# mainboard-01-8x2_1c.net
KiCad netlist of a schematic drawn in EAGLE
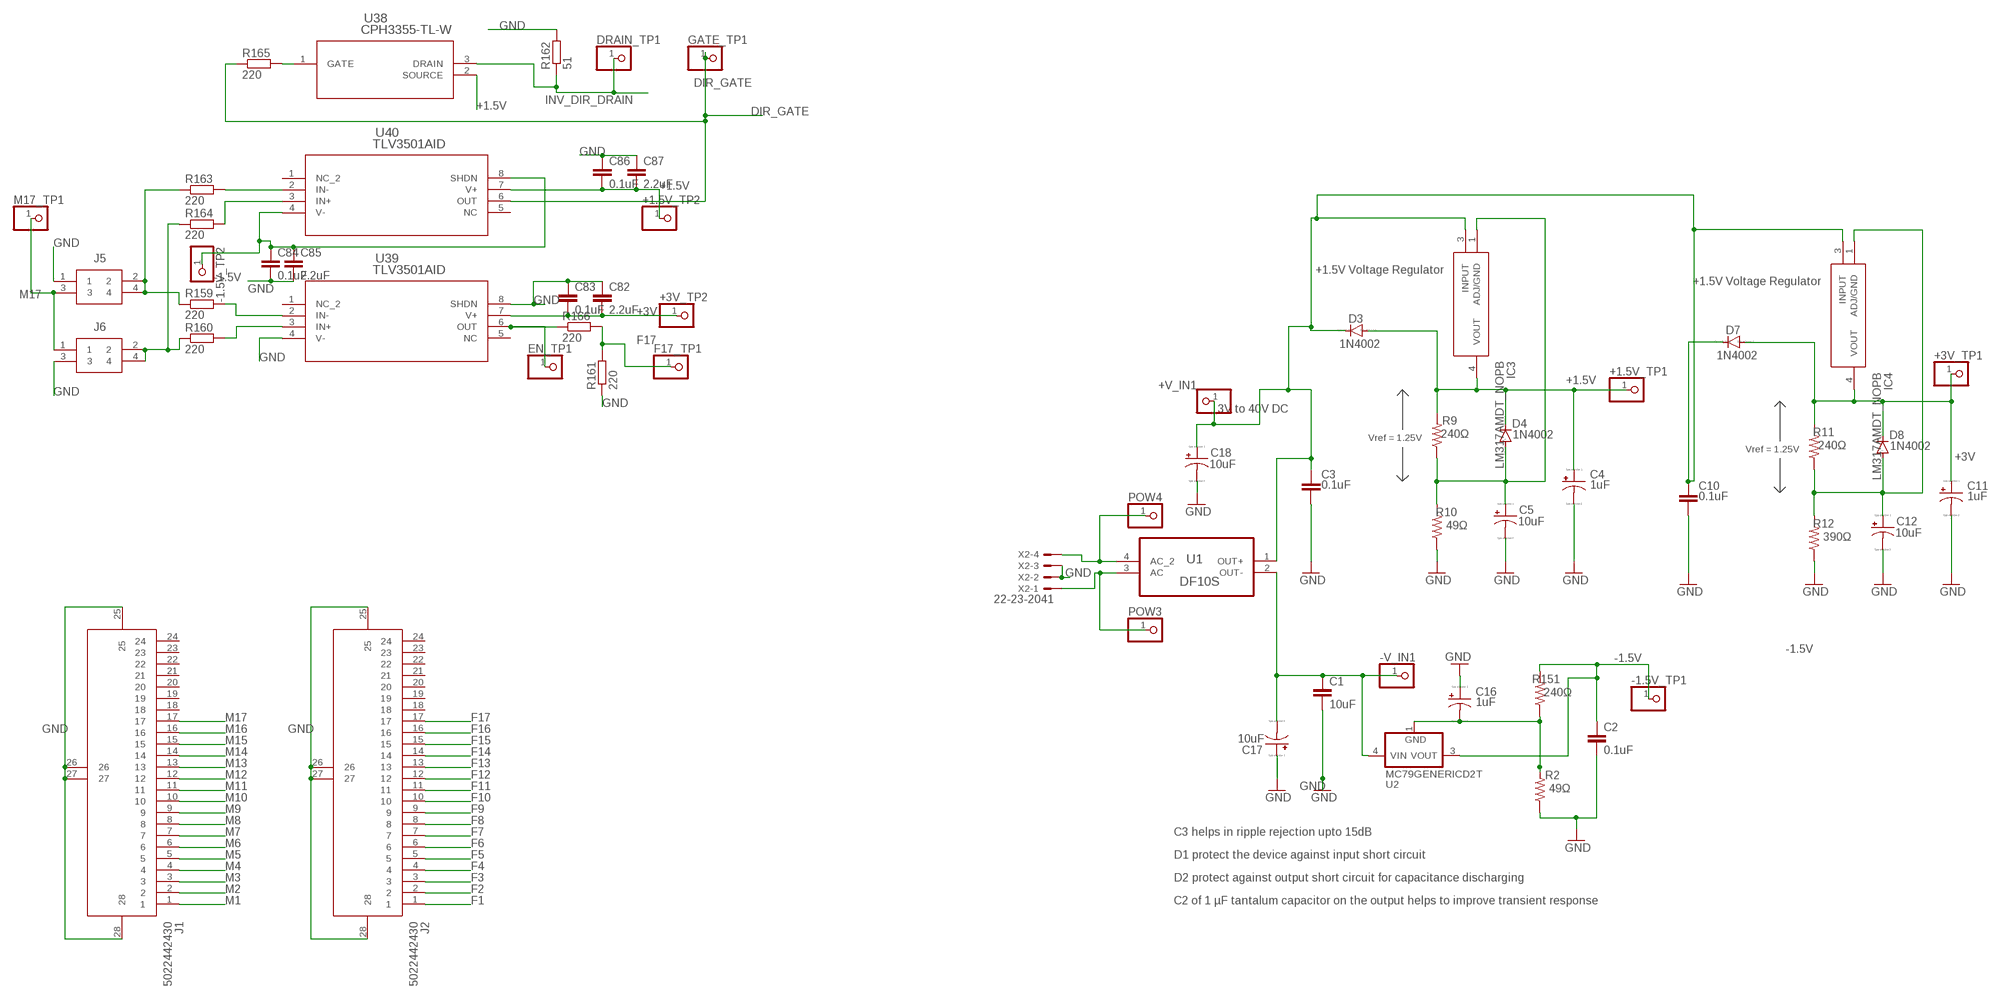
[diagram p0: schematic, sheet 1]
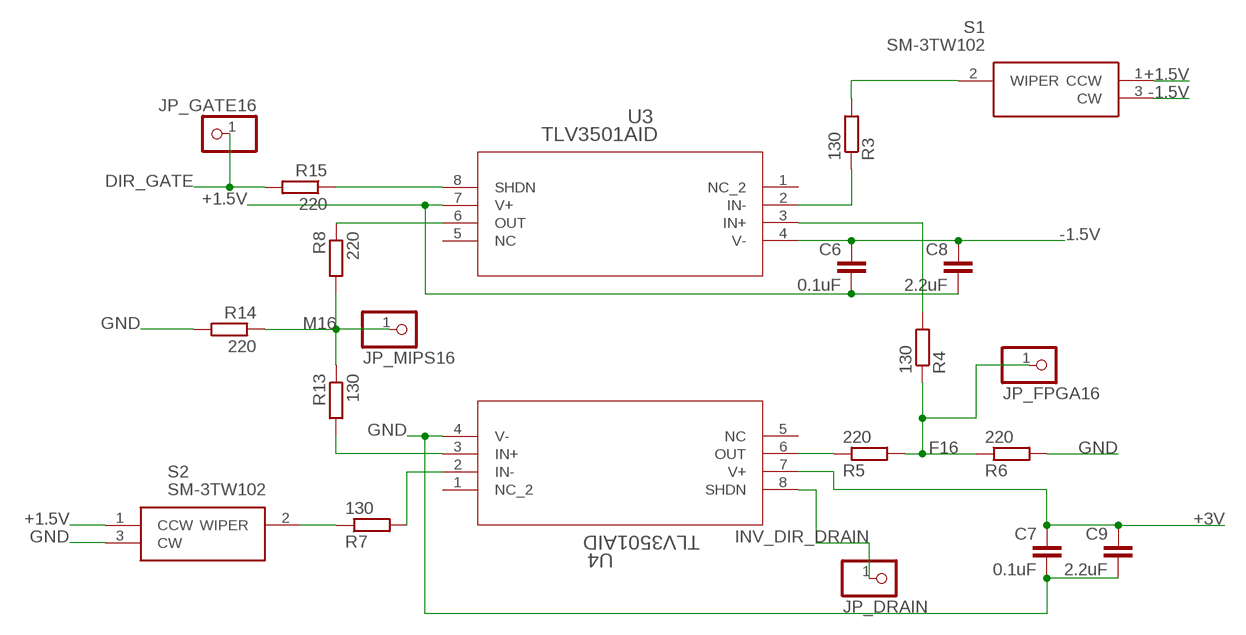
[diagram p1: schematic, sheet 2]
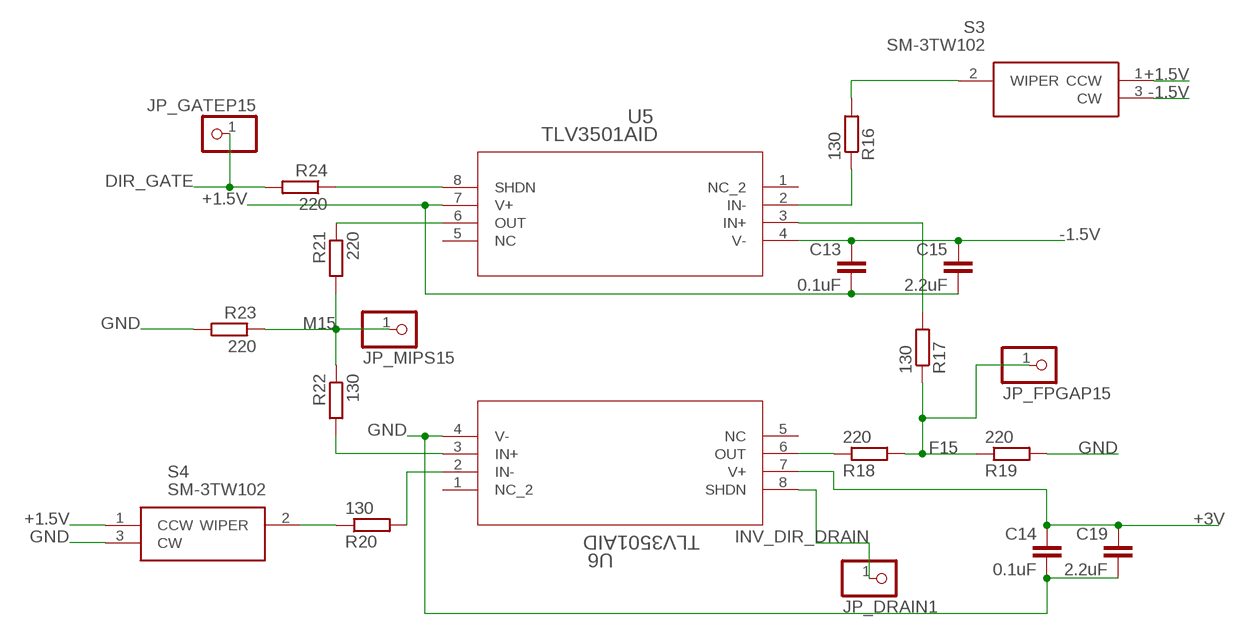
[diagram p2: schematic, sheet 3]
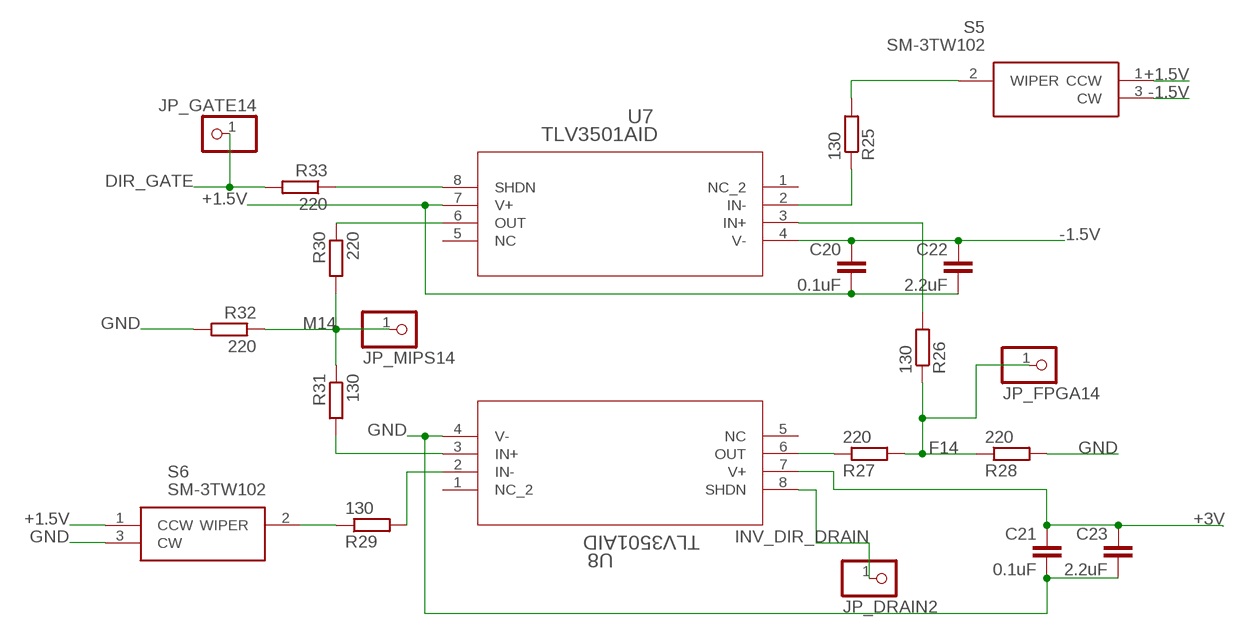
[diagram p3: schematic, sheet 4]
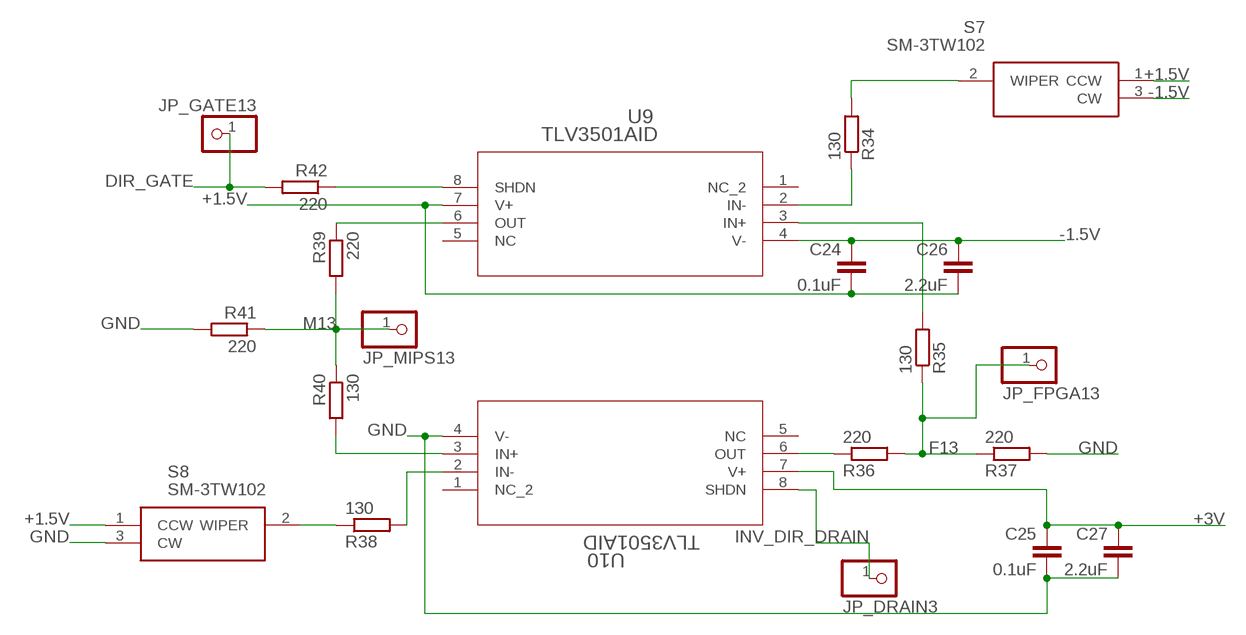
[diagram p4: schematic, sheet 5]
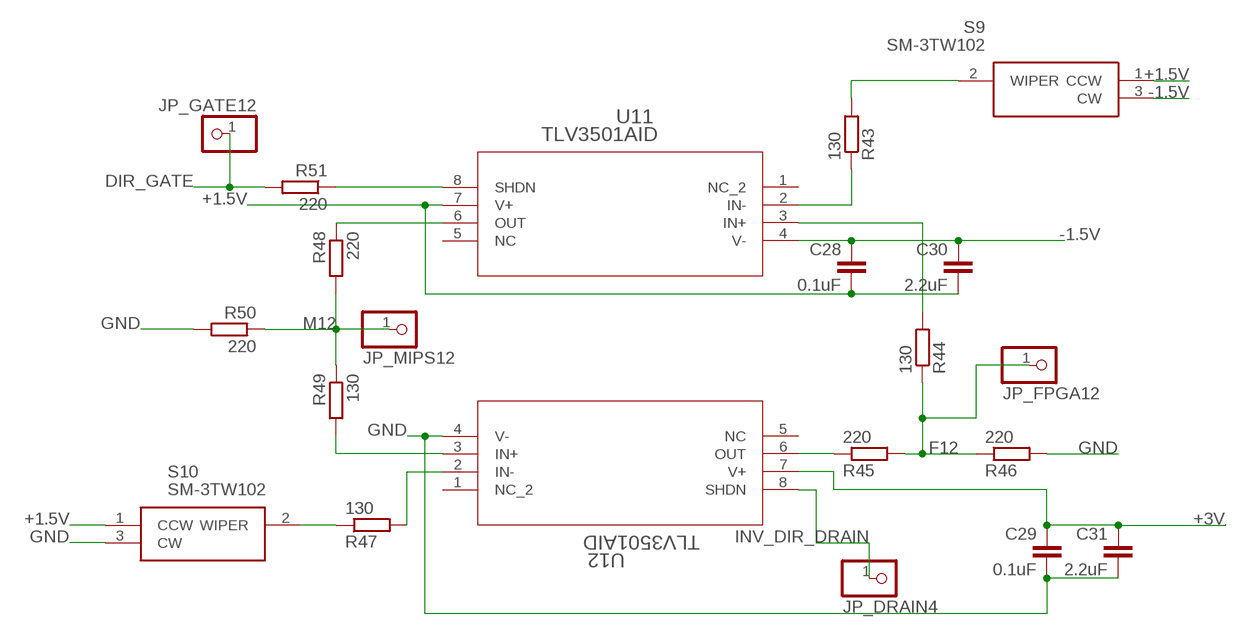
[diagram p5: schematic, sheet 6]
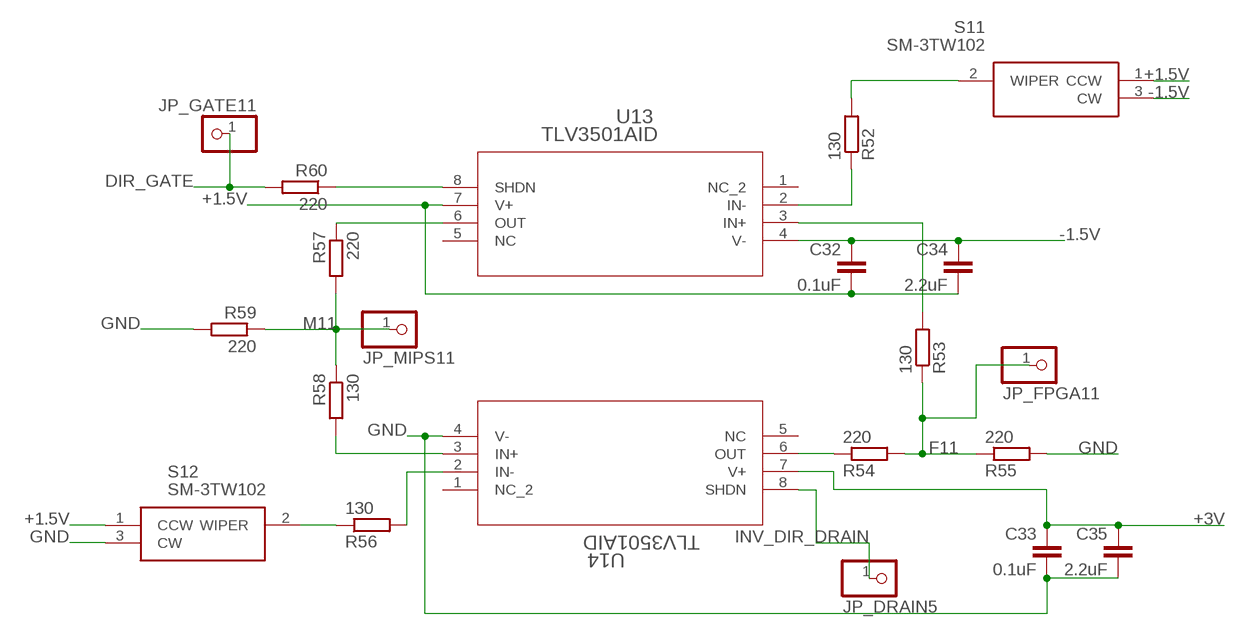
[diagram p6: schematic, sheet 7]
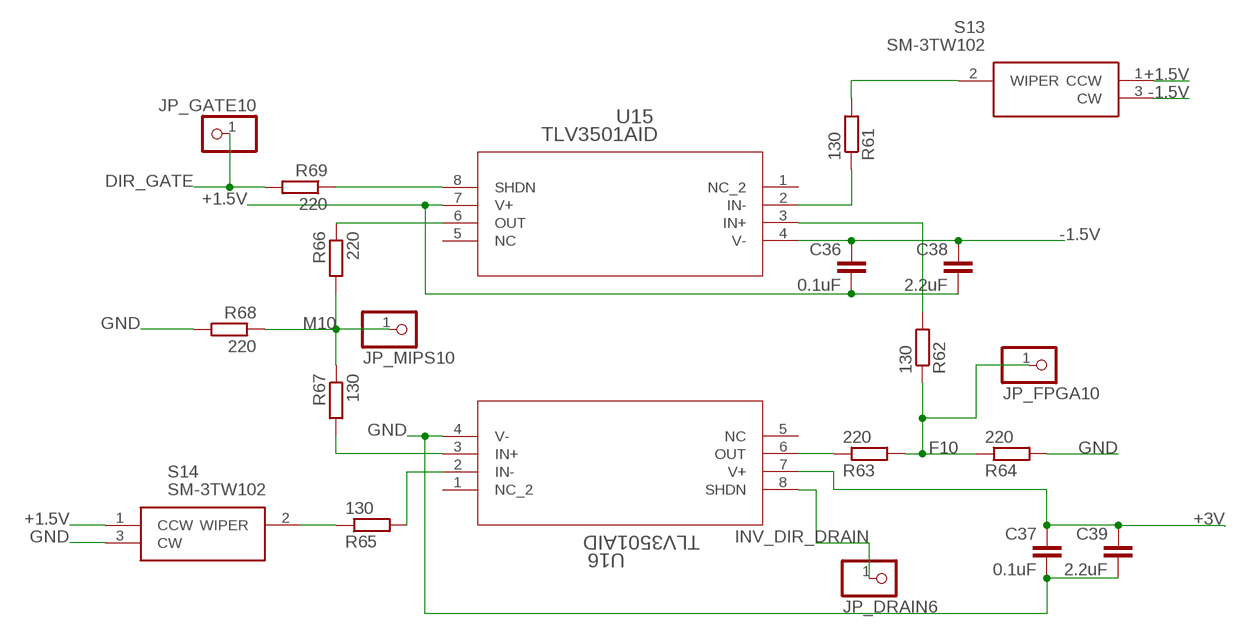
[diagram p7: schematic, sheet 8]
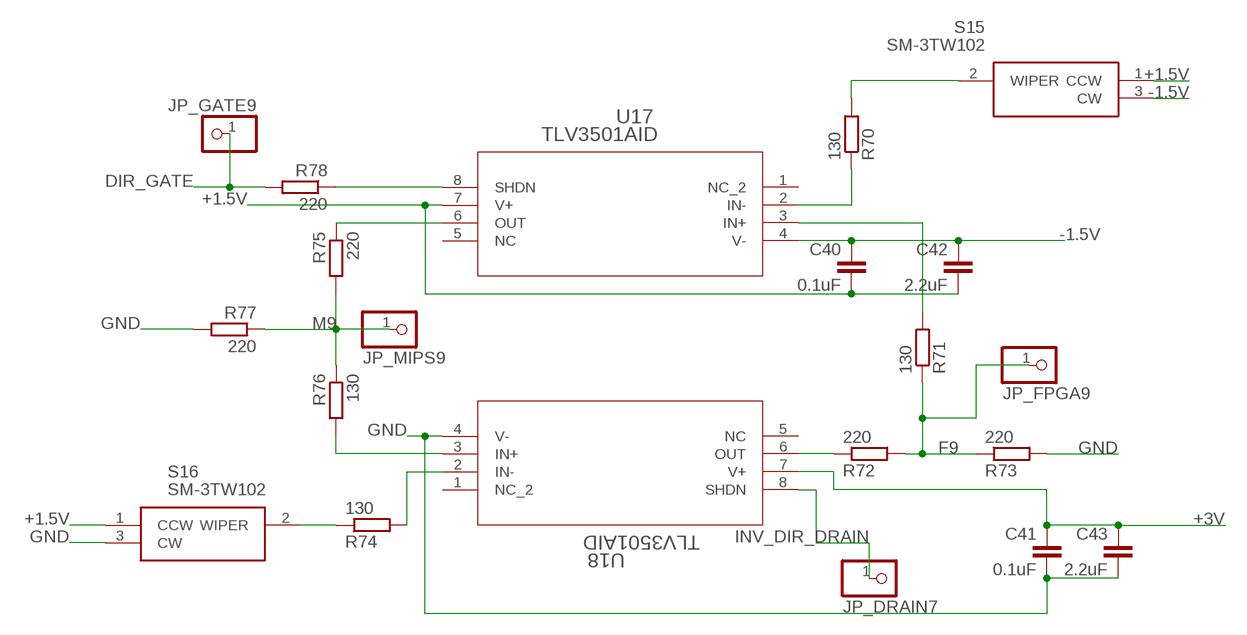
[diagram p8: schematic, sheet 9]
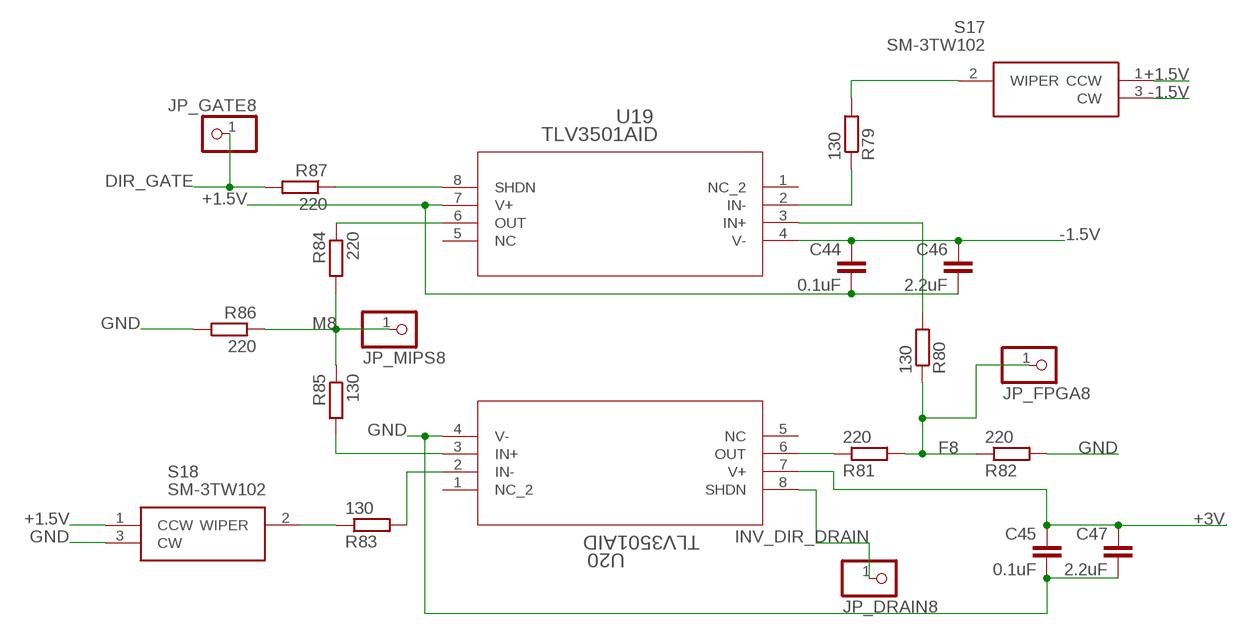
[diagram p9: schematic, sheet 10]
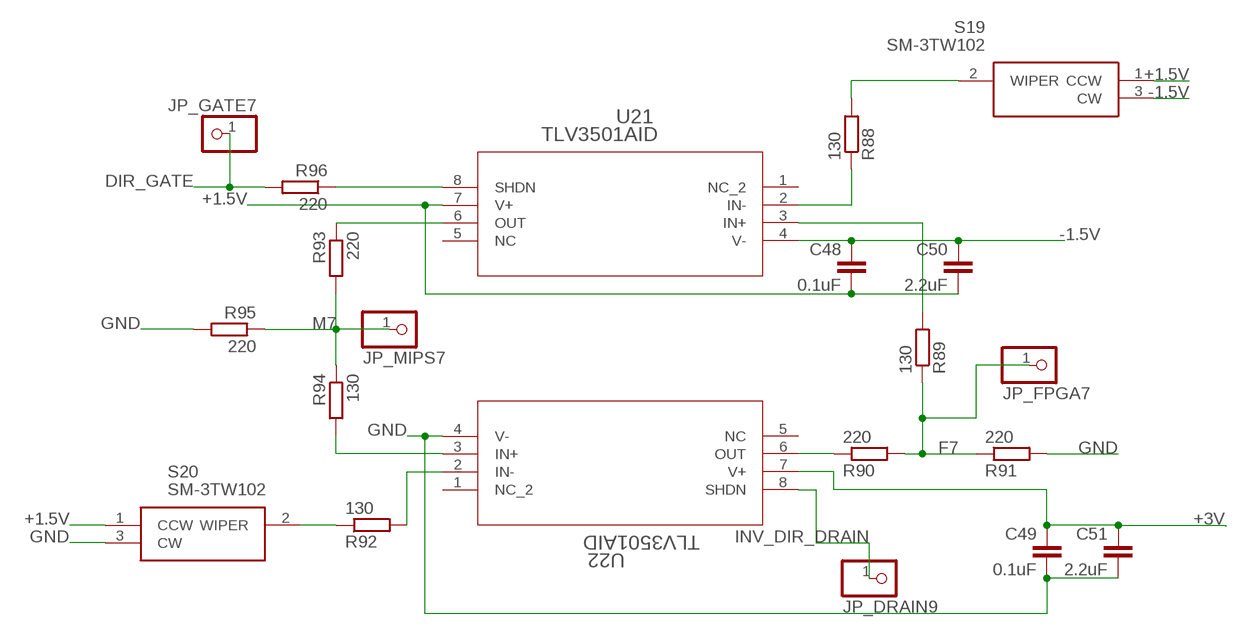
[diagram p10: schematic, sheet 11]
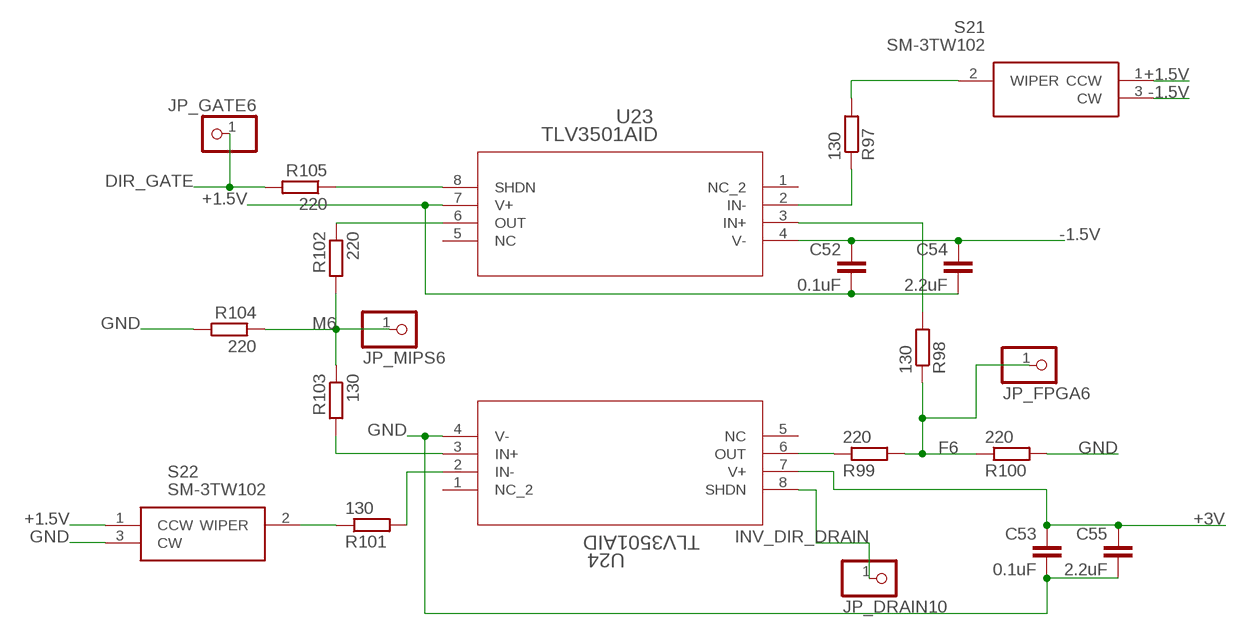
[diagram p11: schematic, sheet 12]
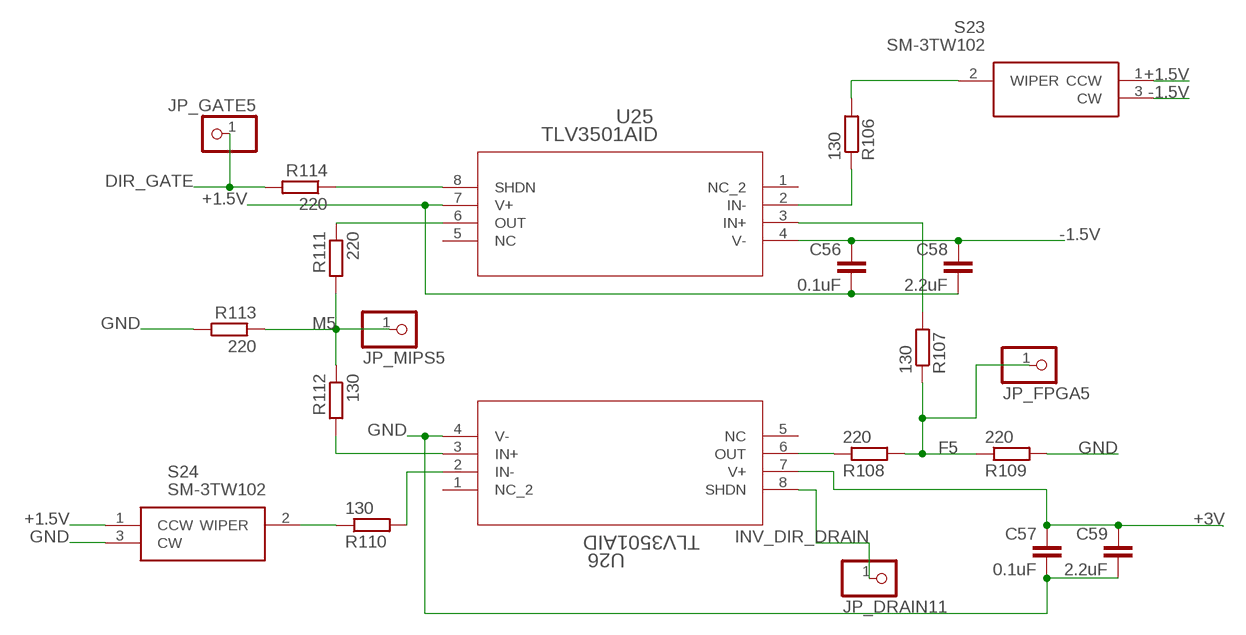
[diagram p12: schematic, sheet 13]
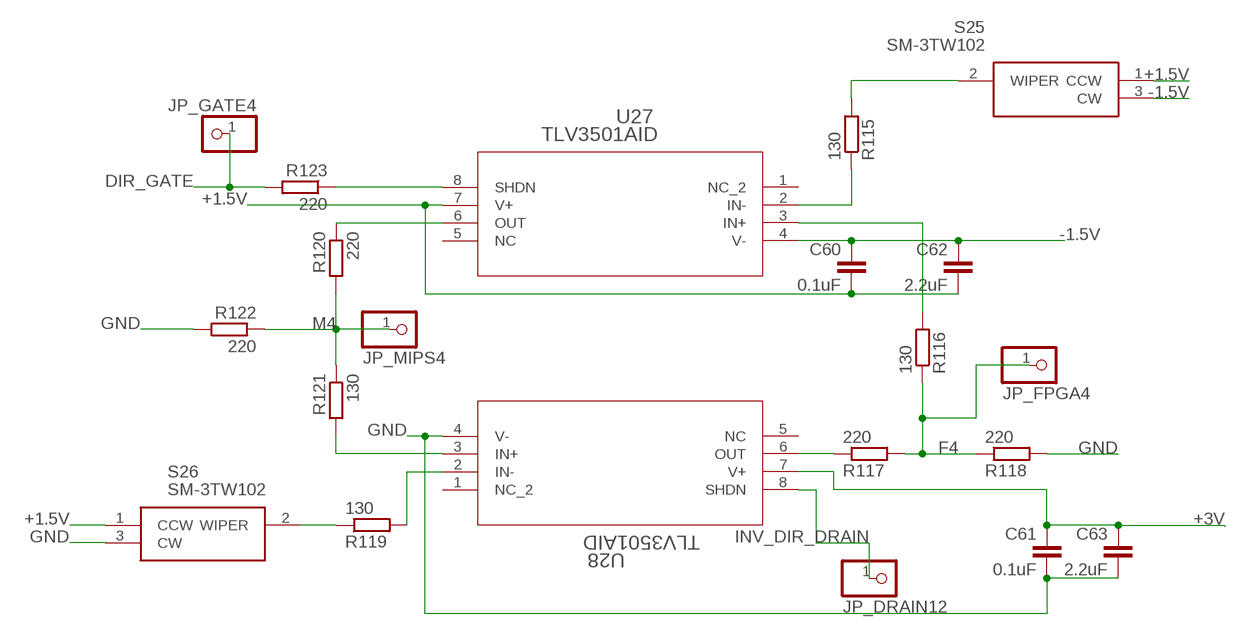
[diagram p13: schematic, sheet 14]
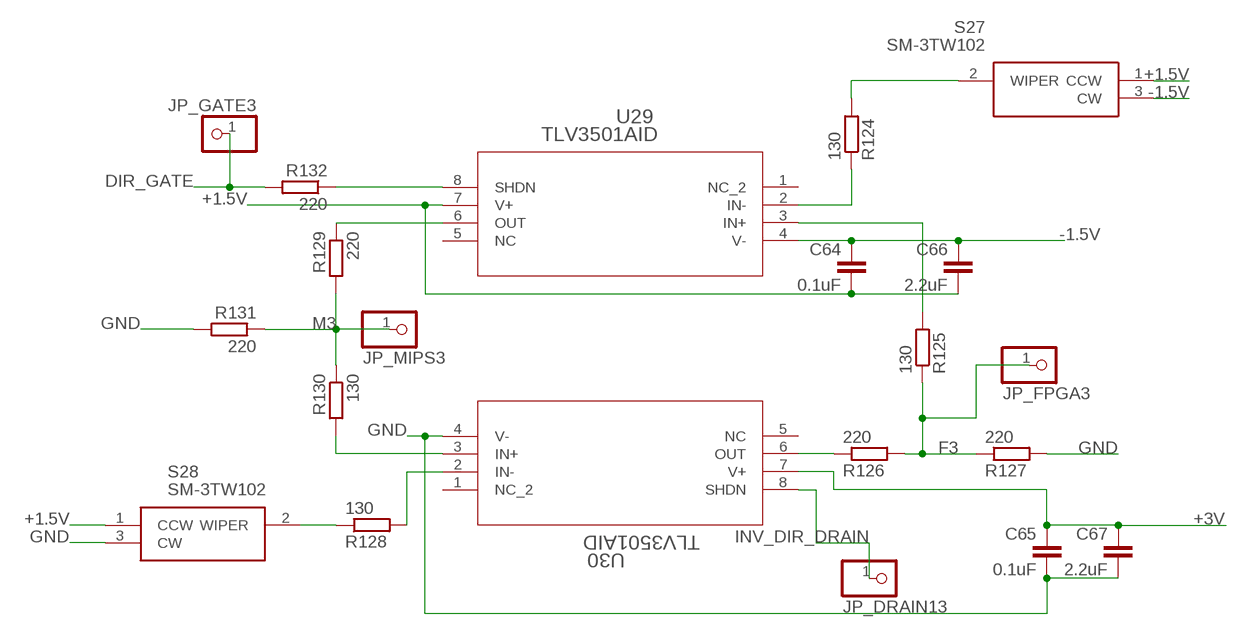
[diagram p14: schematic, sheet 15]
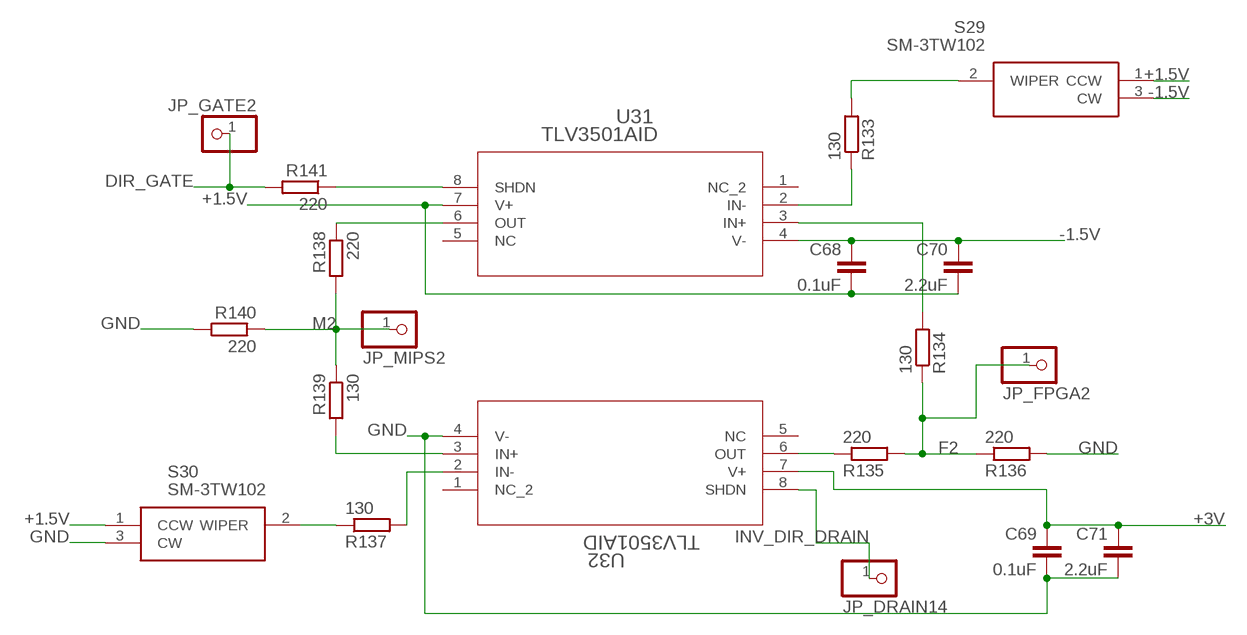
[diagram p15: schematic, sheet 16]
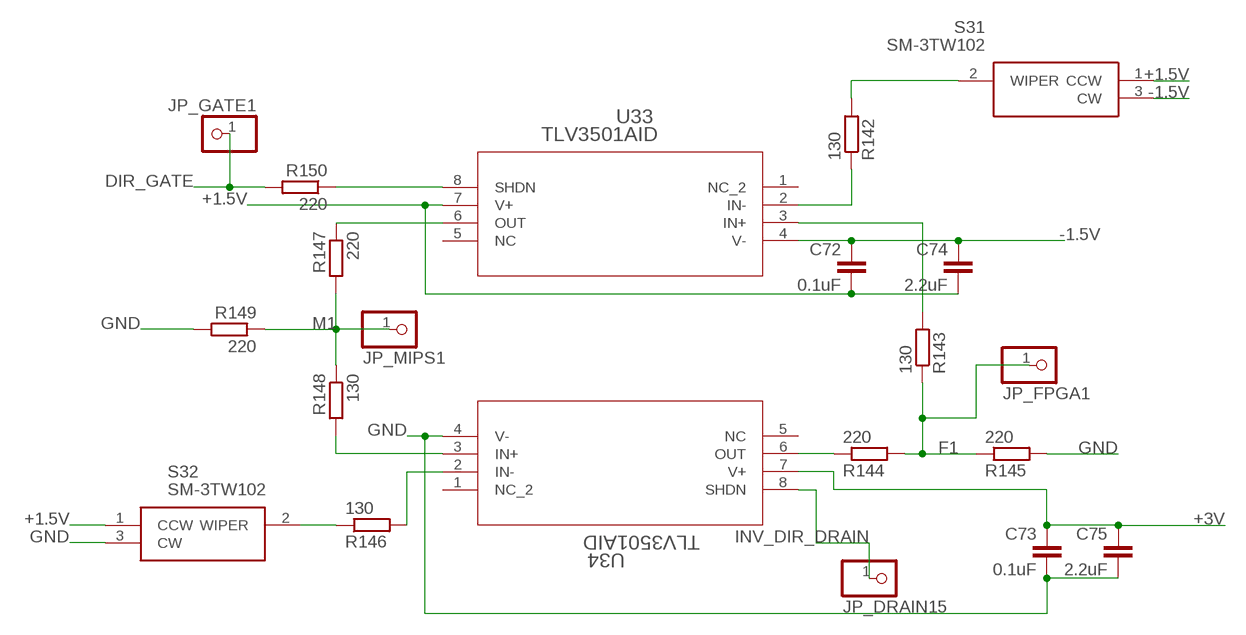
[diagram p16: schematic, sheet 17]

(export (version "E")
  (design (tool "Eeschema 10.0.6"))
  (components
    (comp (ref "C48")
      (value "0.1uF")
      (footprint "eagle-import:C0805")
      (libsource (lib "eagle-import") (part "C-EUC0805"))
    )
    (comp (ref "C49")
      (value "0.1uF")
      (footprint "eagle-import:C0805")
      (libsource (lib "eagle-import") (part "C-EUC0805"))
    )
    (comp (ref "C50")
      (value "2.2uF")
      (footprint "eagle-import:C0805")
      (libsource (lib "eagle-import") (part "C-EUC0805"))
    )
    (comp (ref "C51")
      (value "2.2uF")
      (footprint "eagle-import:C0805")
      (libsource (lib "eagle-import") (part "C-EUC0805"))
    )
    (comp (ref "JP_DRAIN9")
      (value "PINHD-1X1")
      (footprint "eagle-import:1X01")
      (libsource (lib "eagle-import") (part "PINHD-1X1"))
    )
    (comp (ref "JP_FPGA7")
      (value "PINHD-1X1")
      (footprint "eagle-import:1X01")
      (libsource (lib "eagle-import") (part "PINHD-1X1"))
    )
    (comp (ref "JP_GATE7")
      (value "PINHD-1X1")
      (footprint "eagle-import:1X01")
      (libsource (lib "eagle-import") (part "PINHD-1X1"))
    )
    (comp (ref "JP_MIPS7")
      (value "PINHD-1X1")
      (footprint "eagle-import:1X01")
      (libsource (lib "eagle-import") (part "PINHD-1X1"))
    )
    (comp (ref "R88")
      (value "130")
      (footprint "eagle-import:R0805")
      (libsource (lib "eagle-import") (part "R-EU_R0805"))
    )
    (comp (ref "R89")
      (value "130")
      (footprint "eagle-import:R0603")
      (libsource (lib "eagle-import") (part "R-EU_R0603"))
    )
    (comp (ref "R90")
      (value "220")
      (footprint "eagle-import:R0805")
      (libsource (lib "eagle-import") (part "R-EU_R0805"))
    )
    (comp (ref "R91")
      (value "220")
      (footprint "eagle-import:R0805")
      (libsource (lib "eagle-import") (part "R-EU_R0805"))
    )
    (comp (ref "R92")
      (value "130")
      (footprint "eagle-import:R0805")
      (libsource (lib "eagle-import") (part "R-EU_R0805"))
    )
    (comp (ref "R93")
      (value "220")
      (footprint "eagle-import:R0805")
      (libsource (lib "eagle-import") (part "R-EU_R0805"))
    )
    (comp (ref "R94")
      (value "130")
      (footprint "eagle-import:R0805")
      (libsource (lib "eagle-import") (part "R-EU_R0805"))
    )
    (comp (ref "R95")
      (value "220")
      (footprint "eagle-import:R0805")
      (libsource (lib "eagle-import") (part "R-EU_R0805"))
    )
    (comp (ref "R96")
      (value "220")
      (footprint "eagle-import:R0805")
      (libsource (lib "eagle-import") (part "R-EU_R0805"))
    )
    (comp (ref "S19")
      (value "SM-3TW102")
      (footprint "eagle-import:SM3TW102")
      (fields (field (name "MOUSER_PART_NUMBER") "229-SM-3TW102"))
      (libsource (lib "eagle-import") (part "SM-3TW102"))
    )
    (comp (ref "S20")
      (value "SM-3TW102")
      (footprint "eagle-import:SM3TW102")
      (fields (field (name "MOUSER_PART_NUMBER") "229-SM-3TW102"))
      (libsource (lib "eagle-import") (part "SM-3TW102"))
    )
    (comp (ref "U21")
      (value "TLV3501AID")
      (footprint "eagle-import:D8")
      (fields (field (name "COPYRIGHT") "Copyright (C) 2022 Ultra Librarian. All rights reserved."))
      (libsource (lib "eagle-import") (part "TLV3501AID"))
    )
    (comp (ref "U22")
      (value "TLV3501AID")
      (footprint "eagle-import:D8")
      (fields (field (name "COPYRIGHT") "Copyright (C) 2022 Ultra Librarian. All rights reserved."))
      (libsource (lib "eagle-import") (part "TLV3501AID"))
    )
    (comp (ref "C44")
      (value "0.1uF")
      (footprint "eagle-import:C0805")
      (libsource (lib "eagle-import") (part "C-EUC0805"))
    )
    (comp (ref "C45")
      (value "0.1uF")
      (footprint "eagle-import:C0805")
      (libsource (lib "eagle-import") (part "C-EUC0805"))
    )
    (comp (ref "C46")
      (value "2.2uF")
      (footprint "eagle-import:C0805")
      (libsource (lib "eagle-import") (part "C-EUC0805"))
    )
    (comp (ref "C47")
      (value "2.2uF")
      (footprint "eagle-import:C0805")
      (libsource (lib "eagle-import") (part "C-EUC0805"))
    )
    (comp (ref "JP_DRAIN8")
      (value "PINHD-1X1")
      (footprint "eagle-import:1X01")
      (libsource (lib "eagle-import") (part "PINHD-1X1"))
    )
    (comp (ref "JP_FPGA8")
      (value "PINHD-1X1")
      (footprint "eagle-import:1X01")
      (libsource (lib "eagle-import") (part "PINHD-1X1"))
    )
    (comp (ref "JP_GATE8")
      (value "PINHD-1X1")
      (footprint "eagle-import:1X01")
      (libsource (lib "eagle-import") (part "PINHD-1X1"))
    )
    (comp (ref "JP_MIPS8")
      (value "PINHD-1X1")
      (footprint "eagle-import:1X01")
      (libsource (lib "eagle-import") (part "PINHD-1X1"))
    )
    (comp (ref "R79")
      (value "130")
      (footprint "eagle-import:R0805")
      (libsource (lib "eagle-import") (part "R-EU_R0805"))
    )
    (comp (ref "R80")
      (value "130")
      (footprint "eagle-import:R0603")
      (libsource (lib "eagle-import") (part "R-EU_R0603"))
    )
    (comp (ref "R81")
      (value "220")
      (footprint "eagle-import:R0805")
      (libsource (lib "eagle-import") (part "R-EU_R0805"))
    )
    (comp (ref "R82")
      (value "220")
      (footprint "eagle-import:R0805")
      (libsource (lib "eagle-import") (part "R-EU_R0805"))
    )
    (comp (ref "R83")
      (value "130")
      (footprint "eagle-import:R0805")
      (libsource (lib "eagle-import") (part "R-EU_R0805"))
    )
    (comp (ref "R84")
      (value "220")
      (footprint "eagle-import:R0805")
      (libsource (lib "eagle-import") (part "R-EU_R0805"))
    )
    (comp (ref "R85")
      (value "130")
      (footprint "eagle-import:R0805")
      (libsource (lib "eagle-import") (part "R-EU_R0805"))
    )
    (comp (ref "R86")
      (value "220")
      (footprint "eagle-import:R0805")
      (libsource (lib "eagle-import") (part "R-EU_R0805"))
    )
    (comp (ref "R87")
      (value "220")
      (footprint "eagle-import:R0805")
      (libsource (lib "eagle-import") (part "R-EU_R0805"))
    )
    (comp (ref "S17")
      (value "SM-3TW102")
      (footprint "eagle-import:SM3TW102")
      (fields (field (name "MOUSER_PART_NUMBER") "229-SM-3TW102"))
      (libsource (lib "eagle-import") (part "SM-3TW102"))
    )
    (comp (ref "S18")
      (value "SM-3TW102")
      (footprint "eagle-import:SM3TW102")
      (fields (field (name "MOUSER_PART_NUMBER") "229-SM-3TW102"))
      (libsource (lib "eagle-import") (part "SM-3TW102"))
    )
    (comp (ref "U19")
      (value "TLV3501AID")
      (footprint "eagle-import:D8")
      (fields (field (name "COPYRIGHT") "Copyright (C) 2022 Ultra Librarian. All rights reserved."))
      (libsource (lib "eagle-import") (part "TLV3501AID"))
    )
    (comp (ref "U20")
      (value "TLV3501AID")
      (footprint "eagle-import:D8")
      (fields (field (name "COPYRIGHT") "Copyright (C) 2022 Ultra Librarian. All rights reserved."))
      (libsource (lib "eagle-import") (part "TLV3501AID"))
    )
    (comp (ref "C13")
      (value "0.1uF")
      (footprint "eagle-import:C0805")
      (libsource (lib "eagle-import") (part "C-EUC0805"))
    )
    (comp (ref "C14")
      (value "0.1uF")
      (footprint "eagle-import:C0805")
      (libsource (lib "eagle-import") (part "C-EUC0805"))
    )
    (comp (ref "C15")
      (value "2.2uF")
      (footprint "eagle-import:C0805")
      (libsource (lib "eagle-import") (part "C-EUC0805"))
    )
    (comp (ref "C19")
      (value "2.2uF")
      (footprint "eagle-import:C0805")
      (libsource (lib "eagle-import") (part "C-EUC0805"))
    )
    (comp (ref "JP_DRAIN1")
      (value "PINHD-1X1")
      (footprint "eagle-import:1X01")
      (libsource (lib "eagle-import") (part "PINHD-1X1"))
    )
    (comp (ref "JP_FPGAP15")
      (value "PINHD-1X1")
      (footprint "eagle-import:1X01")
      (libsource (lib "eagle-import") (part "PINHD-1X1"))
    )
    (comp (ref "JP_GATEP15")
      (value "PINHD-1X1")
      (footprint "eagle-import:1X01")
      (libsource (lib "eagle-import") (part "PINHD-1X1"))
    )
    (comp (ref "JP_MIPS15")
      (value "PINHD-1X1")
      (footprint "eagle-import:1X01")
      (libsource (lib "eagle-import") (part "PINHD-1X1"))
    )
    (comp (ref "R16")
      (value "130")
      (footprint "eagle-import:R0805")
      (libsource (lib "eagle-import") (part "R-EU_R0805"))
    )
    (comp (ref "R17")
      (value "130")
      (footprint "eagle-import:R0603")
      (libsource (lib "eagle-import") (part "R-EU_R0603"))
    )
    (comp (ref "R18")
      (value "220")
      (footprint "eagle-import:R0805")
      (libsource (lib "eagle-import") (part "R-EU_R0805"))
    )
    (comp (ref "R19")
      (value "220")
      (footprint "eagle-import:R0805")
      (libsource (lib "eagle-import") (part "R-EU_R0805"))
    )
    (comp (ref "R20")
      (value "130")
      (footprint "eagle-import:R0805")
      (libsource (lib "eagle-import") (part "R-EU_R0805"))
    )
    (comp (ref "R21")
      (value "220")
      (footprint "eagle-import:R0805")
      (libsource (lib "eagle-import") (part "R-EU_R0805"))
    )
    (comp (ref "R22")
      (value "130")
      (footprint "eagle-import:R0805")
      (libsource (lib "eagle-import") (part "R-EU_R0805"))
    )
    (comp (ref "R23")
      (value "220")
      (footprint "eagle-import:R0805")
      (libsource (lib "eagle-import") (part "R-EU_R0805"))
    )
    (comp (ref "R24")
      (value "220")
      (footprint "eagle-import:R0805")
      (libsource (lib "eagle-import") (part "R-EU_R0805"))
    )
    (comp (ref "S3")
      (value "SM-3TW102")
      (footprint "eagle-import:SM3TW102")
      (fields (field (name "MOUSER_PART_NUMBER") "229-SM-3TW102"))
      (libsource (lib "eagle-import") (part "SM-3TW102"))
    )
    (comp (ref "S4")
      (value "SM-3TW102")
      (footprint "eagle-import:SM3TW102")
      (fields (field (name "MOUSER_PART_NUMBER") "229-SM-3TW102"))
      (libsource (lib "eagle-import") (part "SM-3TW102"))
    )
    (comp (ref "U5")
      (value "TLV3501AID")
      (footprint "eagle-import:D8")
      (fields (field (name "COPYRIGHT") "Copyright (C) 2022 Ultra Librarian. All rights reserved."))
      (libsource (lib "eagle-import") (part "TLV3501AID"))
    )
    (comp (ref "U6")
      (value "TLV3501AID")
      (footprint "eagle-import:D8")
      (fields (field (name "COPYRIGHT") "Copyright (C) 2022 Ultra Librarian. All rights reserved."))
      (libsource (lib "eagle-import") (part "TLV3501AID"))
    )
    (comp (ref "C64")
      (value "0.1uF")
      (footprint "eagle-import:C0805")
      (libsource (lib "eagle-import") (part "C-EUC0805"))
    )
    (comp (ref "C65")
      (value "0.1uF")
      (footprint "eagle-import:C0805")
      (libsource (lib "eagle-import") (part "C-EUC0805"))
    )
    (comp (ref "C66")
      (value "2.2uF")
      (footprint "eagle-import:C0805")
      (libsource (lib "eagle-import") (part "C-EUC0805"))
    )
    (comp (ref "C67")
      (value "2.2uF")
      (footprint "eagle-import:C0805")
      (libsource (lib "eagle-import") (part "C-EUC0805"))
    )
    (comp (ref "JP_DRAIN13")
      (value "PINHD-1X1")
      (footprint "eagle-import:1X01")
      (libsource (lib "eagle-import") (part "PINHD-1X1"))
    )
    (comp (ref "JP_FPGA3")
      (value "PINHD-1X1")
      (footprint "eagle-import:1X01")
      (libsource (lib "eagle-import") (part "PINHD-1X1"))
    )
    (comp (ref "JP_GATE3")
      (value "PINHD-1X1")
      (footprint "eagle-import:1X01")
      (libsource (lib "eagle-import") (part "PINHD-1X1"))
    )
    (comp (ref "JP_MIPS3")
      (value "PINHD-1X1")
      (footprint "eagle-import:1X01")
      (libsource (lib "eagle-import") (part "PINHD-1X1"))
    )
    (comp (ref "R124")
      (value "130")
      (footprint "eagle-import:R0805")
      (libsource (lib "eagle-import") (part "R-EU_R0805"))
    )
    (comp (ref "R125")
      (value "130")
      (footprint "eagle-import:R0603")
      (libsource (lib "eagle-import") (part "R-EU_R0603"))
    )
    (comp (ref "R126")
      (value "220")
      (footprint "eagle-import:R0805")
      (libsource (lib "eagle-import") (part "R-EU_R0805"))
    )
    (comp (ref "R127")
      (value "220")
      (footprint "eagle-import:R0805")
      (libsource (lib "eagle-import") (part "R-EU_R0805"))
    )
    (comp (ref "R128")
      (value "130")
      (footprint "eagle-import:R0805")
      (libsource (lib "eagle-import") (part "R-EU_R0805"))
    )
    (comp (ref "R129")
      (value "220")
      (footprint "eagle-import:R0805")
      (libsource (lib "eagle-import") (part "R-EU_R0805"))
    )
    (comp (ref "R130")
      (value "130")
      (footprint "eagle-import:R0805")
      (libsource (lib "eagle-import") (part "R-EU_R0805"))
    )
    (comp (ref "R131")
      (value "220")
      (footprint "eagle-import:R0805")
      (libsource (lib "eagle-import") (part "R-EU_R0805"))
    )
    (comp (ref "R132")
      (value "220")
      (footprint "eagle-import:R0805")
      (libsource (lib "eagle-import") (part "R-EU_R0805"))
    )
    (comp (ref "S27")
      (value "SM-3TW102")
      (footprint "eagle-import:SM3TW102")
      (fields (field (name "MOUSER_PART_NUMBER") "229-SM-3TW102"))
      (libsource (lib "eagle-import") (part "SM-3TW102"))
    )
    (comp (ref "S28")
      (value "SM-3TW102")
      (footprint "eagle-import:SM3TW102")
      (fields (field (name "MOUSER_PART_NUMBER") "229-SM-3TW102"))
      (libsource (lib "eagle-import") (part "SM-3TW102"))
    )
    (comp (ref "U29")
      (value "TLV3501AID")
      (footprint "eagle-import:D8")
      (fields (field (name "COPYRIGHT") "Copyright (C) 2022 Ultra Librarian. All rights reserved."))
      (libsource (lib "eagle-import") (part "TLV3501AID"))
    )
    (comp (ref "U30")
      (value "TLV3501AID")
      (footprint "eagle-import:D8")
      (fields (field (name "COPYRIGHT") "Copyright (C) 2022 Ultra Librarian. All rights reserved."))
      (libsource (lib "eagle-import") (part "TLV3501AID"))
    )
    (comp (ref "C56")
      (value "0.1uF")
      (footprint "eagle-import:C0805")
      (libsource (lib "eagle-import") (part "C-EUC0805"))
    )
    (comp (ref "C57")
      (value "0.1uF")
      (footprint "eagle-import:C0805")
      (libsource (lib "eagle-import") (part "C-EUC0805"))
    )
    (comp (ref "C58")
      (value "2.2uF")
      (footprint "eagle-import:C0805")
      (libsource (lib "eagle-import") (part "C-EUC0805"))
    )
    (comp (ref "C59")
      (value "2.2uF")
      (footprint "eagle-import:C0805")
      (libsource (lib "eagle-import") (part "C-EUC0805"))
    )
    (comp (ref "JP_DRAIN11")
      (value "PINHD-1X1")
      (footprint "eagle-import:1X01")
      (libsource (lib "eagle-import") (part "PINHD-1X1"))
    )
    (comp (ref "JP_FPGA5")
      (value "PINHD-1X1")
      (footprint "eagle-import:1X01")
      (libsource (lib "eagle-import") (part "PINHD-1X1"))
    )
    (comp (ref "JP_GATE5")
      (value "PINHD-1X1")
      (footprint "eagle-import:1X01")
      (libsource (lib "eagle-import") (part "PINHD-1X1"))
    )
    (comp (ref "JP_MIPS5")
      (value "PINHD-1X1")
      (footprint "eagle-import:1X01")
      (libsource (lib "eagle-import") (part "PINHD-1X1"))
    )
    (comp (ref "R106")
      (value "130")
      (footprint "eagle-import:R0805")
      (libsource (lib "eagle-import") (part "R-EU_R0805"))
    )
    (comp (ref "R107")
      (value "130")
      (footprint "eagle-import:R0603")
      (libsource (lib "eagle-import") (part "R-EU_R0603"))
    )
    (comp (ref "R108")
      (value "220")
      (footprint "eagle-import:R0805")
      (libsource (lib "eagle-import") (part "R-EU_R0805"))
    )
    (comp (ref "R109")
      (value "220")
      (footprint "eagle-import:R0805")
      (libsource (lib "eagle-import") (part "R-EU_R0805"))
    )
    (comp (ref "R110")
      (value "130")
      (footprint "eagle-import:R0805")
      (libsource (lib "eagle-import") (part "R-EU_R0805"))
    )
    (comp (ref "R111")
      (value "220")
      (footprint "eagle-import:R0805")
      (libsource (lib "eagle-import") (part "R-EU_R0805"))
    )
    (comp (ref "R112")
      (value "130")
      (footprint "eagle-import:R0805")
      (libsource (lib "eagle-import") (part "R-EU_R0805"))
    )
    (comp (ref "R113")
      (value "220")
      (footprint "eagle-import:R0805")
      (libsource (lib "eagle-import") (part "R-EU_R0805"))
    )
    (comp (ref "R114")
      (value "220")
      (footprint "eagle-import:R0805")
      (libsource (lib "eagle-import") (part "R-EU_R0805"))
    )
    (comp (ref "S23")
      (value "SM-3TW102")
      (footprint "eagle-import:SM3TW102")
      (fields (field (name "MOUSER_PART_NUMBER") "229-SM-3TW102"))
      (libsource (lib "eagle-import") (part "SM-3TW102"))
    )
    (comp (ref "S24")
      (value "SM-3TW102")
      (footprint "eagle-import:SM3TW102")
      (fields (field (name "MOUSER_PART_NUMBER") "229-SM-3TW102"))
      (libsource (lib "eagle-import") (part "SM-3TW102"))
    )
    (comp (ref "U25")
      (value "TLV3501AID")
      (footprint "eagle-import:D8")
      (fields (field (name "COPYRIGHT") "Copyright (C) 2022 Ultra Librarian. All rights reserved."))
      (libsource (lib "eagle-import") (part "TLV3501AID"))
    )
    (comp (ref "U26")
      (value "TLV3501AID")
      (footprint "eagle-import:D8")
      (fields (field (name "COPYRIGHT") "Copyright (C) 2022 Ultra Librarian. All rights reserved."))
      (libsource (lib "eagle-import") (part "TLV3501AID"))
    )
    (comp (ref "C28")
      (value "0.1uF")
      (footprint "eagle-import:C0805")
      (libsource (lib "eagle-import") (part "C-EUC0805"))
    )
    (comp (ref "C29")
      (value "0.1uF")
      (footprint "eagle-import:C0805")
      (libsource (lib "eagle-import") (part "C-EUC0805"))
    )
    (comp (ref "C30")
      (value "2.2uF")
      (footprint "eagle-import:C0805")
      (libsource (lib "eagle-import") (part "C-EUC0805"))
    )
    (comp (ref "C31")
      (value "2.2uF")
      (footprint "eagle-import:C0805")
      (libsource (lib "eagle-import") (part "C-EUC0805"))
    )
    (comp (ref "JP_DRAIN4")
      (value "PINHD-1X1")
      (footprint "eagle-import:1X01")
      (libsource (lib "eagle-import") (part "PINHD-1X1"))
    )
    (comp (ref "JP_FPGA12")
      (value "PINHD-1X1")
      (footprint "eagle-import:1X01")
      (libsource (lib "eagle-import") (part "PINHD-1X1"))
    )
    (comp (ref "JP_GATE12")
      (value "PINHD-1X1")
      (footprint "eagle-import:1X01")
      (libsource (lib "eagle-import") (part "PINHD-1X1"))
    )
    (comp (ref "JP_MIPS12")
      (value "PINHD-1X1")
      (footprint "eagle-import:1X01")
      (libsource (lib "eagle-import") (part "PINHD-1X1"))
    )
    (comp (ref "R43")
      (value "130")
      (footprint "eagle-import:R0805")
      (libsource (lib "eagle-import") (part "R-EU_R0805"))
    )
    (comp (ref "R44")
      (value "130")
      (footprint "eagle-import:R0603")
      (libsource (lib "eagle-import") (part "R-EU_R0603"))
    )
    (comp (ref "R45")
      (value "220")
      (footprint "eagle-import:R0805")
      (libsource (lib "eagle-import") (part "R-EU_R0805"))
    )
    (comp (ref "R46")
      (value "220")
      (footprint "eagle-import:R0805")
      (libsource (lib "eagle-import") (part "R-EU_R0805"))
    )
    (comp (ref "R47")
      (value "130")
      (footprint "eagle-import:R0805")
      (libsource (lib "eagle-import") (part "R-EU_R0805"))
    )
    (comp (ref "R48")
      (value "220")
      (footprint "eagle-import:R0805")
      (libsource (lib "eagle-import") (part "R-EU_R0805"))
    )
    (comp (ref "R49")
      (value "130")
      (footprint "eagle-import:R0805")
      (libsource (lib "eagle-import") (part "R-EU_R0805"))
    )
    (comp (ref "R50")
      (value "220")
      (footprint "eagle-import:R0805")
      (libsource (lib "eagle-import") (part "R-EU_R0805"))
    )
    (comp (ref "R51")
      (value "220")
      (footprint "eagle-import:R0805")
      (libsource (lib "eagle-import") (part "R-EU_R0805"))
    )
    (comp (ref "S9")
      (value "SM-3TW102")
      (footprint "eagle-import:SM3TW102")
      (fields (field (name "MOUSER_PART_NUMBER") "229-SM-3TW102"))
      (libsource (lib "eagle-import") (part "SM-3TW102"))
    )
    (comp (ref "S10")
      (value "SM-3TW102")
      (footprint "eagle-import:SM3TW102")
      (fields (field (name "MOUSER_PART_NUMBER") "229-SM-3TW102"))
      (libsource (lib "eagle-import") (part "SM-3TW102"))
    )
    (comp (ref "U11")
      (value "TLV3501AID")
      (footprint "eagle-import:D8")
      (fields (field (name "COPYRIGHT") "Copyright (C) 2022 Ultra Librarian. All rights reserved."))
      (libsource (lib "eagle-import") (part "TLV3501AID"))
    )
    (comp (ref "U12")
      (value "TLV3501AID")
      (footprint "eagle-import:D8")
      (fields (field (name "COPYRIGHT") "Copyright (C) 2022 Ultra Librarian. All rights reserved."))
      (libsource (lib "eagle-import") (part "TLV3501AID"))
    )
    (comp (ref "C40")
      (value "0.1uF")
      (footprint "eagle-import:C0805")
      (libsource (lib "eagle-import") (part "C-EUC0805"))
    )
    (comp (ref "C41")
      (value "0.1uF")
      (footprint "eagle-import:C0805")
      (libsource (lib "eagle-import") (part "C-EUC0805"))
    )
    (comp (ref "C42")
      (value "2.2uF")
      (footprint "eagle-import:C0805")
      (libsource (lib "eagle-import") (part "C-EUC0805"))
    )
    (comp (ref "C43")
      (value "2.2uF")
      (footprint "eagle-import:C0805")
      (libsource (lib "eagle-import") (part "C-EUC0805"))
    )
    (comp (ref "JP_DRAIN7")
      (value "PINHD-1X1")
      (footprint "eagle-import:1X01")
      (libsource (lib "eagle-import") (part "PINHD-1X1"))
    )
    (comp (ref "JP_FPGA9")
      (value "PINHD-1X1")
      (footprint "eagle-import:1X01")
      (libsource (lib "eagle-import") (part "PINHD-1X1"))
    )
    (comp (ref "JP_GATE9")
      (value "PINHD-1X1")
      (footprint "eagle-import:1X01")
      (libsource (lib "eagle-import") (part "PINHD-1X1"))
    )
    (comp (ref "JP_MIPS9")
      (value "PINHD-1X1")
      (footprint "eagle-import:1X01")
      (libsource (lib "eagle-import") (part "PINHD-1X1"))
    )
    (comp (ref "R70")
      (value "130")
      (footprint "eagle-import:R0805")
      (libsource (lib "eagle-import") (part "R-EU_R0805"))
    )
    (comp (ref "R71")
      (value "130")
      (footprint "eagle-import:R0603")
      (libsource (lib "eagle-import") (part "R-EU_R0603"))
    )
    (comp (ref "R72")
      (value "220")
      (footprint "eagle-import:R0805")
      (libsource (lib "eagle-import") (part "R-EU_R0805"))
    )
    (comp (ref "R73")
      (value "220")
      (footprint "eagle-import:R0805")
      (libsource (lib "eagle-import") (part "R-EU_R0805"))
    )
    (comp (ref "R74")
      (value "130")
      (footprint "eagle-import:R0805")
      (libsource (lib "eagle-import") (part "R-EU_R0805"))
    )
    (comp (ref "R75")
      (value "220")
      (footprint "eagle-import:R0805")
      (libsource (lib "eagle-import") (part "R-EU_R0805"))
    )
    (comp (ref "R76")
      (value "130")
      (footprint "eagle-import:R0805")
      (libsource (lib "eagle-import") (part "R-EU_R0805"))
    )
    (comp (ref "R77")
      (value "220")
      (footprint "eagle-import:R0805")
      (libsource (lib "eagle-import") (part "R-EU_R0805"))
    )
    (comp (ref "R78")
      (value "220")
      (footprint "eagle-import:R0805")
      (libsource (lib "eagle-import") (part "R-EU_R0805"))
    )
    (comp (ref "S15")
      (value "SM-3TW102")
      (footprint "eagle-import:SM3TW102")
      (fields (field (name "MOUSER_PART_NUMBER") "229-SM-3TW102"))
      (libsource (lib "eagle-import") (part "SM-3TW102"))
    )
    (comp (ref "S16")
      (value "SM-3TW102")
      (footprint "eagle-import:SM3TW102")
      (fields (field (name "MOUSER_PART_NUMBER") "229-SM-3TW102"))
      (libsource (lib "eagle-import") (part "SM-3TW102"))
    )
    (comp (ref "U17")
      (value "TLV3501AID")
      (footprint "eagle-import:D8")
      (fields (field (name "COPYRIGHT") "Copyright (C) 2022 Ultra Librarian. All rights reserved."))
      (libsource (lib "eagle-import") (part "TLV3501AID"))
    )
    (comp (ref "U18")
      (value "TLV3501AID")
      (footprint "eagle-import:D8")
      (fields (field (name "COPYRIGHT") "Copyright (C) 2022 Ultra Librarian. All rights reserved."))
      (libsource (lib "eagle-import") (part "TLV3501AID"))
    )
    (comp (ref "+1.5V_TP1")
      (value "PINHD-1X1")
      (footprint "eagle-import:1X01")
      (libsource (lib "eagle-import") (part "PINHD-1X1"))
    )
    (comp (ref "+1.5V_TP2")
      (value "PINHD-1X1")
      (footprint "eagle-import:1X01")
      (libsource (lib "eagle-import") (part "PINHD-1X1"))
    )
    (comp (ref "+3V_TP1")
      (value "PINHD-1X1")
      (footprint "eagle-import:1X01")
      (libsource (lib "eagle-import") (part "PINHD-1X1"))
    )
    (comp (ref "+3V_TP2")
      (value "PINHD-1X1")
      (footprint "eagle-import:1X01")
      (libsource (lib "eagle-import") (part "PINHD-1X1"))
    )
    (comp (ref "+V_IN1")
      (value "PINHD-1X1")
      (footprint "eagle-import:1X01")
      (libsource (lib "eagle-import") (part "PINHD-1X1"))
    )
    (comp (ref "-1.5V_TP1")
      (value "PINHD-1X1")
      (footprint "eagle-import:1X01")
      (libsource (lib "eagle-import") (part "PINHD-1X1"))
    )
    (comp (ref "-1.5V_TP2")
      (value "PINHD-1X1")
      (footprint "eagle-import:1X01")
      (libsource (lib "eagle-import") (part "PINHD-1X1"))
    )
    (comp (ref "-V_IN1")
      (value "PINHD-1X1")
      (footprint "eagle-import:1X01")
      (libsource (lib "eagle-import") (part "PINHD-1X1"))
    )
    (comp (ref "C1")
      (value "10uF")
      (footprint "eagle-import:C0805")
      (libsource (lib "eagle-import") (part "C-EUC0805"))
    )
    (comp (ref "C2")
      (value "0.1uF")
      (footprint "eagle-import:C0805")
      (libsource (lib "eagle-import") (part "C-EUC0805"))
    )
    (comp (ref "C3")
      (value "0.1uF")
      (footprint "eagle-import:C075-052X106")
      (libsource (lib "eagle-import") (part "C-EU075-052X106"))
    )
    (comp (ref "C4")
      (value "1uF")
      (footprint "eagle-import:085CS_1AR")
      (libsource (lib "eagle-import") (part "CPOL-US085CS-1AR"))
    )
    (comp (ref "C5")
      (value "10uF")
      (footprint "eagle-import:085CS_1AR")
      (libsource (lib "eagle-import") (part "CPOL-US085CS-1AR"))
    )
    (comp (ref "C10")
      (value "0.1uF")
      (footprint "eagle-import:C075-052X106")
      (libsource (lib "eagle-import") (part "C-EU075-052X106"))
    )
    (comp (ref "C11")
      (value "1uF")
      (footprint "eagle-import:085CS_1AR")
      (libsource (lib "eagle-import") (part "CPOL-US085CS-1AR"))
    )
    (comp (ref "C12")
      (value "10uF")
      (footprint "eagle-import:085CS_1AR")
      (libsource (lib "eagle-import") (part "CPOL-US085CS-1AR"))
    )
    (comp (ref "C16")
      (value "1uF")
      (footprint "eagle-import:085CS_1AR")
      (libsource (lib "eagle-import") (part "CPOL-US085CS-1AR"))
    )
    (comp (ref "C17")
      (value "10uF")
      (footprint "eagle-import:085CS_1AR")
      (libsource (lib "eagle-import") (part "CPOL-US085CS-1AR"))
    )
    (comp (ref "C18")
      (value "10uF")
      (footprint "eagle-import:085CS_1AR")
      (libsource (lib "eagle-import") (part "CPOL-US085CS-1AR"))
    )
    (comp (ref "C82")
      (value "2.2uF")
      (footprint "eagle-import:C0805")
      (libsource (lib "eagle-import") (part "C-EUC0805"))
    )
    (comp (ref "C83")
      (value "0.1uF")
      (footprint "eagle-import:C0805")
      (libsource (lib "eagle-import") (part "C-EUC0805"))
    )
    (comp (ref "C84")
      (value "0.1uF")
      (footprint "eagle-import:C0805")
      (libsource (lib "eagle-import") (part "C-EUC0805"))
    )
    (comp (ref "C85")
      (value "2.2uF")
      (footprint "eagle-import:C0805")
      (libsource (lib "eagle-import") (part "C-EUC0805"))
    )
    (comp (ref "C86")
      (value "0.1uF")
      (footprint "eagle-import:C0805")
      (libsource (lib "eagle-import") (part "C-EUC0805"))
    )
    (comp (ref "C87")
      (value "2.2uF")
      (footprint "eagle-import:C0805")
      (libsource (lib "eagle-import") (part "C-EUC0805"))
    )
    (comp (ref "D3")
      (value "1N4002")
      (footprint "eagle-import:DO41-10")
      (libsource (lib "eagle-import") (part "1N4004"))
    )
    (comp (ref "D4")
      (value "1N4002")
      (footprint "eagle-import:DO41-10")
      (libsource (lib "eagle-import") (part "1N4004"))
    )
    (comp (ref "D7")
      (value "1N4002")
      (footprint "eagle-import:DO41-10")
      (libsource (lib "eagle-import") (part "1N4004"))
    )
    (comp (ref "D8")
      (value "1N4002")
      (footprint "eagle-import:DO41-10")
      (libsource (lib "eagle-import") (part "1N4004"))
    )
    (comp (ref "DRAIN_TP1")
      (value "PINHD-1X1")
      (footprint "eagle-import:1X01")
      (libsource (lib "eagle-import") (part "PINHD-1X1"))
    )
    (comp (ref "EN_TP1")
      (value "PINHD-1X1")
      (footprint "eagle-import:1X01")
      (libsource (lib "eagle-import") (part "PINHD-1X1"))
    )
    (comp (ref "F17_TP1")
      (value "PINHD-1X1")
      (footprint "eagle-import:1X01")
      (libsource (lib "eagle-import") (part "PINHD-1X1"))
    )
    (comp (ref "GATE_TP1")
      (value "PINHD-1X1")
      (footprint "eagle-import:1X01")
      (libsource (lib "eagle-import") (part "PINHD-1X1"))
    )
    (comp (ref "IC3")
      (value "LM317AMDT_NOPB")
      (footprint "eagle-import:TO228P991X238-3N")
      (fields
        (field (name "MANUFACTURER_PART_NUMBER") "LM317AMDT/NOPB")
        (field (name "MOUSER_PART_NUMBER") "926-LM317AMDT/NOPB")
      )
      (libsource (lib "eagle-import") (part "LM317AMDT_NOPB"))
    )
    (comp (ref "IC4")
      (value "LM317AMDT_NOPB")
      (footprint "eagle-import:TO228P991X238-3N")
      (fields
        (field (name "MANUFACTURER_PART_NUMBER") "LM317AMDT/NOPB")
        (field (name "MOUSER_PART_NUMBER") "926-LM317AMDT/NOPB")
      )
      (libsource (lib "eagle-import") (part "LM317AMDT_NOPB"))
    )
    (comp (ref "J1")
      (value "5022442430")
      (footprint "eagle-import:5022442430")
      (libsource (lib "eagle-import") (part "5022442430"))
    )
    (comp (ref "J2")
      (value "5022442430")
      (footprint "eagle-import:5022442430")
      (libsource (lib "eagle-import") (part "5022442430"))
    )
    (comp (ref "J5")
      (value "70287-1098")
      (footprint "eagle-import:HDRV4W64P254_2X2_521X508X851P")
      (fields (field (name "MOUSER_PART_NUMBER") "538-70287-1098"))
      (libsource (lib "eagle-import") (part "70287-1098"))
    )
    (comp (ref "J6")
      (value "70287-1098")
      (footprint "eagle-import:HDRV4W64P254_2X2_521X508X851P")
      (fields (field (name "MOUSER_PART_NUMBER") "538-70287-1098"))
      (libsource (lib "eagle-import") (part "70287-1098"))
    )
    (comp (ref "M17_TP1")
      (value "PINHD-1X1")
      (footprint "eagle-import:1X01")
      (libsource (lib "eagle-import") (part "PINHD-1X1"))
    )
    (comp (ref "POW3")
      (value "PINHD-1X1")
      (footprint "eagle-import:1X01")
      (libsource (lib "eagle-import") (part "PINHD-1X1"))
    )
    (comp (ref "POW4")
      (value "PINHD-1X1")
      (footprint "eagle-import:1X01")
      (libsource (lib "eagle-import") (part "PINHD-1X1"))
    )
    (comp (ref "R2")
      (value "49Ω")
      (footprint "eagle-import:M0805")
      (libsource (lib "eagle-import") (part "R-US_M0805"))
    )
    (comp (ref "R9")
      (value "240Ω")
      (footprint "eagle-import:M0805")
      (libsource (lib "eagle-import") (part "R-US_M0805"))
    )
    (comp (ref "R10")
      (value "49Ω")
      (footprint "eagle-import:M0805")
      (libsource (lib "eagle-import") (part "R-US_M0805"))
    )
    (comp (ref "R11")
      (value "240Ω")
      (footprint "eagle-import:M0805")
      (libsource (lib "eagle-import") (part "R-US_M0805"))
    )
    (comp (ref "R12")
      (value "390Ω")
      (footprint "eagle-import:M0805")
      (libsource (lib "eagle-import") (part "R-US_M0805"))
    )
    (comp (ref "R151")
      (value "240Ω")
      (footprint "eagle-import:M0805")
      (libsource (lib "eagle-import") (part "R-US_M0805"))
    )
    (comp (ref "R159")
      (value "220")
      (footprint "eagle-import:R0603")
      (libsource (lib "eagle-import") (part "R-EU_R0603"))
    )
    (comp (ref "R160")
      (value "220")
      (footprint "eagle-import:R0603")
      (libsource (lib "eagle-import") (part "R-EU_R0603"))
    )
    (comp (ref "R161")
      (value "220")
      (footprint "eagle-import:R0603")
      (libsource (lib "eagle-import") (part "R-EU_R0603"))
    )
    (comp (ref "R162")
      (value "51")
      (footprint "eagle-import:R0805")
      (libsource (lib "eagle-import") (part "R-EU_R0805"))
    )
    (comp (ref "R163")
      (value "220")
      (footprint "eagle-import:R0603")
      (libsource (lib "eagle-import") (part "R-EU_R0603"))
    )
    (comp (ref "R164")
      (value "220")
      (footprint "eagle-import:R0603")
      (libsource (lib "eagle-import") (part "R-EU_R0603"))
    )
    (comp (ref "R165")
      (value "220")
      (footprint "eagle-import:R0603")
      (libsource (lib "eagle-import") (part "R-EU_R0603"))
    )
    (comp (ref "R166")
      (value "220")
      (footprint "eagle-import:R0603")
      (libsource (lib "eagle-import") (part "R-EU_R0603"))
    )
    (comp (ref "U1")
      (value "DF10S")
      (footprint "eagle-import:SOT508P985X260-4N")
      (fields (field (name "DIGI-KEY_PART_NUMBER") "DF10STR-ND") (field (name "MF") "ON"))
      (libsource (lib "eagle-import") (part "DF10S"))
    )
    (comp (ref "U2")
      (value "MC79GENERICD2T")
      (footprint "eagle-import:D2PAK-3")
      (libsource (lib "eagle-import") (part "MC79D2TGENERIC"))
    )
    (comp (ref "U38")
      (value "CPH3355-TL-W")
      (footprint "eagle-import:CPH3_2P9X1P6_ONS")
      (fields (field (name "COPYRIGHT") "Copyright (C) 2022 Ultra Librarian. All rights reserved."))
      (libsource (lib "eagle-import") (part "CPH3355-TL-W"))
    )
    (comp (ref "U39")
      (value "TLV3501AID")
      (footprint "eagle-import:D8")
      (fields (field (name "COPYRIGHT") "Copyright (C) 2022 Ultra Librarian. All rights reserved."))
      (libsource (lib "eagle-import") (part "TLV3501AID"))
    )
    (comp (ref "U40")
      (value "TLV3501AID")
      (footprint "eagle-import:D8")
      (fields (field (name "COPYRIGHT") "Copyright (C) 2022 Ultra Librarian. All rights reserved."))
      (libsource (lib "eagle-import") (part "TLV3501AID"))
    )
    (comp (ref "X2")
      (value "22-23-2041")
      (footprint "eagle-import:22-23-2041")
      (fields (field (name "MF") "MOLEX"))
      (libsource (lib "eagle-import") (part "22-23-2041"))
    )
    (comp (ref "C24")
      (value "0.1uF")
      (footprint "eagle-import:C0805")
      (libsource (lib "eagle-import") (part "C-EUC0805"))
    )
    (comp (ref "C25")
      (value "0.1uF")
      (footprint "eagle-import:C0805")
      (libsource (lib "eagle-import") (part "C-EUC0805"))
    )
    (comp (ref "C26")
      (value "2.2uF")
      (footprint "eagle-import:C0805")
      (libsource (lib "eagle-import") (part "C-EUC0805"))
    )
    (comp (ref "C27")
      (value "2.2uF")
      (footprint "eagle-import:C0805")
      (libsource (lib "eagle-import") (part "C-EUC0805"))
    )
    (comp (ref "JP_DRAIN3")
      (value "PINHD-1X1")
      (footprint "eagle-import:1X01")
      (libsource (lib "eagle-import") (part "PINHD-1X1"))
    )
    (comp (ref "JP_FPGA13")
      (value "PINHD-1X1")
      (footprint "eagle-import:1X01")
      (libsource (lib "eagle-import") (part "PINHD-1X1"))
    )
    (comp (ref "JP_GATE13")
      (value "PINHD-1X1")
      (footprint "eagle-import:1X01")
      (libsource (lib "eagle-import") (part "PINHD-1X1"))
    )
    (comp (ref "JP_MIPS13")
      (value "PINHD-1X1")
      (footprint "eagle-import:1X01")
      (libsource (lib "eagle-import") (part "PINHD-1X1"))
    )
    (comp (ref "R34")
      (value "130")
      (footprint "eagle-import:R0805")
      (libsource (lib "eagle-import") (part "R-EU_R0805"))
    )
    (comp (ref "R35")
      (value "130")
      (footprint "eagle-import:R0603")
      (libsource (lib "eagle-import") (part "R-EU_R0603"))
    )
    (comp (ref "R36")
      (value "220")
      (footprint "eagle-import:R0805")
      (libsource (lib "eagle-import") (part "R-EU_R0805"))
    )
    (comp (ref "R37")
      (value "220")
      (footprint "eagle-import:R0805")
      (libsource (lib "eagle-import") (part "R-EU_R0805"))
    )
    (comp (ref "R38")
      (value "130")
      (footprint "eagle-import:R0805")
      (libsource (lib "eagle-import") (part "R-EU_R0805"))
    )
    (comp (ref "R39")
      (value "220")
      (footprint "eagle-import:R0805")
      (libsource (lib "eagle-import") (part "R-EU_R0805"))
    )
    (comp (ref "R40")
      (value "130")
      (footprint "eagle-import:R0805")
      (libsource (lib "eagle-import") (part "R-EU_R0805"))
    )
    (comp (ref "R41")
      (value "220")
      (footprint "eagle-import:R0805")
      (libsource (lib "eagle-import") (part "R-EU_R0805"))
    )
    (comp (ref "R42")
      (value "220")
      (footprint "eagle-import:R0805")
      (libsource (lib "eagle-import") (part "R-EU_R0805"))
    )
    (comp (ref "S7")
      (value "SM-3TW102")
      (footprint "eagle-import:SM3TW102")
      (fields (field (name "MOUSER_PART_NUMBER") "229-SM-3TW102"))
      (libsource (lib "eagle-import") (part "SM-3TW102"))
    )
    (comp (ref "S8")
      (value "SM-3TW102")
      (footprint "eagle-import:SM3TW102")
      (fields (field (name "MOUSER_PART_NUMBER") "229-SM-3TW102"))
      (libsource (lib "eagle-import") (part "SM-3TW102"))
    )
    (comp (ref "U9")
      (value "TLV3501AID")
      (footprint "eagle-import:D8")
      (fields (field (name "COPYRIGHT") "Copyright (C) 2022 Ultra Librarian. All rights reserved."))
      (libsource (lib "eagle-import") (part "TLV3501AID"))
    )
    (comp (ref "U10")
      (value "TLV3501AID")
      (footprint "eagle-import:D8")
      (fields (field (name "COPYRIGHT") "Copyright (C) 2022 Ultra Librarian. All rights reserved."))
      (libsource (lib "eagle-import") (part "TLV3501AID"))
    )
    (comp (ref "C6")
      (value "0.1uF")
      (footprint "eagle-import:C0805")
      (libsource (lib "eagle-import") (part "C-EUC0805"))
    )
    (comp (ref "C7")
      (value "0.1uF")
      (footprint "eagle-import:C0805")
      (libsource (lib "eagle-import") (part "C-EUC0805"))
    )
    (comp (ref "C8")
      (value "2.2uF")
      (footprint "eagle-import:C0805")
      (libsource (lib "eagle-import") (part "C-EUC0805"))
    )
    (comp (ref "C9")
      (value "2.2uF")
      (footprint "eagle-import:C0805")
      (libsource (lib "eagle-import") (part "C-EUC0805"))
    )
    (comp (ref "JP_DRAIN")
      (value "PINHD-1X1")
      (footprint "eagle-import:1X01")
      (libsource (lib "eagle-import") (part "PINHD-1X1"))
    )
    (comp (ref "JP_FPGA16")
      (value "PINHD-1X1")
      (footprint "eagle-import:1X01")
      (libsource (lib "eagle-import") (part "PINHD-1X1"))
    )
    (comp (ref "JP_GATE16")
      (value "PINHD-1X1")
      (footprint "eagle-import:1X01")
      (libsource (lib "eagle-import") (part "PINHD-1X1"))
    )
    (comp (ref "JP_MIPS16")
      (value "PINHD-1X1")
      (footprint "eagle-import:1X01")
      (libsource (lib "eagle-import") (part "PINHD-1X1"))
    )
    (comp (ref "R3")
      (value "130")
      (footprint "eagle-import:R0805")
      (libsource (lib "eagle-import") (part "R-EU_R0805"))
    )
    (comp (ref "R4")
      (value "130")
      (footprint "eagle-import:R0603")
      (libsource (lib "eagle-import") (part "R-EU_R0603"))
    )
    (comp (ref "R5")
      (value "220")
      (footprint "eagle-import:R0805")
      (libsource (lib "eagle-import") (part "R-EU_R0805"))
    )
    (comp (ref "R6")
      (value "220")
      (footprint "eagle-import:R0805")
      (libsource (lib "eagle-import") (part "R-EU_R0805"))
    )
    (comp (ref "R7")
      (value "130")
      (footprint "eagle-import:R0805")
      (libsource (lib "eagle-import") (part "R-EU_R0805"))
    )
    (comp (ref "R8")
      (value "220")
      (footprint "eagle-import:R0805")
      (libsource (lib "eagle-import") (part "R-EU_R0805"))
    )
    (comp (ref "R13")
      (value "130")
      (footprint "eagle-import:R0805")
      (libsource (lib "eagle-import") (part "R-EU_R0805"))
    )
    (comp (ref "R14")
      (value "220")
      (footprint "eagle-import:R0805")
      (libsource (lib "eagle-import") (part "R-EU_R0805"))
    )
    (comp (ref "R15")
      (value "220")
      (footprint "eagle-import:R0805")
      (libsource (lib "eagle-import") (part "R-EU_R0805"))
    )
    (comp (ref "S1")
      (value "SM-3TW102")
      (footprint "eagle-import:SM3TW102")
      (fields (field (name "MOUSER_PART_NUMBER") "229-SM-3TW102"))
      (libsource (lib "eagle-import") (part "SM-3TW102"))
    )
    (comp (ref "S2")
      (value "SM-3TW102")
      (footprint "eagle-import:SM3TW102")
      (fields (field (name "MOUSER_PART_NUMBER") "229-SM-3TW102"))
      (libsource (lib "eagle-import") (part "SM-3TW102"))
    )
    (comp (ref "U3")
      (value "TLV3501AID")
      (footprint "eagle-import:D8")
      (fields (field (name "COPYRIGHT") "Copyright (C) 2022 Ultra Librarian. All rights reserved."))
      (libsource (lib "eagle-import") (part "TLV3501AID"))
    )
    (comp (ref "U4")
      (value "TLV3501AID")
      (footprint "eagle-import:D8")
      (fields (field (name "COPYRIGHT") "Copyright (C) 2022 Ultra Librarian. All rights reserved."))
      (libsource (lib "eagle-import") (part "TLV3501AID"))
    )
    (comp (ref "C20")
      (value "0.1uF")
      (footprint "eagle-import:C0805")
      (libsource (lib "eagle-import") (part "C-EUC0805"))
    )
    (comp (ref "C21")
      (value "0.1uF")
      (footprint "eagle-import:C0805")
      (libsource (lib "eagle-import") (part "C-EUC0805"))
    )
    (comp (ref "C22")
      (value "2.2uF")
      (footprint "eagle-import:C0805")
      (libsource (lib "eagle-import") (part "C-EUC0805"))
    )
    (comp (ref "C23")
      (value "2.2uF")
      (footprint "eagle-import:C0805")
      (libsource (lib "eagle-import") (part "C-EUC0805"))
    )
    (comp (ref "JP_DRAIN2")
      (value "PINHD-1X1")
      (footprint "eagle-import:1X01")
      (libsource (lib "eagle-import") (part "PINHD-1X1"))
    )
    (comp (ref "JP_FPGA14")
      (value "PINHD-1X1")
      (footprint "eagle-import:1X01")
      (libsource (lib "eagle-import") (part "PINHD-1X1"))
    )
    (comp (ref "JP_GATE14")
      (value "PINHD-1X1")
      (footprint "eagle-import:1X01")
      (libsource (lib "eagle-import") (part "PINHD-1X1"))
    )
    (comp (ref "JP_MIPS14")
      (value "PINHD-1X1")
      (footprint "eagle-import:1X01")
      (libsource (lib "eagle-import") (part "PINHD-1X1"))
    )
    (comp (ref "R25")
      (value "130")
      (footprint "eagle-import:R0805")
      (libsource (lib "eagle-import") (part "R-EU_R0805"))
    )
    (comp (ref "R26")
      (value "130")
      (footprint "eagle-import:R0603")
      (libsource (lib "eagle-import") (part "R-EU_R0603"))
    )
    (comp (ref "R27")
      (value "220")
      (footprint "eagle-import:R0805")
      (libsource (lib "eagle-import") (part "R-EU_R0805"))
    )
    (comp (ref "R28")
      (value "220")
      (footprint "eagle-import:R0805")
      (libsource (lib "eagle-import") (part "R-EU_R0805"))
    )
    (comp (ref "R29")
      (value "130")
      (footprint "eagle-import:R0805")
      (libsource (lib "eagle-import") (part "R-EU_R0805"))
    )
    (comp (ref "R30")
      (value "220")
      (footprint "eagle-import:R0805")
      (libsource (lib "eagle-import") (part "R-EU_R0805"))
    )
    (comp (ref "R31")
      (value "130")
      (footprint "eagle-import:R0805")
      (libsource (lib "eagle-import") (part "R-EU_R0805"))
    )
    (comp (ref "R32")
      (value "220")
      (footprint "eagle-import:R0805")
      (libsource (lib "eagle-import") (part "R-EU_R0805"))
    )
    (comp (ref "R33")
      (value "220")
      (footprint "eagle-import:R0805")
      (libsource (lib "eagle-import") (part "R-EU_R0805"))
    )
    (comp (ref "S5")
      (value "SM-3TW102")
      (footprint "eagle-import:SM3TW102")
      (fields (field (name "MOUSER_PART_NUMBER") "229-SM-3TW102"))
      (libsource (lib "eagle-import") (part "SM-3TW102"))
    )
    (comp (ref "S6")
      (value "SM-3TW102")
      (footprint "eagle-import:SM3TW102")
      (fields (field (name "MOUSER_PART_NUMBER") "229-SM-3TW102"))
      (libsource (lib "eagle-import") (part "SM-3TW102"))
    )
    (comp (ref "U7")
      (value "TLV3501AID")
      (footprint "eagle-import:D8")
      (fields (field (name "COPYRIGHT") "Copyright (C) 2022 Ultra Librarian. All rights reserved."))
      (libsource (lib "eagle-import") (part "TLV3501AID"))
    )
    (comp (ref "U8")
      (value "TLV3501AID")
      (footprint "eagle-import:D8")
      (fields (field (name "COPYRIGHT") "Copyright (C) 2022 Ultra Librarian. All rights reserved."))
      (libsource (lib "eagle-import") (part "TLV3501AID"))
    )
    (comp (ref "C72")
      (value "0.1uF")
      (footprint "eagle-import:C0805")
      (libsource (lib "eagle-import") (part "C-EUC0805"))
    )
    (comp (ref "C73")
      (value "0.1uF")
      (footprint "eagle-import:C0805")
      (libsource (lib "eagle-import") (part "C-EUC0805"))
    )
    (comp (ref "C74")
      (value "2.2uF")
      (footprint "eagle-import:C0805")
      (libsource (lib "eagle-import") (part "C-EUC0805"))
    )
    (comp (ref "C75")
      (value "2.2uF")
      (footprint "eagle-import:C0805")
      (libsource (lib "eagle-import") (part "C-EUC0805"))
    )
    (comp (ref "JP_DRAIN15")
      (value "PINHD-1X1")
      (footprint "eagle-import:1X01")
      (libsource (lib "eagle-import") (part "PINHD-1X1"))
    )
    (comp (ref "JP_FPGA1")
      (value "PINHD-1X1")
      (footprint "eagle-import:1X01")
      (libsource (lib "eagle-import") (part "PINHD-1X1"))
    )
    (comp (ref "JP_GATE1")
      (value "PINHD-1X1")
      (footprint "eagle-import:1X01")
      (libsource (lib "eagle-import") (part "PINHD-1X1"))
    )
    (comp (ref "JP_MIPS1")
      (value "PINHD-1X1")
      (footprint "eagle-import:1X01")
      (libsource (lib "eagle-import") (part "PINHD-1X1"))
    )
    (comp (ref "R142")
      (value "130")
      (footprint "eagle-import:R0805")
      (libsource (lib "eagle-import") (part "R-EU_R0805"))
    )
    (comp (ref "R143")
      (value "130")
      (footprint "eagle-import:R0603")
      (libsource (lib "eagle-import") (part "R-EU_R0603"))
    )
    (comp (ref "R144")
      (value "220")
      (footprint "eagle-import:R0805")
      (libsource (lib "eagle-import") (part "R-EU_R0805"))
    )
    (comp (ref "R145")
      (value "220")
      (footprint "eagle-import:R0805")
      (libsource (lib "eagle-import") (part "R-EU_R0805"))
    )
    (comp (ref "R146")
      (value "130")
      (footprint "eagle-import:R0805")
      (libsource (lib "eagle-import") (part "R-EU_R0805"))
    )
    (comp (ref "R147")
      (value "220")
      (footprint "eagle-import:R0805")
      (libsource (lib "eagle-import") (part "R-EU_R0805"))
    )
    (comp (ref "R148")
      (value "130")
      (footprint "eagle-import:R0805")
      (libsource (lib "eagle-import") (part "R-EU_R0805"))
    )
    (comp (ref "R149")
      (value "220")
      (footprint "eagle-import:R0805")
      (libsource (lib "eagle-import") (part "R-EU_R0805"))
    )
    (comp (ref "R150")
      (value "220")
      (footprint "eagle-import:R0805")
      (libsource (lib "eagle-import") (part "R-EU_R0805"))
    )
    (comp (ref "S31")
      (value "SM-3TW102")
      (footprint "eagle-import:SM3TW102")
      (fields (field (name "MOUSER_PART_NUMBER") "229-SM-3TW102"))
      (libsource (lib "eagle-import") (part "SM-3TW102"))
    )
    (comp (ref "S32")
      (value "SM-3TW102")
      (footprint "eagle-import:SM3TW102")
      (fields (field (name "MOUSER_PART_NUMBER") "229-SM-3TW102"))
      (libsource (lib "eagle-import") (part "SM-3TW102"))
    )
    (comp (ref "U33")
      (value "TLV3501AID")
      (footprint "eagle-import:D8")
      (fields (field (name "COPYRIGHT") "Copyright (C) 2022 Ultra Librarian. All rights reserved."))
      (libsource (lib "eagle-import") (part "TLV3501AID"))
    )
    (comp (ref "U34")
      (value "TLV3501AID")
      (footprint "eagle-import:D8")
      (fields (field (name "COPYRIGHT") "Copyright (C) 2022 Ultra Librarian. All rights reserved."))
      (libsource (lib "eagle-import") (part "TLV3501AID"))
    )
    (comp (ref "C60")
      (value "0.1uF")
      (footprint "eagle-import:C0805")
      (libsource (lib "eagle-import") (part "C-EUC0805"))
    )
    (comp (ref "C61")
      (value "0.1uF")
      (footprint "eagle-import:C0805")
      (libsource (lib "eagle-import") (part "C-EUC0805"))
    )
    (comp (ref "C62")
      (value "2.2uF")
      (footprint "eagle-import:C0805")
      (libsource (lib "eagle-import") (part "C-EUC0805"))
    )
    (comp (ref "C63")
      (value "2.2uF")
      (footprint "eagle-import:C0805")
      (libsource (lib "eagle-import") (part "C-EUC0805"))
    )
    (comp (ref "JP_DRAIN12")
      (value "PINHD-1X1")
      (footprint "eagle-import:1X01")
      (libsource (lib "eagle-import") (part "PINHD-1X1"))
    )
    (comp (ref "JP_FPGA4")
      (value "PINHD-1X1")
      (footprint "eagle-import:1X01")
      (libsource (lib "eagle-import") (part "PINHD-1X1"))
    )
    (comp (ref "JP_GATE4")
      (value "PINHD-1X1")
      (footprint "eagle-import:1X01")
      (libsource (lib "eagle-import") (part "PINHD-1X1"))
    )
    (comp (ref "JP_MIPS4")
      (value "PINHD-1X1")
      (footprint "eagle-import:1X01")
      (libsource (lib "eagle-import") (part "PINHD-1X1"))
    )
    (comp (ref "R115")
      (value "130")
      (footprint "eagle-import:R0805")
      (libsource (lib "eagle-import") (part "R-EU_R0805"))
    )
    (comp (ref "R116")
      (value "130")
      (footprint "eagle-import:R0603")
      (libsource (lib "eagle-import") (part "R-EU_R0603"))
    )
    (comp (ref "R117")
      (value "220")
      (footprint "eagle-import:R0805")
      (libsource (lib "eagle-import") (part "R-EU_R0805"))
    )
    (comp (ref "R118")
      (value "220")
      (footprint "eagle-import:R0805")
      (libsource (lib "eagle-import") (part "R-EU_R0805"))
    )
    (comp (ref "R119")
      (value "130")
      (footprint "eagle-import:R0805")
      (libsource (lib "eagle-import") (part "R-EU_R0805"))
    )
    (comp (ref "R120")
      (value "220")
      (footprint "eagle-import:R0805")
      (libsource (lib "eagle-import") (part "R-EU_R0805"))
    )
    (comp (ref "R121")
      (value "130")
      (footprint "eagle-import:R0805")
      (libsource (lib "eagle-import") (part "R-EU_R0805"))
    )
    (comp (ref "R122")
      (value "220")
      (footprint "eagle-import:R0805")
      (libsource (lib "eagle-import") (part "R-EU_R0805"))
    )
    (comp (ref "R123")
      (value "220")
      (footprint "eagle-import:R0805")
      (libsource (lib "eagle-import") (part "R-EU_R0805"))
    )
    (comp (ref "S25")
      (value "SM-3TW102")
      (footprint "eagle-import:SM3TW102")
      (fields (field (name "MOUSER_PART_NUMBER") "229-SM-3TW102"))
      (libsource (lib "eagle-import") (part "SM-3TW102"))
    )
    (comp (ref "S26")
      (value "SM-3TW102")
      (footprint "eagle-import:SM3TW102")
      (fields (field (name "MOUSER_PART_NUMBER") "229-SM-3TW102"))
      (libsource (lib "eagle-import") (part "SM-3TW102"))
    )
    (comp (ref "U27")
      (value "TLV3501AID")
      (footprint "eagle-import:D8")
      (fields (field (name "COPYRIGHT") "Copyright (C) 2022 Ultra Librarian. All rights reserved."))
      (libsource (lib "eagle-import") (part "TLV3501AID"))
    )
    (comp (ref "U28")
      (value "TLV3501AID")
      (footprint "eagle-import:D8")
      (fields (field (name "COPYRIGHT") "Copyright (C) 2022 Ultra Librarian. All rights reserved."))
      (libsource (lib "eagle-import") (part "TLV3501AID"))
    )
    (comp (ref "C32")
      (value "0.1uF")
      (footprint "eagle-import:C0805")
      (libsource (lib "eagle-import") (part "C-EUC0805"))
    )
    (comp (ref "C33")
      (value "0.1uF")
      (footprint "eagle-import:C0805")
      (libsource (lib "eagle-import") (part "C-EUC0805"))
    )
    (comp (ref "C34")
      (value "2.2uF")
      (footprint "eagle-import:C0805")
      (libsource (lib "eagle-import") (part "C-EUC0805"))
    )
    (comp (ref "C35")
      (value "2.2uF")
      (footprint "eagle-import:C0805")
      (libsource (lib "eagle-import") (part "C-EUC0805"))
    )
    (comp (ref "JP_DRAIN5")
      (value "PINHD-1X1")
      (footprint "eagle-import:1X01")
      (libsource (lib "eagle-import") (part "PINHD-1X1"))
    )
    (comp (ref "JP_FPGA11")
      (value "PINHD-1X1")
      (footprint "eagle-import:1X01")
      (libsource (lib "eagle-import") (part "PINHD-1X1"))
    )
    (comp (ref "JP_GATE11")
      (value "PINHD-1X1")
      (footprint "eagle-import:1X01")
      (libsource (lib "eagle-import") (part "PINHD-1X1"))
    )
    (comp (ref "JP_MIPS11")
      (value "PINHD-1X1")
      (footprint "eagle-import:1X01")
      (libsource (lib "eagle-import") (part "PINHD-1X1"))
    )
    (comp (ref "R52")
      (value "130")
      (footprint "eagle-import:R0805")
      (libsource (lib "eagle-import") (part "R-EU_R0805"))
    )
    (comp (ref "R53")
      (value "130")
      (footprint "eagle-import:R0603")
      (libsource (lib "eagle-import") (part "R-EU_R0603"))
    )
    (comp (ref "R54")
      (value "220")
      (footprint "eagle-import:R0805")
      (libsource (lib "eagle-import") (part "R-EU_R0805"))
    )
    (comp (ref "R55")
      (value "220")
      (footprint "eagle-import:R0805")
      (libsource (lib "eagle-import") (part "R-EU_R0805"))
    )
    (comp (ref "R56")
      (value "130")
      (footprint "eagle-import:R0805")
      (libsource (lib "eagle-import") (part "R-EU_R0805"))
    )
    (comp (ref "R57")
      (value "220")
      (footprint "eagle-import:R0805")
      (libsource (lib "eagle-import") (part "R-EU_R0805"))
    )
    (comp (ref "R58")
      (value "130")
      (footprint "eagle-import:R0805")
      (libsource (lib "eagle-import") (part "R-EU_R0805"))
    )
    (comp (ref "R59")
      (value "220")
      (footprint "eagle-import:R0805")
      (libsource (lib "eagle-import") (part "R-EU_R0805"))
    )
    (comp (ref "R60")
      (value "220")
      (footprint "eagle-import:R0805")
      (libsource (lib "eagle-import") (part "R-EU_R0805"))
    )
    (comp (ref "S11")
      (value "SM-3TW102")
      (footprint "eagle-import:SM3TW102")
      (fields (field (name "MOUSER_PART_NUMBER") "229-SM-3TW102"))
      (libsource (lib "eagle-import") (part "SM-3TW102"))
    )
    (comp (ref "S12")
      (value "SM-3TW102")
      (footprint "eagle-import:SM3TW102")
      (fields (field (name "MOUSER_PART_NUMBER") "229-SM-3TW102"))
      (libsource (lib "eagle-import") (part "SM-3TW102"))
    )
    (comp (ref "U13")
      (value "TLV3501AID")
      (footprint "eagle-import:D8")
      (fields (field (name "COPYRIGHT") "Copyright (C) 2022 Ultra Librarian. All rights reserved."))
      (libsource (lib "eagle-import") (part "TLV3501AID"))
    )
    (comp (ref "U14")
      (value "TLV3501AID")
      (footprint "eagle-import:D8")
      (fields (field (name "COPYRIGHT") "Copyright (C) 2022 Ultra Librarian. All rights reserved."))
      (libsource (lib "eagle-import") (part "TLV3501AID"))
    )
    (comp (ref "C52")
      (value "0.1uF")
      (footprint "eagle-import:C0805")
      (libsource (lib "eagle-import") (part "C-EUC0805"))
    )
    (comp (ref "C53")
      (value "0.1uF")
      (footprint "eagle-import:C0805")
      (libsource (lib "eagle-import") (part "C-EUC0805"))
    )
    (comp (ref "C54")
      (value "2.2uF")
      (footprint "eagle-import:C0805")
      (libsource (lib "eagle-import") (part "C-EUC0805"))
    )
    (comp (ref "C55")
      (value "2.2uF")
      (footprint "eagle-import:C0805")
      (libsource (lib "eagle-import") (part "C-EUC0805"))
    )
    (comp (ref "JP_DRAIN10")
      (value "PINHD-1X1")
      (footprint "eagle-import:1X01")
      (libsource (lib "eagle-import") (part "PINHD-1X1"))
    )
    (comp (ref "JP_FPGA6")
      (value "PINHD-1X1")
      (footprint "eagle-import:1X01")
      (libsource (lib "eagle-import") (part "PINHD-1X1"))
    )
    (comp (ref "JP_GATE6")
      (value "PINHD-1X1")
      (footprint "eagle-import:1X01")
      (libsource (lib "eagle-import") (part "PINHD-1X1"))
    )
    (comp (ref "JP_MIPS6")
      (value "PINHD-1X1")
      (footprint "eagle-import:1X01")
      (libsource (lib "eagle-import") (part "PINHD-1X1"))
    )
    (comp (ref "R97")
      (value "130")
      (footprint "eagle-import:R0805")
      (libsource (lib "eagle-import") (part "R-EU_R0805"))
    )
    (comp (ref "R98")
      (value "130")
      (footprint "eagle-import:R0603")
      (libsource (lib "eagle-import") (part "R-EU_R0603"))
    )
    (comp (ref "R99")
      (value "220")
      (footprint "eagle-import:R0805")
      (libsource (lib "eagle-import") (part "R-EU_R0805"))
    )
    (comp (ref "R100")
      (value "220")
      (footprint "eagle-import:R0805")
      (libsource (lib "eagle-import") (part "R-EU_R0805"))
    )
    (comp (ref "R101")
      (value "130")
      (footprint "eagle-import:R0805")
      (libsource (lib "eagle-import") (part "R-EU_R0805"))
    )
    (comp (ref "R102")
      (value "220")
      (footprint "eagle-import:R0805")
      (libsource (lib "eagle-import") (part "R-EU_R0805"))
    )
    (comp (ref "R103")
      (value "130")
      (footprint "eagle-import:R0805")
      (libsource (lib "eagle-import") (part "R-EU_R0805"))
    )
    (comp (ref "R104")
      (value "220")
      (footprint "eagle-import:R0805")
      (libsource (lib "eagle-import") (part "R-EU_R0805"))
    )
    (comp (ref "R105")
      (value "220")
      (footprint "eagle-import:R0805")
      (libsource (lib "eagle-import") (part "R-EU_R0805"))
    )
    (comp (ref "S21")
      (value "SM-3TW102")
      (footprint "eagle-import:SM3TW102")
      (fields (field (name "MOUSER_PART_NUMBER") "229-SM-3TW102"))
      (libsource (lib "eagle-import") (part "SM-3TW102"))
    )
    (comp (ref "S22")
      (value "SM-3TW102")
      (footprint "eagle-import:SM3TW102")
      (fields (field (name "MOUSER_PART_NUMBER") "229-SM-3TW102"))
      (libsource (lib "eagle-import") (part "SM-3TW102"))
    )
    (comp (ref "U23")
      (value "TLV3501AID")
      (footprint "eagle-import:D8")
      (fields (field (name "COPYRIGHT") "Copyright (C) 2022 Ultra Librarian. All rights reserved."))
      (libsource (lib "eagle-import") (part "TLV3501AID"))
    )
    (comp (ref "U24")
      (value "TLV3501AID")
      (footprint "eagle-import:D8")
      (fields (field (name "COPYRIGHT") "Copyright (C) 2022 Ultra Librarian. All rights reserved."))
      (libsource (lib "eagle-import") (part "TLV3501AID"))
    )
    (comp (ref "C68")
      (value "0.1uF")
      (footprint "eagle-import:C0805")
      (libsource (lib "eagle-import") (part "C-EUC0805"))
    )
    (comp (ref "C69")
      (value "0.1uF")
      (footprint "eagle-import:C0805")
      (libsource (lib "eagle-import") (part "C-EUC0805"))
    )
    (comp (ref "C70")
      (value "2.2uF")
      (footprint "eagle-import:C0805")
      (libsource (lib "eagle-import") (part "C-EUC0805"))
    )
    (comp (ref "C71")
      (value "2.2uF")
      (footprint "eagle-import:C0805")
      (libsource (lib "eagle-import") (part "C-EUC0805"))
    )
    (comp (ref "JP_DRAIN14")
      (value "PINHD-1X1")
      (footprint "eagle-import:1X01")
      (libsource (lib "eagle-import") (part "PINHD-1X1"))
    )
    (comp (ref "JP_FPGA2")
      (value "PINHD-1X1")
      (footprint "eagle-import:1X01")
      (libsource (lib "eagle-import") (part "PINHD-1X1"))
    )
    (comp (ref "JP_GATE2")
      (value "PINHD-1X1")
      (footprint "eagle-import:1X01")
      (libsource (lib "eagle-import") (part "PINHD-1X1"))
    )
    (comp (ref "JP_MIPS2")
      (value "PINHD-1X1")
      (footprint "eagle-import:1X01")
      (libsource (lib "eagle-import") (part "PINHD-1X1"))
    )
    (comp (ref "R133")
      (value "130")
      (footprint "eagle-import:R0805")
      (libsource (lib "eagle-import") (part "R-EU_R0805"))
    )
    (comp (ref "R134")
      (value "130")
      (footprint "eagle-import:R0603")
      (libsource (lib "eagle-import") (part "R-EU_R0603"))
    )
    (comp (ref "R135")
      (value "220")
      (footprint "eagle-import:R0805")
      (libsource (lib "eagle-import") (part "R-EU_R0805"))
    )
    (comp (ref "R136")
      (value "220")
      (footprint "eagle-import:R0805")
      (libsource (lib "eagle-import") (part "R-EU_R0805"))
    )
    (comp (ref "R137")
      (value "130")
      (footprint "eagle-import:R0805")
      (libsource (lib "eagle-import") (part "R-EU_R0805"))
    )
    (comp (ref "R138")
      (value "220")
      (footprint "eagle-import:R0805")
      (libsource (lib "eagle-import") (part "R-EU_R0805"))
    )
    (comp (ref "R139")
      (value "130")
      (footprint "eagle-import:R0805")
      (libsource (lib "eagle-import") (part "R-EU_R0805"))
    )
    (comp (ref "R140")
      (value "220")
      (footprint "eagle-import:R0805")
      (libsource (lib "eagle-import") (part "R-EU_R0805"))
    )
    (comp (ref "R141")
      (value "220")
      (footprint "eagle-import:R0805")
      (libsource (lib "eagle-import") (part "R-EU_R0805"))
    )
    (comp (ref "S29")
      (value "SM-3TW102")
      (footprint "eagle-import:SM3TW102")
      (fields (field (name "MOUSER_PART_NUMBER") "229-SM-3TW102"))
      (libsource (lib "eagle-import") (part "SM-3TW102"))
    )
    (comp (ref "S30")
      (value "SM-3TW102")
      (footprint "eagle-import:SM3TW102")
      (fields (field (name "MOUSER_PART_NUMBER") "229-SM-3TW102"))
      (libsource (lib "eagle-import") (part "SM-3TW102"))
    )
    (comp (ref "U31")
      (value "TLV3501AID")
      (footprint "eagle-import:D8")
      (fields (field (name "COPYRIGHT") "Copyright (C) 2022 Ultra Librarian. All rights reserved."))
      (libsource (lib "eagle-import") (part "TLV3501AID"))
    )
    (comp (ref "U32")
      (value "TLV3501AID")
      (footprint "eagle-import:D8")
      (fields (field (name "COPYRIGHT") "Copyright (C) 2022 Ultra Librarian. All rights reserved."))
      (libsource (lib "eagle-import") (part "TLV3501AID"))
    )
    (comp (ref "C36")
      (value "0.1uF")
      (footprint "eagle-import:C0805")
      (libsource (lib "eagle-import") (part "C-EUC0805"))
    )
    (comp (ref "C37")
      (value "0.1uF")
      (footprint "eagle-import:C0805")
      (libsource (lib "eagle-import") (part "C-EUC0805"))
    )
    (comp (ref "C38")
      (value "2.2uF")
      (footprint "eagle-import:C0805")
      (libsource (lib "eagle-import") (part "C-EUC0805"))
    )
    (comp (ref "C39")
      (value "2.2uF")
      (footprint "eagle-import:C0805")
      (libsource (lib "eagle-import") (part "C-EUC0805"))
    )
    (comp (ref "JP_DRAIN6")
      (value "PINHD-1X1")
      (footprint "eagle-import:1X01")
      (libsource (lib "eagle-import") (part "PINHD-1X1"))
    )
    (comp (ref "JP_FPGA10")
      (value "PINHD-1X1")
      (footprint "eagle-import:1X01")
      (libsource (lib "eagle-import") (part "PINHD-1X1"))
    )
    (comp (ref "JP_GATE10")
      (value "PINHD-1X1")
      (footprint "eagle-import:1X01")
      (libsource (lib "eagle-import") (part "PINHD-1X1"))
    )
    (comp (ref "JP_MIPS10")
      (value "PINHD-1X1")
      (footprint "eagle-import:1X01")
      (libsource (lib "eagle-import") (part "PINHD-1X1"))
    )
    (comp (ref "R61")
      (value "130")
      (footprint "eagle-import:R0805")
      (libsource (lib "eagle-import") (part "R-EU_R0805"))
    )
    (comp (ref "R62")
      (value "130")
      (footprint "eagle-import:R0603")
      (libsource (lib "eagle-import") (part "R-EU_R0603"))
    )
    (comp (ref "R63")
      (value "220")
      (footprint "eagle-import:R0805")
      (libsource (lib "eagle-import") (part "R-EU_R0805"))
    )
    (comp (ref "R64")
      (value "220")
      (footprint "eagle-import:R0805")
      (libsource (lib "eagle-import") (part "R-EU_R0805"))
    )
    (comp (ref "R65")
      (value "130")
      (footprint "eagle-import:R0805")
      (libsource (lib "eagle-import") (part "R-EU_R0805"))
    )
    (comp (ref "R66")
      (value "220")
      (footprint "eagle-import:R0805")
      (libsource (lib "eagle-import") (part "R-EU_R0805"))
    )
    (comp (ref "R67")
      (value "130")
      (footprint "eagle-import:R0805")
      (libsource (lib "eagle-import") (part "R-EU_R0805"))
    )
    (comp (ref "R68")
      (value "220")
      (footprint "eagle-import:R0805")
      (libsource (lib "eagle-import") (part "R-EU_R0805"))
    )
    (comp (ref "R69")
      (value "220")
      (footprint "eagle-import:R0805")
      (libsource (lib "eagle-import") (part "R-EU_R0805"))
    )
    (comp (ref "S13")
      (value "SM-3TW102")
      (footprint "eagle-import:SM3TW102")
      (fields (field (name "MOUSER_PART_NUMBER") "229-SM-3TW102"))
      (libsource (lib "eagle-import") (part "SM-3TW102"))
    )
    (comp (ref "S14")
      (value "SM-3TW102")
      (footprint "eagle-import:SM3TW102")
      (fields (field (name "MOUSER_PART_NUMBER") "229-SM-3TW102"))
      (libsource (lib "eagle-import") (part "SM-3TW102"))
    )
    (comp (ref "U15")
      (value "TLV3501AID")
      (footprint "eagle-import:D8")
      (fields (field (name "COPYRIGHT") "Copyright (C) 2022 Ultra Librarian. All rights reserved."))
      (libsource (lib "eagle-import") (part "TLV3501AID"))
    )
    (comp (ref "U16")
      (value "TLV3501AID")
      (footprint "eagle-import:D8")
      (fields (field (name "COPYRIGHT") "Copyright (C) 2022 Ultra Librarian. All rights reserved."))
      (libsource (lib "eagle-import") (part "TLV3501AID"))
    )
  )
  (nets
    (net (code "1") (name "+1.5V") (class "Default")
      (node (ref "+1.5V_TP1") (pin "1") (pinfunction "1_1") (pintype "passive"))
      (node (ref "+1.5V_TP2") (pin "1") (pinfunction "1_1") (pintype "passive"))
      (node (ref "C13") (pin "2") (pinfunction "2_2") (pintype "passive"))
      (node (ref "C15") (pin "2") (pinfunction "2_2") (pintype "passive"))
      (node (ref "C20") (pin "2") (pinfunction "2_2") (pintype "passive"))
      (node (ref "C22") (pin "2") (pinfunction "2_2") (pintype "passive"))
      (node (ref "C24") (pin "2") (pinfunction "2_2") (pintype "passive"))
      (node (ref "C26") (pin "2") (pinfunction "2_2") (pintype "passive"))
      (node (ref "C28") (pin "2") (pinfunction "2_2") (pintype "passive"))
      (node (ref "C30") (pin "2") (pinfunction "2_2") (pintype "passive"))
      (node (ref "C32") (pin "2") (pinfunction "2_2") (pintype "passive"))
      (node (ref "C34") (pin "2") (pinfunction "2_2") (pintype "passive"))
      (node (ref "C36") (pin "2") (pinfunction "2_2") (pintype "passive"))
      (node (ref "C38") (pin "2") (pinfunction "2_2") (pintype "passive"))
      (node (ref "C4") (pin "+") (pinfunction "+_+") (pintype "passive"))
      (node (ref "C40") (pin "2") (pinfunction "2_2") (pintype "passive"))
      (node (ref "C42") (pin "2") (pinfunction "2_2") (pintype "passive"))
      (node (ref "C44") (pin "2") (pinfunction "2_2") (pintype "passive"))
      (node (ref "C46") (pin "2") (pinfunction "2_2") (pintype "passive"))
      (node (ref "C48") (pin "2") (pinfunction "2_2") (pintype "passive"))
      (node (ref "C50") (pin "2") (pinfunction "2_2") (pintype "passive"))
      (node (ref "C52") (pin "2") (pinfunction "2_2") (pintype "passive"))
      (node (ref "C54") (pin "2") (pinfunction "2_2") (pintype "passive"))
      (node (ref "C56") (pin "2") (pinfunction "2_2") (pintype "passive"))
      (node (ref "C58") (pin "2") (pinfunction "2_2") (pintype "passive"))
      (node (ref "C6") (pin "2") (pinfunction "2_2") (pintype "passive"))
      (node (ref "C60") (pin "2") (pinfunction "2_2") (pintype "passive"))
      (node (ref "C62") (pin "2") (pinfunction "2_2") (pintype "passive"))
      (node (ref "C64") (pin "2") (pinfunction "2_2") (pintype "passive"))
      (node (ref "C66") (pin "2") (pinfunction "2_2") (pintype "passive"))
      (node (ref "C68") (pin "2") (pinfunction "2_2") (pintype "passive"))
      (node (ref "C70") (pin "2") (pinfunction "2_2") (pintype "passive"))
      (node (ref "C72") (pin "2") (pinfunction "2_2") (pintype "passive"))
      (node (ref "C74") (pin "2") (pinfunction "2_2") (pintype "passive"))
      (node (ref "C8") (pin "2") (pinfunction "2_2") (pintype "passive"))
      (node (ref "C86") (pin "2") (pinfunction "2_2") (pintype "passive"))
      (node (ref "C87") (pin "2") (pinfunction "2_2") (pintype "passive"))
      (node (ref "D3") (pin "A") (pinfunction "A_A") (pintype "passive"))
      (node (ref "D4") (pin "C") (pinfunction "C_C") (pintype "passive"))
      (node (ref "IC3") (pin "4") (pinfunction "VOUT_4") (pintype "output"))
      (node (ref "R9") (pin "2") (pinfunction "2_2") (pintype "passive"))
      (node (ref "S1") (pin "1") (pinfunction "CCW_1") (pintype "bidirectional"))
      (node (ref "S10") (pin "1") (pinfunction "CCW_1") (pintype "bidirectional"))
      (node (ref "S11") (pin "1") (pinfunction "CCW_1") (pintype "bidirectional"))
      (node (ref "S12") (pin "1") (pinfunction "CCW_1") (pintype "bidirectional"))
      (node (ref "S13") (pin "1") (pinfunction "CCW_1") (pintype "bidirectional"))
      (node (ref "S14") (pin "1") (pinfunction "CCW_1") (pintype "bidirectional"))
      (node (ref "S15") (pin "1") (pinfunction "CCW_1") (pintype "bidirectional"))
      (node (ref "S16") (pin "1") (pinfunction "CCW_1") (pintype "bidirectional"))
      (node (ref "S17") (pin "1") (pinfunction "CCW_1") (pintype "bidirectional"))
      (node (ref "S18") (pin "1") (pinfunction "CCW_1") (pintype "bidirectional"))
      (node (ref "S19") (pin "1") (pinfunction "CCW_1") (pintype "bidirectional"))
      (node (ref "S2") (pin "1") (pinfunction "CCW_1") (pintype "bidirectional"))
      (node (ref "S20") (pin "1") (pinfunction "CCW_1") (pintype "bidirectional"))
      (node (ref "S21") (pin "1") (pinfunction "CCW_1") (pintype "bidirectional"))
      (node (ref "S22") (pin "1") (pinfunction "CCW_1") (pintype "bidirectional"))
      (node (ref "S23") (pin "1") (pinfunction "CCW_1") (pintype "bidirectional"))
      (node (ref "S24") (pin "1") (pinfunction "CCW_1") (pintype "bidirectional"))
      (node (ref "S25") (pin "1") (pinfunction "CCW_1") (pintype "bidirectional"))
      (node (ref "S26") (pin "1") (pinfunction "CCW_1") (pintype "bidirectional"))
      (node (ref "S27") (pin "1") (pinfunction "CCW_1") (pintype "bidirectional"))
      (node (ref "S28") (pin "1") (pinfunction "CCW_1") (pintype "bidirectional"))
      (node (ref "S29") (pin "1") (pinfunction "CCW_1") (pintype "bidirectional"))
      (node (ref "S3") (pin "1") (pinfunction "CCW_1") (pintype "bidirectional"))
      (node (ref "S30") (pin "1") (pinfunction "CCW_1") (pintype "bidirectional"))
      (node (ref "S31") (pin "1") (pinfunction "CCW_1") (pintype "bidirectional"))
      (node (ref "S32") (pin "1") (pinfunction "CCW_1") (pintype "bidirectional"))
      (node (ref "S4") (pin "1") (pinfunction "CCW_1") (pintype "bidirectional"))
      (node (ref "S5") (pin "1") (pinfunction "CCW_1") (pintype "bidirectional"))
      (node (ref "S6") (pin "1") (pinfunction "CCW_1") (pintype "bidirectional"))
      (node (ref "S7") (pin "1") (pinfunction "CCW_1") (pintype "bidirectional"))
      (node (ref "S8") (pin "1") (pinfunction "CCW_1") (pintype "bidirectional"))
      (node (ref "S9") (pin "1") (pinfunction "CCW_1") (pintype "bidirectional"))
      (node (ref "U11") (pin "7") (pinfunction "V+_7") (pintype "power_in"))
      (node (ref "U13") (pin "7") (pinfunction "V+_7") (pintype "power_in"))
      (node (ref "U15") (pin "7") (pinfunction "V+_7") (pintype "power_in"))
      (node (ref "U17") (pin "7") (pinfunction "V+_7") (pintype "power_in"))
      (node (ref "U19") (pin "7") (pinfunction "V+_7") (pintype "power_in"))
      (node (ref "U21") (pin "7") (pinfunction "V+_7") (pintype "power_in"))
      (node (ref "U23") (pin "7") (pinfunction "V+_7") (pintype "power_in"))
      (node (ref "U25") (pin "7") (pinfunction "V+_7") (pintype "power_in"))
      (node (ref "U27") (pin "7") (pinfunction "V+_7") (pintype "power_in"))
      (node (ref "U29") (pin "7") (pinfunction "V+_7") (pintype "power_in"))
      (node (ref "U3") (pin "7") (pinfunction "V+_7") (pintype "power_in"))
      (node (ref "U31") (pin "7") (pinfunction "V+_7") (pintype "power_in"))
      (node (ref "U33") (pin "7") (pinfunction "V+_7") (pintype "power_in"))
      (node (ref "U38") (pin "2") (pinfunction "SOURCE_2") (pintype "passive"))
      (node (ref "U40") (pin "7") (pinfunction "V+_7") (pintype "power_in"))
      (node (ref "U5") (pin "7") (pinfunction "V+_7") (pintype "power_in"))
      (node (ref "U7") (pin "7") (pinfunction "V+_7") (pintype "power_in"))
      (node (ref "U9") (pin "7") (pinfunction "V+_7") (pintype "power_in"))
    )
    (net (code "2") (name "+3V") (class "Default")
      (node (ref "+3V_TP1") (pin "1") (pinfunction "1_1") (pintype "passive"))
      (node (ref "+3V_TP2") (pin "1") (pinfunction "1_1") (pintype "passive"))
      (node (ref "C11") (pin "+") (pinfunction "+_+") (pintype "passive"))
      (node (ref "C14") (pin "1") (pinfunction "1_1") (pintype "passive"))
      (node (ref "C19") (pin "1") (pinfunction "1_1") (pintype "passive"))
      (node (ref "C21") (pin "1") (pinfunction "1_1") (pintype "passive"))
      (node (ref "C23") (pin "1") (pinfunction "1_1") (pintype "passive"))
      (node (ref "C25") (pin "1") (pinfunction "1_1") (pintype "passive"))
      (node (ref "C27") (pin "1") (pinfunction "1_1") (pintype "passive"))
      (node (ref "C29") (pin "1") (pinfunction "1_1") (pintype "passive"))
      (node (ref "C31") (pin "1") (pinfunction "1_1") (pintype "passive"))
      (node (ref "C33") (pin "1") (pinfunction "1_1") (pintype "passive"))
      (node (ref "C35") (pin "1") (pinfunction "1_1") (pintype "passive"))
      (node (ref "C37") (pin "1") (pinfunction "1_1") (pintype "passive"))
      (node (ref "C39") (pin "1") (pinfunction "1_1") (pintype "passive"))
      (node (ref "C41") (pin "1") (pinfunction "1_1") (pintype "passive"))
      (node (ref "C43") (pin "1") (pinfunction "1_1") (pintype "passive"))
      (node (ref "C45") (pin "1") (pinfunction "1_1") (pintype "passive"))
      (node (ref "C47") (pin "1") (pinfunction "1_1") (pintype "passive"))
      (node (ref "C49") (pin "1") (pinfunction "1_1") (pintype "passive"))
      (node (ref "C51") (pin "1") (pinfunction "1_1") (pintype "passive"))
      (node (ref "C53") (pin "1") (pinfunction "1_1") (pintype "passive"))
      (node (ref "C55") (pin "1") (pinfunction "1_1") (pintype "passive"))
      (node (ref "C57") (pin "1") (pinfunction "1_1") (pintype "passive"))
      (node (ref "C59") (pin "1") (pinfunction "1_1") (pintype "passive"))
      (node (ref "C61") (pin "1") (pinfunction "1_1") (pintype "passive"))
      (node (ref "C63") (pin "1") (pinfunction "1_1") (pintype "passive"))
      (node (ref "C65") (pin "1") (pinfunction "1_1") (pintype "passive"))
      (node (ref "C67") (pin "1") (pinfunction "1_1") (pintype "passive"))
      (node (ref "C69") (pin "1") (pinfunction "1_1") (pintype "passive"))
      (node (ref "C7") (pin "1") (pinfunction "1_1") (pintype "passive"))
      (node (ref "C71") (pin "1") (pinfunction "1_1") (pintype "passive"))
      (node (ref "C73") (pin "1") (pinfunction "1_1") (pintype "passive"))
      (node (ref "C75") (pin "1") (pinfunction "1_1") (pintype "passive"))
      (node (ref "C82") (pin "2") (pinfunction "2_2") (pintype "passive"))
      (node (ref "C83") (pin "2") (pinfunction "2_2") (pintype "passive"))
      (node (ref "C9") (pin "1") (pinfunction "1_1") (pintype "passive"))
      (node (ref "D7") (pin "A") (pinfunction "A_A") (pintype "passive"))
      (node (ref "D8") (pin "C") (pinfunction "C_C") (pintype "passive"))
      (node (ref "IC4") (pin "4") (pinfunction "VOUT_4") (pintype "output"))
      (node (ref "R11") (pin "2") (pinfunction "2_2") (pintype "passive"))
      (node (ref "U10") (pin "7") (pinfunction "V+_7") (pintype "power_in"))
      (node (ref "U12") (pin "7") (pinfunction "V+_7") (pintype "power_in"))
      (node (ref "U14") (pin "7") (pinfunction "V+_7") (pintype "power_in"))
      (node (ref "U16") (pin "7") (pinfunction "V+_7") (pintype "power_in"))
      (node (ref "U18") (pin "7") (pinfunction "V+_7") (pintype "power_in"))
      (node (ref "U20") (pin "7") (pinfunction "V+_7") (pintype "power_in"))
      (node (ref "U22") (pin "7") (pinfunction "V+_7") (pintype "power_in"))
      (node (ref "U24") (pin "7") (pinfunction "V+_7") (pintype "power_in"))
      (node (ref "U26") (pin "7") (pinfunction "V+_7") (pintype "power_in"))
      (node (ref "U28") (pin "7") (pinfunction "V+_7") (pintype "power_in"))
      (node (ref "U30") (pin "7") (pinfunction "V+_7") (pintype "power_in"))
      (node (ref "U32") (pin "7") (pinfunction "V+_7") (pintype "power_in"))
      (node (ref "U34") (pin "7") (pinfunction "V+_7") (pintype "power_in"))
      (node (ref "U39") (pin "7") (pinfunction "V+_7") (pintype "power_in"))
      (node (ref "U4") (pin "7") (pinfunction "V+_7") (pintype "power_in"))
      (node (ref "U6") (pin "7") (pinfunction "V+_7") (pintype "power_in"))
      (node (ref "U8") (pin "7") (pinfunction "V+_7") (pintype "power_in"))
    )
    (net (code "3") (name "-1.5V") (class "Default")
      (node (ref "-1.5V_TP1") (pin "1") (pinfunction "1_1") (pintype "passive"))
      (node (ref "-1.5V_TP2") (pin "1") (pinfunction "1_1") (pintype "passive"))
      (node (ref "C13") (pin "1") (pinfunction "1_1") (pintype "passive"))
      (node (ref "C15") (pin "1") (pinfunction "1_1") (pintype "passive"))
      (node (ref "C2") (pin "1") (pinfunction "1_1") (pintype "passive"))
      (node (ref "C20") (pin "1") (pinfunction "1_1") (pintype "passive"))
      (node (ref "C22") (pin "1") (pinfunction "1_1") (pintype "passive"))
      (node (ref "C24") (pin "1") (pinfunction "1_1") (pintype "passive"))
      (node (ref "C26") (pin "1") (pinfunction "1_1") (pintype "passive"))
      (node (ref "C28") (pin "1") (pinfunction "1_1") (pintype "passive"))
      (node (ref "C30") (pin "1") (pinfunction "1_1") (pintype "passive"))
      (node (ref "C32") (pin "1") (pinfunction "1_1") (pintype "passive"))
      (node (ref "C34") (pin "1") (pinfunction "1_1") (pintype "passive"))
      (node (ref "C36") (pin "1") (pinfunction "1_1") (pintype "passive"))
      (node (ref "C38") (pin "1") (pinfunction "1_1") (pintype "passive"))
      (node (ref "C40") (pin "1") (pinfunction "1_1") (pintype "passive"))
      (node (ref "C42") (pin "1") (pinfunction "1_1") (pintype "passive"))
      (node (ref "C44") (pin "1") (pinfunction "1_1") (pintype "passive"))
      (node (ref "C46") (pin "1") (pinfunction "1_1") (pintype "passive"))
      (node (ref "C48") (pin "1") (pinfunction "1_1") (pintype "passive"))
      (node (ref "C50") (pin "1") (pinfunction "1_1") (pintype "passive"))
      (node (ref "C52") (pin "1") (pinfunction "1_1") (pintype "passive"))
      (node (ref "C54") (pin "1") (pinfunction "1_1") (pintype "passive"))
      (node (ref "C56") (pin "1") (pinfunction "1_1") (pintype "passive"))
      (node (ref "C58") (pin "1") (pinfunction "1_1") (pintype "passive"))
      (node (ref "C6") (pin "1") (pinfunction "1_1") (pintype "passive"))
      (node (ref "C60") (pin "1") (pinfunction "1_1") (pintype "passive"))
      (node (ref "C62") (pin "1") (pinfunction "1_1") (pintype "passive"))
      (node (ref "C64") (pin "1") (pinfunction "1_1") (pintype "passive"))
      (node (ref "C66") (pin "1") (pinfunction "1_1") (pintype "passive"))
      (node (ref "C68") (pin "1") (pinfunction "1_1") (pintype "passive"))
      (node (ref "C70") (pin "1") (pinfunction "1_1") (pintype "passive"))
      (node (ref "C72") (pin "1") (pinfunction "1_1") (pintype "passive"))
      (node (ref "C74") (pin "1") (pinfunction "1_1") (pintype "passive"))
      (node (ref "C8") (pin "1") (pinfunction "1_1") (pintype "passive"))
      (node (ref "C84") (pin "1") (pinfunction "1_1") (pintype "passive"))
      (node (ref "C85") (pin "1") (pinfunction "1_1") (pintype "passive"))
      (node (ref "R151") (pin "2") (pinfunction "2_2") (pintype "passive"))
      (node (ref "S1") (pin "3") (pinfunction "CW_3") (pintype "bidirectional"))
      (node (ref "S11") (pin "3") (pinfunction "CW_3") (pintype "bidirectional"))
      (node (ref "S13") (pin "3") (pinfunction "CW_3") (pintype "bidirectional"))
      (node (ref "S15") (pin "3") (pinfunction "CW_3") (pintype "bidirectional"))
      (node (ref "S17") (pin "3") (pinfunction "CW_3") (pintype "bidirectional"))
      (node (ref "S19") (pin "3") (pinfunction "CW_3") (pintype "bidirectional"))
      (node (ref "S21") (pin "3") (pinfunction "CW_3") (pintype "bidirectional"))
      (node (ref "S23") (pin "3") (pinfunction "CW_3") (pintype "bidirectional"))
      (node (ref "S25") (pin "3") (pinfunction "CW_3") (pintype "bidirectional"))
      (node (ref "S27") (pin "3") (pinfunction "CW_3") (pintype "bidirectional"))
      (node (ref "S29") (pin "3") (pinfunction "CW_3") (pintype "bidirectional"))
      (node (ref "S3") (pin "3") (pinfunction "CW_3") (pintype "bidirectional"))
      (node (ref "S31") (pin "3") (pinfunction "CW_3") (pintype "bidirectional"))
      (node (ref "S5") (pin "3") (pinfunction "CW_3") (pintype "bidirectional"))
      (node (ref "S7") (pin "3") (pinfunction "CW_3") (pintype "bidirectional"))
      (node (ref "S9") (pin "3") (pinfunction "CW_3") (pintype "bidirectional"))
      (node (ref "U11") (pin "4") (pinfunction "V-_4") (pintype "power_in"))
      (node (ref "U13") (pin "4") (pinfunction "V-_4") (pintype "power_in"))
      (node (ref "U15") (pin "4") (pinfunction "V-_4") (pintype "power_in"))
      (node (ref "U17") (pin "4") (pinfunction "V-_4") (pintype "power_in"))
      (node (ref "U19") (pin "4") (pinfunction "V-_4") (pintype "power_in"))
      (node (ref "U2") (pin "3") (pinfunction "VOUT_3") (pintype "power_in"))
      (node (ref "U21") (pin "4") (pinfunction "V-_4") (pintype "power_in"))
      (node (ref "U23") (pin "4") (pinfunction "V-_4") (pintype "power_in"))
      (node (ref "U25") (pin "4") (pinfunction "V-_4") (pintype "power_in"))
      (node (ref "U27") (pin "4") (pinfunction "V-_4") (pintype "power_in"))
      (node (ref "U29") (pin "4") (pinfunction "V-_4") (pintype "power_in"))
      (node (ref "U3") (pin "4") (pinfunction "V-_4") (pintype "power_in"))
      (node (ref "U31") (pin "4") (pinfunction "V-_4") (pintype "power_in"))
      (node (ref "U33") (pin "4") (pinfunction "V-_4") (pintype "power_in"))
      (node (ref "U40") (pin "4") (pinfunction "V-_4") (pintype "power_in"))
      (node (ref "U40") (pin "8") (pinfunction "SHDN_8") (pintype "passive"))
      (node (ref "U5") (pin "4") (pinfunction "V-_4") (pintype "power_in"))
      (node (ref "U7") (pin "4") (pinfunction "V-_4") (pintype "power_in"))
      (node (ref "U9") (pin "4") (pinfunction "V-_4") (pintype "power_in"))
    )
    (net (code "4") (name "DIR_GATE") (class "Default")
      (node (ref "GATE_TP1") (pin "1") (pinfunction "1_1") (pintype "passive"))
      (node (ref "JP_GATE1") (pin "1") (pinfunction "1_1") (pintype "passive"))
      (node (ref "JP_GATE10") (pin "1") (pinfunction "1_1") (pintype "passive"))
      (node (ref "JP_GATE11") (pin "1") (pinfunction "1_1") (pintype "passive"))
      (node (ref "JP_GATE12") (pin "1") (pinfunction "1_1") (pintype "passive"))
      (node (ref "JP_GATE13") (pin "1") (pinfunction "1_1") (pintype "passive"))
      (node (ref "JP_GATE14") (pin "1") (pinfunction "1_1") (pintype "passive"))
      (node (ref "JP_GATE16") (pin "1") (pinfunction "1_1") (pintype "passive"))
      (node (ref "JP_GATE2") (pin "1") (pinfunction "1_1") (pintype "passive"))
      (node (ref "JP_GATE3") (pin "1") (pinfunction "1_1") (pintype "passive"))
      (node (ref "JP_GATE4") (pin "1") (pinfunction "1_1") (pintype "passive"))
      (node (ref "JP_GATE5") (pin "1") (pinfunction "1_1") (pintype "passive"))
      (node (ref "JP_GATE6") (pin "1") (pinfunction "1_1") (pintype "passive"))
      (node (ref "JP_GATE7") (pin "1") (pinfunction "1_1") (pintype "passive"))
      (node (ref "JP_GATE8") (pin "1") (pinfunction "1_1") (pintype "passive"))
      (node (ref "JP_GATE9") (pin "1") (pinfunction "1_1") (pintype "passive"))
      (node (ref "JP_GATEP15") (pin "1") (pinfunction "1_1") (pintype "passive"))
      (node (ref "R105") (pin "2") (pinfunction "2_2") (pintype "passive"))
      (node (ref "R114") (pin "2") (pinfunction "2_2") (pintype "passive"))
      (node (ref "R123") (pin "2") (pinfunction "2_2") (pintype "passive"))
      (node (ref "R132") (pin "2") (pinfunction "2_2") (pintype "passive"))
      (node (ref "R141") (pin "2") (pinfunction "2_2") (pintype "passive"))
      (node (ref "R15") (pin "2") (pinfunction "2_2") (pintype "passive"))
      (node (ref "R150") (pin "2") (pinfunction "2_2") (pintype "passive"))
      (node (ref "R165") (pin "1") (pinfunction "1_1") (pintype "passive"))
      (node (ref "R24") (pin "2") (pinfunction "2_2") (pintype "passive"))
      (node (ref "R33") (pin "2") (pinfunction "2_2") (pintype "passive"))
      (node (ref "R42") (pin "2") (pinfunction "2_2") (pintype "passive"))
      (node (ref "R51") (pin "2") (pinfunction "2_2") (pintype "passive"))
      (node (ref "R60") (pin "2") (pinfunction "2_2") (pintype "passive"))
      (node (ref "R69") (pin "2") (pinfunction "2_2") (pintype "passive"))
      (node (ref "R78") (pin "2") (pinfunction "2_2") (pintype "passive"))
      (node (ref "R87") (pin "2") (pinfunction "2_2") (pintype "passive"))
      (node (ref "R96") (pin "2") (pinfunction "2_2") (pintype "passive"))
      (node (ref "U40") (pin "6") (pinfunction "OUT_6") (pintype "output"))
    )
    (net (code "5") (name "F1") (class "Default")
      (node (ref "J2") (pin "1") (pinfunction "1_1") (pintype "bidirectional"))
      (node (ref "JP_FPGA1") (pin "1") (pinfunction "1_1") (pintype "passive"))
      (node (ref "R143") (pin "1") (pinfunction "1_1") (pintype "passive"))
      (node (ref "R144") (pin "2") (pinfunction "2_2") (pintype "passive"))
      (node (ref "R145") (pin "1") (pinfunction "1_1") (pintype "passive"))
    )
    (net (code "6") (name "F2") (class "Default")
      (node (ref "J2") (pin "2") (pinfunction "2_2") (pintype "bidirectional"))
      (node (ref "JP_FPGA2") (pin "1") (pinfunction "1_1") (pintype "passive"))
      (node (ref "R134") (pin "1") (pinfunction "1_1") (pintype "passive"))
      (node (ref "R135") (pin "2") (pinfunction "2_2") (pintype "passive"))
      (node (ref "R136") (pin "1") (pinfunction "1_1") (pintype "passive"))
    )
    (net (code "7") (name "F3") (class "Default")
      (node (ref "J2") (pin "3") (pinfunction "3_3") (pintype "bidirectional"))
      (node (ref "JP_FPGA3") (pin "1") (pinfunction "1_1") (pintype "passive"))
      (node (ref "R125") (pin "1") (pinfunction "1_1") (pintype "passive"))
      (node (ref "R126") (pin "2") (pinfunction "2_2") (pintype "passive"))
      (node (ref "R127") (pin "1") (pinfunction "1_1") (pintype "passive"))
    )
    (net (code "8") (name "F4") (class "Default")
      (node (ref "J2") (pin "4") (pinfunction "4_4") (pintype "bidirectional"))
      (node (ref "JP_FPGA4") (pin "1") (pinfunction "1_1") (pintype "passive"))
      (node (ref "R116") (pin "1") (pinfunction "1_1") (pintype "passive"))
      (node (ref "R117") (pin "2") (pinfunction "2_2") (pintype "passive"))
      (node (ref "R118") (pin "1") (pinfunction "1_1") (pintype "passive"))
    )
    (net (code "9") (name "F5") (class "Default")
      (node (ref "J2") (pin "5") (pinfunction "5_5") (pintype "bidirectional"))
      (node (ref "JP_FPGA5") (pin "1") (pinfunction "1_1") (pintype "passive"))
      (node (ref "R107") (pin "1") (pinfunction "1_1") (pintype "passive"))
      (node (ref "R108") (pin "2") (pinfunction "2_2") (pintype "passive"))
      (node (ref "R109") (pin "1") (pinfunction "1_1") (pintype "passive"))
    )
    (net (code "10") (name "F6") (class "Default")
      (node (ref "J2") (pin "6") (pinfunction "6_6") (pintype "bidirectional"))
      (node (ref "JP_FPGA6") (pin "1") (pinfunction "1_1") (pintype "passive"))
      (node (ref "R100") (pin "1") (pinfunction "1_1") (pintype "passive"))
      (node (ref "R98") (pin "1") (pinfunction "1_1") (pintype "passive"))
      (node (ref "R99") (pin "2") (pinfunction "2_2") (pintype "passive"))
    )
    (net (code "11") (name "F7") (class "Default")
      (node (ref "J2") (pin "7") (pinfunction "7_7") (pintype "bidirectional"))
      (node (ref "JP_FPGA7") (pin "1") (pinfunction "1_1") (pintype "passive"))
      (node (ref "R89") (pin "1") (pinfunction "1_1") (pintype "passive"))
      (node (ref "R90") (pin "2") (pinfunction "2_2") (pintype "passive"))
      (node (ref "R91") (pin "1") (pinfunction "1_1") (pintype "passive"))
    )
    (net (code "12") (name "F8") (class "Default")
      (node (ref "J2") (pin "8") (pinfunction "8_8") (pintype "bidirectional"))
      (node (ref "JP_FPGA8") (pin "1") (pinfunction "1_1") (pintype "passive"))
      (node (ref "R80") (pin "1") (pinfunction "1_1") (pintype "passive"))
      (node (ref "R81") (pin "2") (pinfunction "2_2") (pintype "passive"))
      (node (ref "R82") (pin "1") (pinfunction "1_1") (pintype "passive"))
    )
    (net (code "13") (name "F9") (class "Default")
      (node (ref "J2") (pin "9") (pinfunction "9_9") (pintype "bidirectional"))
      (node (ref "JP_FPGA9") (pin "1") (pinfunction "1_1") (pintype "passive"))
      (node (ref "R71") (pin "1") (pinfunction "1_1") (pintype "passive"))
      (node (ref "R72") (pin "2") (pinfunction "2_2") (pintype "passive"))
      (node (ref "R73") (pin "1") (pinfunction "1_1") (pintype "passive"))
    )
    (net (code "14") (name "F10") (class "Default")
      (node (ref "J2") (pin "10") (pinfunction "10_10") (pintype "bidirectional"))
      (node (ref "JP_FPGA10") (pin "1") (pinfunction "1_1") (pintype "passive"))
      (node (ref "R62") (pin "1") (pinfunction "1_1") (pintype "passive"))
      (node (ref "R63") (pin "2") (pinfunction "2_2") (pintype "passive"))
      (node (ref "R64") (pin "1") (pinfunction "1_1") (pintype "passive"))
    )
    (net (code "15") (name "F11") (class "Default")
      (node (ref "J2") (pin "11") (pinfunction "11_11") (pintype "bidirectional"))
      (node (ref "JP_FPGA11") (pin "1") (pinfunction "1_1") (pintype "passive"))
      (node (ref "R53") (pin "1") (pinfunction "1_1") (pintype "passive"))
      (node (ref "R54") (pin "2") (pinfunction "2_2") (pintype "passive"))
      (node (ref "R55") (pin "1") (pinfunction "1_1") (pintype "passive"))
    )
    (net (code "16") (name "F12") (class "Default")
      (node (ref "J2") (pin "12") (pinfunction "12_12") (pintype "bidirectional"))
      (node (ref "JP_FPGA12") (pin "1") (pinfunction "1_1") (pintype "passive"))
      (node (ref "R44") (pin "1") (pinfunction "1_1") (pintype "passive"))
      (node (ref "R45") (pin "2") (pinfunction "2_2") (pintype "passive"))
      (node (ref "R46") (pin "1") (pinfunction "1_1") (pintype "passive"))
    )
    (net (code "17") (name "F13") (class "Default")
      (node (ref "J2") (pin "13") (pinfunction "13_13") (pintype "bidirectional"))
      (node (ref "JP_FPGA13") (pin "1") (pinfunction "1_1") (pintype "passive"))
      (node (ref "R35") (pin "1") (pinfunction "1_1") (pintype "passive"))
      (node (ref "R36") (pin "2") (pinfunction "2_2") (pintype "passive"))
      (node (ref "R37") (pin "1") (pinfunction "1_1") (pintype "passive"))
    )
    (net (code "18") (name "F14") (class "Default")
      (node (ref "J2") (pin "14") (pinfunction "14_14") (pintype "bidirectional"))
      (node (ref "JP_FPGA14") (pin "1") (pinfunction "1_1") (pintype "passive"))
      (node (ref "R26") (pin "1") (pinfunction "1_1") (pintype "passive"))
      (node (ref "R27") (pin "2") (pinfunction "2_2") (pintype "passive"))
      (node (ref "R28") (pin "1") (pinfunction "1_1") (pintype "passive"))
    )
    (net (code "19") (name "F15") (class "Default")
      (node (ref "J2") (pin "15") (pinfunction "15_15") (pintype "bidirectional"))
      (node (ref "JP_FPGAP15") (pin "1") (pinfunction "1_1") (pintype "passive"))
      (node (ref "R17") (pin "1") (pinfunction "1_1") (pintype "passive"))
      (node (ref "R18") (pin "2") (pinfunction "2_2") (pintype "passive"))
      (node (ref "R19") (pin "1") (pinfunction "1_1") (pintype "passive"))
    )
    (net (code "20") (name "F16") (class "Default")
      (node (ref "J2") (pin "16") (pinfunction "16_16") (pintype "bidirectional"))
      (node (ref "JP_FPGA16") (pin "1") (pinfunction "1_1") (pintype "passive"))
      (node (ref "R4") (pin "1") (pinfunction "1_1") (pintype "passive"))
      (node (ref "R5") (pin "2") (pinfunction "2_2") (pintype "passive"))
      (node (ref "R6") (pin "1") (pinfunction "1_1") (pintype "passive"))
    )
    (net (code "21") (name "F17") (class "Default")
      (node (ref "F17_TP1") (pin "1") (pinfunction "1_1") (pintype "passive"))
      (node (ref "J2") (pin "17") (pinfunction "17_17") (pintype "bidirectional"))
      (node (ref "R161") (pin "2") (pinfunction "2_2") (pintype "passive"))
      (node (ref "R166") (pin "2") (pinfunction "2_2") (pintype "passive"))
    )
    (net (code "22") (name "GND") (class "Default")
      (node (ref "C1") (pin "2") (pinfunction "2_2") (pintype "passive"))
      (node (ref "C10") (pin "2") (pinfunction "2_2") (pintype "passive"))
      (node (ref "C11") (pin "-") (pinfunction "-_-") (pintype "passive"))
      (node (ref "C12") (pin "-") (pinfunction "-_-") (pintype "passive"))
      (node (ref "C14") (pin "2") (pinfunction "2_2") (pintype "passive"))
      (node (ref "C16") (pin "+") (pinfunction "+_+") (pintype "passive"))
      (node (ref "C17") (pin "+") (pinfunction "+_+") (pintype "passive"))
      (node (ref "C18") (pin "-") (pinfunction "-_-") (pintype "passive"))
      (node (ref "C19") (pin "2") (pinfunction "2_2") (pintype "passive"))
      (node (ref "C2") (pin "2") (pinfunction "2_2") (pintype "passive"))
      (node (ref "C21") (pin "2") (pinfunction "2_2") (pintype "passive"))
      (node (ref "C23") (pin "2") (pinfunction "2_2") (pintype "passive"))
      (node (ref "C25") (pin "2") (pinfunction "2_2") (pintype "passive"))
      (node (ref "C27") (pin "2") (pinfunction "2_2") (pintype "passive"))
      (node (ref "C29") (pin "2") (pinfunction "2_2") (pintype "passive"))
      (node (ref "C3") (pin "2") (pinfunction "2_2") (pintype "passive"))
      (node (ref "C31") (pin "2") (pinfunction "2_2") (pintype "passive"))
      (node (ref "C33") (pin "2") (pinfunction "2_2") (pintype "passive"))
      (node (ref "C35") (pin "2") (pinfunction "2_2") (pintype "passive"))
      (node (ref "C37") (pin "2") (pinfunction "2_2") (pintype "passive"))
      (node (ref "C39") (pin "2") (pinfunction "2_2") (pintype "passive"))
      (node (ref "C4") (pin "-") (pinfunction "-_-") (pintype "passive"))
      (node (ref "C41") (pin "2") (pinfunction "2_2") (pintype "passive"))
      (node (ref "C43") (pin "2") (pinfunction "2_2") (pintype "passive"))
      (node (ref "C45") (pin "2") (pinfunction "2_2") (pintype "passive"))
      (node (ref "C47") (pin "2") (pinfunction "2_2") (pintype "passive"))
      (node (ref "C49") (pin "2") (pinfunction "2_2") (pintype "passive"))
      (node (ref "C5") (pin "-") (pinfunction "-_-") (pintype "passive"))
      (node (ref "C51") (pin "2") (pinfunction "2_2") (pintype "passive"))
      (node (ref "C53") (pin "2") (pinfunction "2_2") (pintype "passive"))
      (node (ref "C55") (pin "2") (pinfunction "2_2") (pintype "passive"))
      (node (ref "C57") (pin "2") (pinfunction "2_2") (pintype "passive"))
      (node (ref "C59") (pin "2") (pinfunction "2_2") (pintype "passive"))
      (node (ref "C61") (pin "2") (pinfunction "2_2") (pintype "passive"))
      (node (ref "C63") (pin "2") (pinfunction "2_2") (pintype "passive"))
      (node (ref "C65") (pin "2") (pinfunction "2_2") (pintype "passive"))
      (node (ref "C67") (pin "2") (pinfunction "2_2") (pintype "passive"))
      (node (ref "C69") (pin "2") (pinfunction "2_2") (pintype "passive"))
      (node (ref "C7") (pin "2") (pinfunction "2_2") (pintype "passive"))
      (node (ref "C71") (pin "2") (pinfunction "2_2") (pintype "passive"))
      (node (ref "C73") (pin "2") (pinfunction "2_2") (pintype "passive"))
      (node (ref "C75") (pin "2") (pinfunction "2_2") (pintype "passive"))
      (node (ref "C82") (pin "1") (pinfunction "1_1") (pintype "passive"))
      (node (ref "C83") (pin "1") (pinfunction "1_1") (pintype "passive"))
      (node (ref "C84") (pin "2") (pinfunction "2_2") (pintype "passive"))
      (node (ref "C85") (pin "2") (pinfunction "2_2") (pintype "passive"))
      (node (ref "C86") (pin "1") (pinfunction "1_1") (pintype "passive"))
      (node (ref "C87") (pin "1") (pinfunction "1_1") (pintype "passive"))
      (node (ref "C9") (pin "2") (pinfunction "2_2") (pintype "passive"))
      (node (ref "J1") (pin "25") (pinfunction "25_25") (pintype "bidirectional"))
      (node (ref "J1") (pin "26") (pinfunction "26_26") (pintype "bidirectional"))
      (node (ref "J1") (pin "27") (pinfunction "27_27") (pintype "bidirectional"))
      (node (ref "J1") (pin "28") (pinfunction "28_28") (pintype "bidirectional"))
      (node (ref "J2") (pin "25") (pinfunction "25_25") (pintype "bidirectional"))
      (node (ref "J2") (pin "26") (pinfunction "26_26") (pintype "bidirectional"))
      (node (ref "J2") (pin "27") (pinfunction "27_27") (pintype "bidirectional"))
      (node (ref "J2") (pin "28") (pinfunction "28_28") (pintype "bidirectional"))
      (node (ref "J5") (pin "1") (pinfunction "1_1") (pintype "bidirectional"))
      (node (ref "J6") (pin "3") (pinfunction "3_3") (pintype "bidirectional"))
      (node (ref "R10") (pin "1") (pinfunction "1_1") (pintype "passive"))
      (node (ref "R100") (pin "2") (pinfunction "2_2") (pintype "passive"))
      (node (ref "R104") (pin "2") (pinfunction "2_2") (pintype "passive"))
      (node (ref "R109") (pin "2") (pinfunction "2_2") (pintype "passive"))
      (node (ref "R113") (pin "2") (pinfunction "2_2") (pintype "passive"))
      (node (ref "R118") (pin "2") (pinfunction "2_2") (pintype "passive"))
      (node (ref "R12") (pin "1") (pinfunction "1_1") (pintype "passive"))
      (node (ref "R122") (pin "2") (pinfunction "2_2") (pintype "passive"))
      (node (ref "R127") (pin "2") (pinfunction "2_2") (pintype "passive"))
      (node (ref "R131") (pin "2") (pinfunction "2_2") (pintype "passive"))
      (node (ref "R136") (pin "2") (pinfunction "2_2") (pintype "passive"))
      (node (ref "R14") (pin "2") (pinfunction "2_2") (pintype "passive"))
      (node (ref "R140") (pin "2") (pinfunction "2_2") (pintype "passive"))
      (node (ref "R145") (pin "2") (pinfunction "2_2") (pintype "passive"))
      (node (ref "R149") (pin "2") (pinfunction "2_2") (pintype "passive"))
      (node (ref "R161") (pin "1") (pinfunction "1_1") (pintype "passive"))
      (node (ref "R162") (pin "2") (pinfunction "2_2") (pintype "passive"))
      (node (ref "R19") (pin "2") (pinfunction "2_2") (pintype "passive"))
      (node (ref "R2") (pin "1") (pinfunction "1_1") (pintype "passive"))
      (node (ref "R23") (pin "2") (pinfunction "2_2") (pintype "passive"))
      (node (ref "R28") (pin "2") (pinfunction "2_2") (pintype "passive"))
      (node (ref "R32") (pin "2") (pinfunction "2_2") (pintype "passive"))
      (node (ref "R37") (pin "2") (pinfunction "2_2") (pintype "passive"))
      (node (ref "R41") (pin "2") (pinfunction "2_2") (pintype "passive"))
      (node (ref "R46") (pin "2") (pinfunction "2_2") (pintype "passive"))
      (node (ref "R50") (pin "2") (pinfunction "2_2") (pintype "passive"))
      (node (ref "R55") (pin "2") (pinfunction "2_2") (pintype "passive"))
      (node (ref "R59") (pin "2") (pinfunction "2_2") (pintype "passive"))
      (node (ref "R6") (pin "2") (pinfunction "2_2") (pintype "passive"))
      (node (ref "R64") (pin "2") (pinfunction "2_2") (pintype "passive"))
      (node (ref "R68") (pin "2") (pinfunction "2_2") (pintype "passive"))
      (node (ref "R73") (pin "2") (pinfunction "2_2") (pintype "passive"))
      (node (ref "R77") (pin "2") (pinfunction "2_2") (pintype "passive"))
      (node (ref "R82") (pin "2") (pinfunction "2_2") (pintype "passive"))
      (node (ref "R86") (pin "2") (pinfunction "2_2") (pintype "passive"))
      (node (ref "R91") (pin "2") (pinfunction "2_2") (pintype "passive"))
      (node (ref "R95") (pin "2") (pinfunction "2_2") (pintype "passive"))
      (node (ref "S10") (pin "3") (pinfunction "CW_3") (pintype "bidirectional"))
      (node (ref "S12") (pin "3") (pinfunction "CW_3") (pintype "bidirectional"))
      (node (ref "S14") (pin "3") (pinfunction "CW_3") (pintype "bidirectional"))
      (node (ref "S16") (pin "3") (pinfunction "CW_3") (pintype "bidirectional"))
      (node (ref "S18") (pin "3") (pinfunction "CW_3") (pintype "bidirectional"))
      (node (ref "S2") (pin "3") (pinfunction "CW_3") (pintype "bidirectional"))
      (node (ref "S20") (pin "3") (pinfunction "CW_3") (pintype "bidirectional"))
      (node (ref "S22") (pin "3") (pinfunction "CW_3") (pintype "bidirectional"))
      (node (ref "S24") (pin "3") (pinfunction "CW_3") (pintype "bidirectional"))
      (node (ref "S26") (pin "3") (pinfunction "CW_3") (pintype "bidirectional"))
      (node (ref "S28") (pin "3") (pinfunction "CW_3") (pintype "bidirectional"))
      (node (ref "S30") (pin "3") (pinfunction "CW_3") (pintype "bidirectional"))
      (node (ref "S32") (pin "3") (pinfunction "CW_3") (pintype "bidirectional"))
      (node (ref "S4") (pin "3") (pinfunction "CW_3") (pintype "bidirectional"))
      (node (ref "S6") (pin "3") (pinfunction "CW_3") (pintype "bidirectional"))
      (node (ref "S8") (pin "3") (pinfunction "CW_3") (pintype "bidirectional"))
      (node (ref "U10") (pin "4") (pinfunction "V-_4") (pintype "power_in"))
      (node (ref "U12") (pin "4") (pinfunction "V-_4") (pintype "power_in"))
      (node (ref "U14") (pin "4") (pinfunction "V-_4") (pintype "power_in"))
      (node (ref "U16") (pin "4") (pinfunction "V-_4") (pintype "power_in"))
      (node (ref "U18") (pin "4") (pinfunction "V-_4") (pintype "power_in"))
      (node (ref "U20") (pin "4") (pinfunction "V-_4") (pintype "power_in"))
      (node (ref "U22") (pin "4") (pinfunction "V-_4") (pintype "power_in"))
      (node (ref "U24") (pin "4") (pinfunction "V-_4") (pintype "power_in"))
      (node (ref "U26") (pin "4") (pinfunction "V-_4") (pintype "power_in"))
      (node (ref "U28") (pin "4") (pinfunction "V-_4") (pintype "power_in"))
      (node (ref "U30") (pin "4") (pinfunction "V-_4") (pintype "power_in"))
      (node (ref "U32") (pin "4") (pinfunction "V-_4") (pintype "power_in"))
      (node (ref "U34") (pin "4") (pinfunction "V-_4") (pintype "power_in"))
      (node (ref "U39") (pin "4") (pinfunction "V-_4") (pintype "power_in"))
      (node (ref "U39") (pin "8") (pinfunction "SHDN_8") (pintype "passive"))
      (node (ref "U4") (pin "4") (pinfunction "V-_4") (pintype "power_in"))
      (node (ref "U6") (pin "4") (pinfunction "V-_4") (pintype "power_in"))
      (node (ref "U8") (pin "4") (pinfunction "V-_4") (pintype "power_in"))
      (node (ref "X2") (pin "2") (pinfunction "S_2") (pintype "passive"))
      (node (ref "X2") (pin "3") (pinfunction "S_3") (pintype "passive"))
    )
    (net (code "23") (name "INV_DIR_DRAIN") (class "Default")
      (node (ref "DRAIN_TP1") (pin "1") (pinfunction "1_1") (pintype "passive"))
      (node (ref "JP_DRAIN") (pin "1") (pinfunction "1_1") (pintype "passive"))
      (node (ref "JP_DRAIN1") (pin "1") (pinfunction "1_1") (pintype "passive"))
      (node (ref "JP_DRAIN10") (pin "1") (pinfunction "1_1") (pintype "passive"))
      (node (ref "JP_DRAIN11") (pin "1") (pinfunction "1_1") (pintype "passive"))
      (node (ref "JP_DRAIN12") (pin "1") (pinfunction "1_1") (pintype "passive"))
      (node (ref "JP_DRAIN13") (pin "1") (pinfunction "1_1") (pintype "passive"))
      (node (ref "JP_DRAIN14") (pin "1") (pinfunction "1_1") (pintype "passive"))
      (node (ref "JP_DRAIN15") (pin "1") (pinfunction "1_1") (pintype "passive"))
      (node (ref "JP_DRAIN2") (pin "1") (pinfunction "1_1") (pintype "passive"))
      (node (ref "JP_DRAIN3") (pin "1") (pinfunction "1_1") (pintype "passive"))
      (node (ref "JP_DRAIN4") (pin "1") (pinfunction "1_1") (pintype "passive"))
      (node (ref "JP_DRAIN5") (pin "1") (pinfunction "1_1") (pintype "passive"))
      (node (ref "JP_DRAIN6") (pin "1") (pinfunction "1_1") (pintype "passive"))
      (node (ref "JP_DRAIN7") (pin "1") (pinfunction "1_1") (pintype "passive"))
      (node (ref "JP_DRAIN8") (pin "1") (pinfunction "1_1") (pintype "passive"))
      (node (ref "JP_DRAIN9") (pin "1") (pinfunction "1_1") (pintype "passive"))
      (node (ref "R162") (pin "1") (pinfunction "1_1") (pintype "passive"))
      (node (ref "U10") (pin "8") (pinfunction "SHDN_8") (pintype "passive"))
      (node (ref "U12") (pin "8") (pinfunction "SHDN_8") (pintype "passive"))
      (node (ref "U14") (pin "8") (pinfunction "SHDN_8") (pintype "passive"))
      (node (ref "U16") (pin "8") (pinfunction "SHDN_8") (pintype "passive"))
      (node (ref "U18") (pin "8") (pinfunction "SHDN_8") (pintype "passive"))
      (node (ref "U20") (pin "8") (pinfunction "SHDN_8") (pintype "passive"))
      (node (ref "U22") (pin "8") (pinfunction "SHDN_8") (pintype "passive"))
      (node (ref "U24") (pin "8") (pinfunction "SHDN_8") (pintype "passive"))
      (node (ref "U26") (pin "8") (pinfunction "SHDN_8") (pintype "passive"))
      (node (ref "U28") (pin "8") (pinfunction "SHDN_8") (pintype "passive"))
      (node (ref "U30") (pin "8") (pinfunction "SHDN_8") (pintype "passive"))
      (node (ref "U32") (pin "8") (pinfunction "SHDN_8") (pintype "passive"))
      (node (ref "U34") (pin "8") (pinfunction "SHDN_8") (pintype "passive"))
      (node (ref "U38") (pin "3") (pinfunction "DRAIN_3") (pintype "passive"))
      (node (ref "U4") (pin "8") (pinfunction "SHDN_8") (pintype "passive"))
      (node (ref "U6") (pin "8") (pinfunction "SHDN_8") (pintype "passive"))
      (node (ref "U8") (pin "8") (pinfunction "SHDN_8") (pintype "passive"))
    )
    (net (code "24") (name "M1") (class "Default")
      (node (ref "J1") (pin "1") (pinfunction "1_1") (pintype "bidirectional"))
      (node (ref "JP_MIPS1") (pin "1") (pinfunction "1_1") (pintype "passive"))
      (node (ref "R147") (pin "2") (pinfunction "2_2") (pintype "passive"))
      (node (ref "R148") (pin "1") (pinfunction "1_1") (pintype "passive"))
      (node (ref "R149") (pin "1") (pinfunction "1_1") (pintype "passive"))
    )
    (net (code "25") (name "M2") (class "Default")
      (node (ref "J1") (pin "2") (pinfunction "2_2") (pintype "bidirectional"))
      (node (ref "JP_MIPS2") (pin "1") (pinfunction "1_1") (pintype "passive"))
      (node (ref "R138") (pin "2") (pinfunction "2_2") (pintype "passive"))
      (node (ref "R139") (pin "1") (pinfunction "1_1") (pintype "passive"))
      (node (ref "R140") (pin "1") (pinfunction "1_1") (pintype "passive"))
    )
    (net (code "26") (name "M3") (class "Default")
      (node (ref "J1") (pin "3") (pinfunction "3_3") (pintype "bidirectional"))
      (node (ref "JP_MIPS3") (pin "1") (pinfunction "1_1") (pintype "passive"))
      (node (ref "R129") (pin "2") (pinfunction "2_2") (pintype "passive"))
      (node (ref "R130") (pin "1") (pinfunction "1_1") (pintype "passive"))
      (node (ref "R131") (pin "1") (pinfunction "1_1") (pintype "passive"))
    )
    (net (code "27") (name "M4") (class "Default")
      (node (ref "J1") (pin "4") (pinfunction "4_4") (pintype "bidirectional"))
      (node (ref "JP_MIPS4") (pin "1") (pinfunction "1_1") (pintype "passive"))
      (node (ref "R120") (pin "2") (pinfunction "2_2") (pintype "passive"))
      (node (ref "R121") (pin "1") (pinfunction "1_1") (pintype "passive"))
      (node (ref "R122") (pin "1") (pinfunction "1_1") (pintype "passive"))
    )
    (net (code "28") (name "M5") (class "Default")
      (node (ref "J1") (pin "5") (pinfunction "5_5") (pintype "bidirectional"))
      (node (ref "JP_MIPS5") (pin "1") (pinfunction "1_1") (pintype "passive"))
      (node (ref "R111") (pin "2") (pinfunction "2_2") (pintype "passive"))
      (node (ref "R112") (pin "1") (pinfunction "1_1") (pintype "passive"))
      (node (ref "R113") (pin "1") (pinfunction "1_1") (pintype "passive"))
    )
    (net (code "29") (name "M6") (class "Default")
      (node (ref "J1") (pin "6") (pinfunction "6_6") (pintype "bidirectional"))
      (node (ref "JP_MIPS6") (pin "1") (pinfunction "1_1") (pintype "passive"))
      (node (ref "R102") (pin "2") (pinfunction "2_2") (pintype "passive"))
      (node (ref "R103") (pin "1") (pinfunction "1_1") (pintype "passive"))
      (node (ref "R104") (pin "1") (pinfunction "1_1") (pintype "passive"))
    )
    (net (code "30") (name "M7") (class "Default")
      (node (ref "J1") (pin "7") (pinfunction "7_7") (pintype "bidirectional"))
      (node (ref "JP_MIPS7") (pin "1") (pinfunction "1_1") (pintype "passive"))
      (node (ref "R93") (pin "2") (pinfunction "2_2") (pintype "passive"))
      (node (ref "R94") (pin "1") (pinfunction "1_1") (pintype "passive"))
      (node (ref "R95") (pin "1") (pinfunction "1_1") (pintype "passive"))
    )
    (net (code "31") (name "M8") (class "Default")
      (node (ref "J1") (pin "8") (pinfunction "8_8") (pintype "bidirectional"))
      (node (ref "JP_MIPS8") (pin "1") (pinfunction "1_1") (pintype "passive"))
      (node (ref "R84") (pin "2") (pinfunction "2_2") (pintype "passive"))
      (node (ref "R85") (pin "1") (pinfunction "1_1") (pintype "passive"))
      (node (ref "R86") (pin "1") (pinfunction "1_1") (pintype "passive"))
    )
    (net (code "32") (name "M9") (class "Default")
      (node (ref "J1") (pin "9") (pinfunction "9_9") (pintype "bidirectional"))
      (node (ref "JP_MIPS9") (pin "1") (pinfunction "1_1") (pintype "passive"))
      (node (ref "R75") (pin "2") (pinfunction "2_2") (pintype "passive"))
      (node (ref "R76") (pin "1") (pinfunction "1_1") (pintype "passive"))
      (node (ref "R77") (pin "1") (pinfunction "1_1") (pintype "passive"))
    )
    (net (code "33") (name "M10") (class "Default")
      (node (ref "J1") (pin "10") (pinfunction "10_10") (pintype "bidirectional"))
      (node (ref "JP_MIPS10") (pin "1") (pinfunction "1_1") (pintype "passive"))
      (node (ref "R66") (pin "2") (pinfunction "2_2") (pintype "passive"))
      (node (ref "R67") (pin "1") (pinfunction "1_1") (pintype "passive"))
      (node (ref "R68") (pin "1") (pinfunction "1_1") (pintype "passive"))
    )
    (net (code "34") (name "M11") (class "Default")
      (node (ref "J1") (pin "11") (pinfunction "11_11") (pintype "bidirectional"))
      (node (ref "JP_MIPS11") (pin "1") (pinfunction "1_1") (pintype "passive"))
      (node (ref "R57") (pin "2") (pinfunction "2_2") (pintype "passive"))
      (node (ref "R58") (pin "1") (pinfunction "1_1") (pintype "passive"))
      (node (ref "R59") (pin "1") (pinfunction "1_1") (pintype "passive"))
    )
    (net (code "35") (name "M12") (class "Default")
      (node (ref "J1") (pin "12") (pinfunction "12_12") (pintype "bidirectional"))
      (node (ref "JP_MIPS12") (pin "1") (pinfunction "1_1") (pintype "passive"))
      (node (ref "R48") (pin "2") (pinfunction "2_2") (pintype "passive"))
      (node (ref "R49") (pin "1") (pinfunction "1_1") (pintype "passive"))
      (node (ref "R50") (pin "1") (pinfunction "1_1") (pintype "passive"))
    )
    (net (code "36") (name "M13") (class "Default")
      (node (ref "J1") (pin "13") (pinfunction "13_13") (pintype "bidirectional"))
      (node (ref "JP_MIPS13") (pin "1") (pinfunction "1_1") (pintype "passive"))
      (node (ref "R39") (pin "2") (pinfunction "2_2") (pintype "passive"))
      (node (ref "R40") (pin "1") (pinfunction "1_1") (pintype "passive"))
      (node (ref "R41") (pin "1") (pinfunction "1_1") (pintype "passive"))
    )
    (net (code "37") (name "M14") (class "Default")
      (node (ref "J1") (pin "14") (pinfunction "14_14") (pintype "bidirectional"))
      (node (ref "JP_MIPS14") (pin "1") (pinfunction "1_1") (pintype "passive"))
      (node (ref "R30") (pin "2") (pinfunction "2_2") (pintype "passive"))
      (node (ref "R31") (pin "1") (pinfunction "1_1") (pintype "passive"))
      (node (ref "R32") (pin "1") (pinfunction "1_1") (pintype "passive"))
    )
    (net (code "38") (name "M15") (class "Default")
      (node (ref "J1") (pin "15") (pinfunction "15_15") (pintype "bidirectional"))
      (node (ref "JP_MIPS15") (pin "1") (pinfunction "1_1") (pintype "passive"))
      (node (ref "R21") (pin "2") (pinfunction "2_2") (pintype "passive"))
      (node (ref "R22") (pin "1") (pinfunction "1_1") (pintype "passive"))
      (node (ref "R23") (pin "1") (pinfunction "1_1") (pintype "passive"))
    )
    (net (code "39") (name "M16") (class "Default")
      (node (ref "J1") (pin "16") (pinfunction "16_16") (pintype "bidirectional"))
      (node (ref "JP_MIPS16") (pin "1") (pinfunction "1_1") (pintype "passive"))
      (node (ref "R13") (pin "1") (pinfunction "1_1") (pintype "passive"))
      (node (ref "R14") (pin "1") (pinfunction "1_1") (pintype "passive"))
      (node (ref "R8") (pin "2") (pinfunction "2_2") (pintype "passive"))
    )
    (net (code "40") (name "M17") (class "Default")
      (node (ref "J1") (pin "17") (pinfunction "17_17") (pintype "bidirectional"))
      (node (ref "J5") (pin "3") (pinfunction "3_3") (pintype "bidirectional"))
      (node (ref "J6") (pin "1") (pinfunction "1_1") (pintype "bidirectional"))
      (node (ref "M17_TP1") (pin "1") (pinfunction "1_1") (pintype "passive"))
    )
    (net (code "41") (name "Net-(IC3-ADJ{slash}GND)") (class "Default")
      (node (ref "C5") (pin "+") (pinfunction "+_+") (pintype "passive"))
      (node (ref "D4") (pin "A") (pinfunction "A_A") (pintype "passive"))
      (node (ref "IC3") (pin "1") (pinfunction "ADJ/GND_1") (pintype "power_in"))
      (node (ref "R10") (pin "2") (pinfunction "2_2") (pintype "passive"))
      (node (ref "R9") (pin "1") (pinfunction "1_1") (pintype "passive"))
    )
    (net (code "42") (name "Net-(IC3-INPUT)") (class "Default")
      (node (ref "+V_IN1") (pin "1") (pinfunction "1_1") (pintype "passive"))
      (node (ref "C10") (pin "1") (pinfunction "1_1") (pintype "passive"))
      (node (ref "C18") (pin "+") (pinfunction "+_+") (pintype "passive"))
      (node (ref "C3") (pin "1") (pinfunction "1_1") (pintype "passive"))
      (node (ref "D3") (pin "C") (pinfunction "C_C") (pintype "passive"))
      (node (ref "D7") (pin "C") (pinfunction "C_C") (pintype "passive"))
      (node (ref "IC3") (pin "3") (pinfunction "INPUT_3") (pintype "input"))
      (node (ref "IC4") (pin "3") (pinfunction "INPUT_3") (pintype "input"))
      (node (ref "U1") (pin "1") (pinfunction "OUT+_1") (pintype "output"))
    )
    (net (code "43") (name "Net-(IC4-ADJ{slash}GND)") (class "Default")
      (node (ref "C12") (pin "+") (pinfunction "+_+") (pintype "passive"))
      (node (ref "D8") (pin "A") (pinfunction "A_A") (pintype "passive"))
      (node (ref "IC4") (pin "1") (pinfunction "ADJ/GND_1") (pintype "power_in"))
      (node (ref "R11") (pin "1") (pinfunction "1_1") (pintype "passive"))
      (node (ref "R12") (pin "2") (pinfunction "2_2") (pintype "passive"))
    )
    (net (code "44") (name "Net-(J5-Pad2)") (class "Default")
      (node (ref "J5") (pin "2") (pinfunction "2_2") (pintype "bidirectional"))
      (node (ref "J5") (pin "4") (pinfunction "4_4") (pintype "bidirectional"))
      (node (ref "R159") (pin "1") (pinfunction "1_1") (pintype "passive"))
      (node (ref "R163") (pin "1") (pinfunction "1_1") (pintype "passive"))
    )
    (net (code "45") (name "Net-(J6-Pad2)") (class "Default")
      (node (ref "J6") (pin "2") (pinfunction "2_2") (pintype "bidirectional"))
      (node (ref "J6") (pin "4") (pinfunction "4_4") (pintype "bidirectional"))
      (node (ref "R160") (pin "1") (pinfunction "1_1") (pintype "passive"))
      (node (ref "R164") (pin "1") (pinfunction "1_1") (pintype "passive"))
    )
    (net (code "46") (name "Net-(S1-WIPER)") (class "Default")
      (node (ref "R3") (pin "2") (pinfunction "2_2") (pintype "passive"))
      (node (ref "S1") (pin "2") (pinfunction "WIPER_2") (pintype "bidirectional"))
    )
    (net (code "47") (name "Net-(S2-WIPER)") (class "Default")
      (node (ref "R7") (pin "1") (pinfunction "1_1") (pintype "passive"))
      (node (ref "S2") (pin "2") (pinfunction "WIPER_2") (pintype "bidirectional"))
    )
    (net (code "48") (name "Net-(S3-WIPER)") (class "Default")
      (node (ref "R16") (pin "2") (pinfunction "2_2") (pintype "passive"))
      (node (ref "S3") (pin "2") (pinfunction "WIPER_2") (pintype "bidirectional"))
    )
    (net (code "49") (name "Net-(S4-WIPER)") (class "Default")
      (node (ref "R20") (pin "1") (pinfunction "1_1") (pintype "passive"))
      (node (ref "S4") (pin "2") (pinfunction "WIPER_2") (pintype "bidirectional"))
    )
    (net (code "50") (name "Net-(S5-WIPER)") (class "Default")
      (node (ref "R25") (pin "2") (pinfunction "2_2") (pintype "passive"))
      (node (ref "S5") (pin "2") (pinfunction "WIPER_2") (pintype "bidirectional"))
    )
    (net (code "51") (name "Net-(S6-WIPER)") (class "Default")
      (node (ref "R29") (pin "1") (pinfunction "1_1") (pintype "passive"))
      (node (ref "S6") (pin "2") (pinfunction "WIPER_2") (pintype "bidirectional"))
    )
    (net (code "52") (name "Net-(S7-WIPER)") (class "Default")
      (node (ref "R34") (pin "2") (pinfunction "2_2") (pintype "passive"))
      (node (ref "S7") (pin "2") (pinfunction "WIPER_2") (pintype "bidirectional"))
    )
    (net (code "53") (name "Net-(S8-WIPER)") (class "Default")
      (node (ref "R38") (pin "1") (pinfunction "1_1") (pintype "passive"))
      (node (ref "S8") (pin "2") (pinfunction "WIPER_2") (pintype "bidirectional"))
    )
    (net (code "54") (name "Net-(S9-WIPER)") (class "Default")
      (node (ref "R43") (pin "2") (pinfunction "2_2") (pintype "passive"))
      (node (ref "S9") (pin "2") (pinfunction "WIPER_2") (pintype "bidirectional"))
    )
    (net (code "55") (name "Net-(S10-WIPER)") (class "Default")
      (node (ref "R47") (pin "1") (pinfunction "1_1") (pintype "passive"))
      (node (ref "S10") (pin "2") (pinfunction "WIPER_2") (pintype "bidirectional"))
    )
    (net (code "56") (name "Net-(S11-WIPER)") (class "Default")
      (node (ref "R52") (pin "2") (pinfunction "2_2") (pintype "passive"))
      (node (ref "S11") (pin "2") (pinfunction "WIPER_2") (pintype "bidirectional"))
    )
    (net (code "57") (name "Net-(S12-WIPER)") (class "Default")
      (node (ref "R56") (pin "1") (pinfunction "1_1") (pintype "passive"))
      (node (ref "S12") (pin "2") (pinfunction "WIPER_2") (pintype "bidirectional"))
    )
    (net (code "58") (name "Net-(S13-WIPER)") (class "Default")
      (node (ref "R61") (pin "2") (pinfunction "2_2") (pintype "passive"))
      (node (ref "S13") (pin "2") (pinfunction "WIPER_2") (pintype "bidirectional"))
    )
    (net (code "59") (name "Net-(S14-WIPER)") (class "Default")
      (node (ref "R65") (pin "1") (pinfunction "1_1") (pintype "passive"))
      (node (ref "S14") (pin "2") (pinfunction "WIPER_2") (pintype "bidirectional"))
    )
    (net (code "60") (name "Net-(S15-WIPER)") (class "Default")
      (node (ref "R70") (pin "2") (pinfunction "2_2") (pintype "passive"))
      (node (ref "S15") (pin "2") (pinfunction "WIPER_2") (pintype "bidirectional"))
    )
    (net (code "61") (name "Net-(S16-WIPER)") (class "Default")
      (node (ref "R74") (pin "1") (pinfunction "1_1") (pintype "passive"))
      (node (ref "S16") (pin "2") (pinfunction "WIPER_2") (pintype "bidirectional"))
    )
    (net (code "62") (name "Net-(S17-WIPER)") (class "Default")
      (node (ref "R79") (pin "2") (pinfunction "2_2") (pintype "passive"))
      (node (ref "S17") (pin "2") (pinfunction "WIPER_2") (pintype "bidirectional"))
    )
    (net (code "63") (name "Net-(S18-WIPER)") (class "Default")
      (node (ref "R83") (pin "1") (pinfunction "1_1") (pintype "passive"))
      (node (ref "S18") (pin "2") (pinfunction "WIPER_2") (pintype "bidirectional"))
    )
    (net (code "64") (name "Net-(S19-WIPER)") (class "Default")
      (node (ref "R88") (pin "2") (pinfunction "2_2") (pintype "passive"))
      (node (ref "S19") (pin "2") (pinfunction "WIPER_2") (pintype "bidirectional"))
    )
    (net (code "65") (name "Net-(S20-WIPER)") (class "Default")
      (node (ref "R92") (pin "1") (pinfunction "1_1") (pintype "passive"))
      (node (ref "S20") (pin "2") (pinfunction "WIPER_2") (pintype "bidirectional"))
    )
    (net (code "66") (name "Net-(S21-WIPER)") (class "Default")
      (node (ref "R97") (pin "2") (pinfunction "2_2") (pintype "passive"))
      (node (ref "S21") (pin "2") (pinfunction "WIPER_2") (pintype "bidirectional"))
    )
    (net (code "67") (name "Net-(S22-WIPER)") (class "Default")
      (node (ref "R101") (pin "1") (pinfunction "1_1") (pintype "passive"))
      (node (ref "S22") (pin "2") (pinfunction "WIPER_2") (pintype "bidirectional"))
    )
    (net (code "68") (name "Net-(S23-WIPER)") (class "Default")
      (node (ref "R106") (pin "2") (pinfunction "2_2") (pintype "passive"))
      (node (ref "S23") (pin "2") (pinfunction "WIPER_2") (pintype "bidirectional"))
    )
    (net (code "69") (name "Net-(S24-WIPER)") (class "Default")
      (node (ref "R110") (pin "1") (pinfunction "1_1") (pintype "passive"))
      (node (ref "S24") (pin "2") (pinfunction "WIPER_2") (pintype "bidirectional"))
    )
    (net (code "70") (name "Net-(S25-WIPER)") (class "Default")
      (node (ref "R115") (pin "2") (pinfunction "2_2") (pintype "passive"))
      (node (ref "S25") (pin "2") (pinfunction "WIPER_2") (pintype "bidirectional"))
    )
    (net (code "71") (name "Net-(S26-WIPER)") (class "Default")
      (node (ref "R119") (pin "1") (pinfunction "1_1") (pintype "passive"))
      (node (ref "S26") (pin "2") (pinfunction "WIPER_2") (pintype "bidirectional"))
    )
    (net (code "72") (name "Net-(S27-WIPER)") (class "Default")
      (node (ref "R124") (pin "2") (pinfunction "2_2") (pintype "passive"))
      (node (ref "S27") (pin "2") (pinfunction "WIPER_2") (pintype "bidirectional"))
    )
    (net (code "73") (name "Net-(S28-WIPER)") (class "Default")
      (node (ref "R128") (pin "1") (pinfunction "1_1") (pintype "passive"))
      (node (ref "S28") (pin "2") (pinfunction "WIPER_2") (pintype "bidirectional"))
    )
    (net (code "74") (name "Net-(S29-WIPER)") (class "Default")
      (node (ref "R133") (pin "2") (pinfunction "2_2") (pintype "passive"))
      (node (ref "S29") (pin "2") (pinfunction "WIPER_2") (pintype "bidirectional"))
    )
    (net (code "75") (name "Net-(S30-WIPER)") (class "Default")
      (node (ref "R137") (pin "1") (pinfunction "1_1") (pintype "passive"))
      (node (ref "S30") (pin "2") (pinfunction "WIPER_2") (pintype "bidirectional"))
    )
    (net (code "76") (name "Net-(S31-WIPER)") (class "Default")
      (node (ref "R142") (pin "2") (pinfunction "2_2") (pintype "passive"))
      (node (ref "S31") (pin "2") (pinfunction "WIPER_2") (pintype "bidirectional"))
    )
    (net (code "77") (name "Net-(S32-WIPER)") (class "Default")
      (node (ref "R146") (pin "1") (pinfunction "1_1") (pintype "passive"))
      (node (ref "S32") (pin "2") (pinfunction "WIPER_2") (pintype "bidirectional"))
    )
    (net (code "78") (name "Net-(U1-AC)") (class "Default")
      (node (ref "POW3") (pin "1") (pinfunction "1_1") (pintype "passive"))
      (node (ref "U1") (pin "3") (pinfunction "AC_3") (pintype "input"))
      (node (ref "X2") (pin "1") (pinfunction "S_1") (pintype "passive"))
    )
    (net (code "79") (name "Net-(U1-AC_2)") (class "Default")
      (node (ref "POW4") (pin "1") (pinfunction "1_1") (pintype "passive"))
      (node (ref "U1") (pin "4") (pinfunction "AC_2_4") (pintype "input"))
      (node (ref "X2") (pin "4") (pinfunction "S_4") (pintype "passive"))
    )
    (net (code "80") (name "Net-(U1-OUT-)") (class "Default")
      (node (ref "-V_IN1") (pin "1") (pinfunction "1_1") (pintype "passive"))
      (node (ref "C1") (pin "1") (pinfunction "1_1") (pintype "passive"))
      (node (ref "C17") (pin "-") (pinfunction "-_-") (pintype "passive"))
      (node (ref "U1") (pin "2") (pinfunction "OUT-_2") (pintype "output"))
      (node (ref "U2") (pin "4") (pinfunction "VIN_4") (pintype "power_in"))
    )
    (net (code "81") (name "Net-(U2-GND)") (class "Default")
      (node (ref "C16") (pin "-") (pinfunction "-_-") (pintype "passive"))
      (node (ref "R151") (pin "1") (pinfunction "1_1") (pintype "passive"))
      (node (ref "R2") (pin "2") (pinfunction "2_2") (pintype "passive"))
      (node (ref "U2") (pin "1") (pinfunction "GND_1") (pintype "power_in"))
    )
    (net (code "82") (name "Net-(U3-IN+)") (class "Default")
      (node (ref "R4") (pin "2") (pinfunction "2_2") (pintype "passive"))
      (node (ref "U3") (pin "3") (pinfunction "IN+_3") (pintype "input"))
    )
    (net (code "83") (name "Net-(U3-IN-)") (class "Default")
      (node (ref "R3") (pin "1") (pinfunction "1_1") (pintype "passive"))
      (node (ref "U3") (pin "2") (pinfunction "IN-_2") (pintype "input"))
    )
    (net (code "84") (name "Net-(U3-OUT)") (class "Default")
      (node (ref "R8") (pin "1") (pinfunction "1_1") (pintype "passive"))
      (node (ref "U3") (pin "6") (pinfunction "OUT_6") (pintype "output"))
    )
    (net (code "85") (name "Net-(U3-SHDN)") (class "Default")
      (node (ref "R15") (pin "1") (pinfunction "1_1") (pintype "passive"))
      (node (ref "U3") (pin "8") (pinfunction "SHDN_8") (pintype "passive"))
    )
    (net (code "86") (name "Net-(U4-IN+)") (class "Default")
      (node (ref "R13") (pin "2") (pinfunction "2_2") (pintype "passive"))
      (node (ref "U4") (pin "3") (pinfunction "IN+_3") (pintype "input"))
    )
    (net (code "87") (name "Net-(U4-IN-)") (class "Default")
      (node (ref "R7") (pin "2") (pinfunction "2_2") (pintype "passive"))
      (node (ref "U4") (pin "2") (pinfunction "IN-_2") (pintype "input"))
    )
    (net (code "88") (name "Net-(U4-OUT)") (class "Default")
      (node (ref "R5") (pin "1") (pinfunction "1_1") (pintype "passive"))
      (node (ref "U4") (pin "6") (pinfunction "OUT_6") (pintype "output"))
    )
    (net (code "89") (name "Net-(U5-IN+)") (class "Default")
      (node (ref "R17") (pin "2") (pinfunction "2_2") (pintype "passive"))
      (node (ref "U5") (pin "3") (pinfunction "IN+_3") (pintype "input"))
    )
    (net (code "90") (name "Net-(U5-IN-)") (class "Default")
      (node (ref "R16") (pin "1") (pinfunction "1_1") (pintype "passive"))
      (node (ref "U5") (pin "2") (pinfunction "IN-_2") (pintype "input"))
    )
    (net (code "91") (name "Net-(U5-OUT)") (class "Default")
      (node (ref "R21") (pin "1") (pinfunction "1_1") (pintype "passive"))
      (node (ref "U5") (pin "6") (pinfunction "OUT_6") (pintype "output"))
    )
    (net (code "92") (name "Net-(U5-SHDN)") (class "Default")
      (node (ref "R24") (pin "1") (pinfunction "1_1") (pintype "passive"))
      (node (ref "U5") (pin "8") (pinfunction "SHDN_8") (pintype "passive"))
    )
    (net (code "93") (name "Net-(U6-IN+)") (class "Default")
      (node (ref "R22") (pin "2") (pinfunction "2_2") (pintype "passive"))
      (node (ref "U6") (pin "3") (pinfunction "IN+_3") (pintype "input"))
    )
    (net (code "94") (name "Net-(U6-IN-)") (class "Default")
      (node (ref "R20") (pin "2") (pinfunction "2_2") (pintype "passive"))
      (node (ref "U6") (pin "2") (pinfunction "IN-_2") (pintype "input"))
    )
    (net (code "95") (name "Net-(U6-OUT)") (class "Default")
      (node (ref "R18") (pin "1") (pinfunction "1_1") (pintype "passive"))
      (node (ref "U6") (pin "6") (pinfunction "OUT_6") (pintype "output"))
    )
    (net (code "96") (name "Net-(U7-IN+)") (class "Default")
      (node (ref "R26") (pin "2") (pinfunction "2_2") (pintype "passive"))
      (node (ref "U7") (pin "3") (pinfunction "IN+_3") (pintype "input"))
    )
    (net (code "97") (name "Net-(U7-IN-)") (class "Default")
      (node (ref "R25") (pin "1") (pinfunction "1_1") (pintype "passive"))
      (node (ref "U7") (pin "2") (pinfunction "IN-_2") (pintype "input"))
    )
    (net (code "98") (name "Net-(U7-OUT)") (class "Default")
      (node (ref "R30") (pin "1") (pinfunction "1_1") (pintype "passive"))
      (node (ref "U7") (pin "6") (pinfunction "OUT_6") (pintype "output"))
    )
    (net (code "99") (name "Net-(U7-SHDN)") (class "Default")
      (node (ref "R33") (pin "1") (pinfunction "1_1") (pintype "passive"))
      (node (ref "U7") (pin "8") (pinfunction "SHDN_8") (pintype "passive"))
    )
    (net (code "100") (name "Net-(U8-IN+)") (class "Default")
      (node (ref "R31") (pin "2") (pinfunction "2_2") (pintype "passive"))
      (node (ref "U8") (pin "3") (pinfunction "IN+_3") (pintype "input"))
    )
    (net (code "101") (name "Net-(U8-IN-)") (class "Default")
      (node (ref "R29") (pin "2") (pinfunction "2_2") (pintype "passive"))
      (node (ref "U8") (pin "2") (pinfunction "IN-_2") (pintype "input"))
    )
    (net (code "102") (name "Net-(U8-OUT)") (class "Default")
      (node (ref "R27") (pin "1") (pinfunction "1_1") (pintype "passive"))
      (node (ref "U8") (pin "6") (pinfunction "OUT_6") (pintype "output"))
    )
    (net (code "103") (name "Net-(U9-IN+)") (class "Default")
      (node (ref "R35") (pin "2") (pinfunction "2_2") (pintype "passive"))
      (node (ref "U9") (pin "3") (pinfunction "IN+_3") (pintype "input"))
    )
    (net (code "104") (name "Net-(U9-IN-)") (class "Default")
      (node (ref "R34") (pin "1") (pinfunction "1_1") (pintype "passive"))
      (node (ref "U9") (pin "2") (pinfunction "IN-_2") (pintype "input"))
    )
    (net (code "105") (name "Net-(U9-OUT)") (class "Default")
      (node (ref "R39") (pin "1") (pinfunction "1_1") (pintype "passive"))
      (node (ref "U9") (pin "6") (pinfunction "OUT_6") (pintype "output"))
    )
    (net (code "106") (name "Net-(U9-SHDN)") (class "Default")
      (node (ref "R42") (pin "1") (pinfunction "1_1") (pintype "passive"))
      (node (ref "U9") (pin "8") (pinfunction "SHDN_8") (pintype "passive"))
    )
    (net (code "107") (name "Net-(U10-IN+)") (class "Default")
      (node (ref "R40") (pin "2") (pinfunction "2_2") (pintype "passive"))
      (node (ref "U10") (pin "3") (pinfunction "IN+_3") (pintype "input"))
    )
    (net (code "108") (name "Net-(U10-IN-)") (class "Default")
      (node (ref "R38") (pin "2") (pinfunction "2_2") (pintype "passive"))
      (node (ref "U10") (pin "2") (pinfunction "IN-_2") (pintype "input"))
    )
    (net (code "109") (name "Net-(U10-OUT)") (class "Default")
      (node (ref "R36") (pin "1") (pinfunction "1_1") (pintype "passive"))
      (node (ref "U10") (pin "6") (pinfunction "OUT_6") (pintype "output"))
    )
    (net (code "110") (name "Net-(U11-IN+)") (class "Default")
      (node (ref "R44") (pin "2") (pinfunction "2_2") (pintype "passive"))
      (node (ref "U11") (pin "3") (pinfunction "IN+_3") (pintype "input"))
    )
    (net (code "111") (name "Net-(U11-IN-)") (class "Default")
      (node (ref "R43") (pin "1") (pinfunction "1_1") (pintype "passive"))
      (node (ref "U11") (pin "2") (pinfunction "IN-_2") (pintype "input"))
    )
    (net (code "112") (name "Net-(U11-OUT)") (class "Default")
      (node (ref "R48") (pin "1") (pinfunction "1_1") (pintype "passive"))
      (node (ref "U11") (pin "6") (pinfunction "OUT_6") (pintype "output"))
    )
    (net (code "113") (name "Net-(U11-SHDN)") (class "Default")
      (node (ref "R51") (pin "1") (pinfunction "1_1") (pintype "passive"))
      (node (ref "U11") (pin "8") (pinfunction "SHDN_8") (pintype "passive"))
    )
    (net (code "114") (name "Net-(U12-IN+)") (class "Default")
      (node (ref "R49") (pin "2") (pinfunction "2_2") (pintype "passive"))
      (node (ref "U12") (pin "3") (pinfunction "IN+_3") (pintype "input"))
    )
    (net (code "115") (name "Net-(U12-IN-)") (class "Default")
      (node (ref "R47") (pin "2") (pinfunction "2_2") (pintype "passive"))
      (node (ref "U12") (pin "2") (pinfunction "IN-_2") (pintype "input"))
    )
    (net (code "116") (name "Net-(U12-OUT)") (class "Default")
      (node (ref "R45") (pin "1") (pinfunction "1_1") (pintype "passive"))
      (node (ref "U12") (pin "6") (pinfunction "OUT_6") (pintype "output"))
    )
    (net (code "117") (name "Net-(U13-IN+)") (class "Default")
      (node (ref "R53") (pin "2") (pinfunction "2_2") (pintype "passive"))
      (node (ref "U13") (pin "3") (pinfunction "IN+_3") (pintype "input"))
    )
    (net (code "118") (name "Net-(U13-IN-)") (class "Default")
      (node (ref "R52") (pin "1") (pinfunction "1_1") (pintype "passive"))
      (node (ref "U13") (pin "2") (pinfunction "IN-_2") (pintype "input"))
    )
    (net (code "119") (name "Net-(U13-OUT)") (class "Default")
      (node (ref "R57") (pin "1") (pinfunction "1_1") (pintype "passive"))
      (node (ref "U13") (pin "6") (pinfunction "OUT_6") (pintype "output"))
    )
    (net (code "120") (name "Net-(U13-SHDN)") (class "Default")
      (node (ref "R60") (pin "1") (pinfunction "1_1") (pintype "passive"))
      (node (ref "U13") (pin "8") (pinfunction "SHDN_8") (pintype "passive"))
    )
    (net (code "121") (name "Net-(U14-IN+)") (class "Default")
      (node (ref "R58") (pin "2") (pinfunction "2_2") (pintype "passive"))
      (node (ref "U14") (pin "3") (pinfunction "IN+_3") (pintype "input"))
    )
    (net (code "122") (name "Net-(U14-IN-)") (class "Default")
      (node (ref "R56") (pin "2") (pinfunction "2_2") (pintype "passive"))
      (node (ref "U14") (pin "2") (pinfunction "IN-_2") (pintype "input"))
    )
    (net (code "123") (name "Net-(U14-OUT)") (class "Default")
      (node (ref "R54") (pin "1") (pinfunction "1_1") (pintype "passive"))
      (node (ref "U14") (pin "6") (pinfunction "OUT_6") (pintype "output"))
    )
    (net (code "124") (name "Net-(U15-IN+)") (class "Default")
      (node (ref "R62") (pin "2") (pinfunction "2_2") (pintype "passive"))
      (node (ref "U15") (pin "3") (pinfunction "IN+_3") (pintype "input"))
    )
    (net (code "125") (name "Net-(U15-IN-)") (class "Default")
      (node (ref "R61") (pin "1") (pinfunction "1_1") (pintype "passive"))
      (node (ref "U15") (pin "2") (pinfunction "IN-_2") (pintype "input"))
    )
    (net (code "126") (name "Net-(U15-OUT)") (class "Default")
      (node (ref "R66") (pin "1") (pinfunction "1_1") (pintype "passive"))
      (node (ref "U15") (pin "6") (pinfunction "OUT_6") (pintype "output"))
    )
    (net (code "127") (name "Net-(U15-SHDN)") (class "Default")
      (node (ref "R69") (pin "1") (pinfunction "1_1") (pintype "passive"))
      (node (ref "U15") (pin "8") (pinfunction "SHDN_8") (pintype "passive"))
    )
    (net (code "128") (name "Net-(U16-IN+)") (class "Default")
      (node (ref "R67") (pin "2") (pinfunction "2_2") (pintype "passive"))
      (node (ref "U16") (pin "3") (pinfunction "IN+_3") (pintype "input"))
    )
    (net (code "129") (name "Net-(U16-IN-)") (class "Default")
      (node (ref "R65") (pin "2") (pinfunction "2_2") (pintype "passive"))
      (node (ref "U16") (pin "2") (pinfunction "IN-_2") (pintype "input"))
    )
    (net (code "130") (name "Net-(U16-OUT)") (class "Default")
      (node (ref "R63") (pin "1") (pinfunction "1_1") (pintype "passive"))
      (node (ref "U16") (pin "6") (pinfunction "OUT_6") (pintype "output"))
    )
    (net (code "131") (name "Net-(U17-IN+)") (class "Default")
      (node (ref "R71") (pin "2") (pinfunction "2_2") (pintype "passive"))
      (node (ref "U17") (pin "3") (pinfunction "IN+_3") (pintype "input"))
    )
    (net (code "132") (name "Net-(U17-IN-)") (class "Default")
      (node (ref "R70") (pin "1") (pinfunction "1_1") (pintype "passive"))
      (node (ref "U17") (pin "2") (pinfunction "IN-_2") (pintype "input"))
    )
    (net (code "133") (name "Net-(U17-OUT)") (class "Default")
      (node (ref "R75") (pin "1") (pinfunction "1_1") (pintype "passive"))
      (node (ref "U17") (pin "6") (pinfunction "OUT_6") (pintype "output"))
    )
    (net (code "134") (name "Net-(U17-SHDN)") (class "Default")
      (node (ref "R78") (pin "1") (pinfunction "1_1") (pintype "passive"))
      (node (ref "U17") (pin "8") (pinfunction "SHDN_8") (pintype "passive"))
    )
    (net (code "135") (name "Net-(U18-IN+)") (class "Default")
      (node (ref "R76") (pin "2") (pinfunction "2_2") (pintype "passive"))
      (node (ref "U18") (pin "3") (pinfunction "IN+_3") (pintype "input"))
    )
    (net (code "136") (name "Net-(U18-IN-)") (class "Default")
      (node (ref "R74") (pin "2") (pinfunction "2_2") (pintype "passive"))
      (node (ref "U18") (pin "2") (pinfunction "IN-_2") (pintype "input"))
    )
    (net (code "137") (name "Net-(U18-OUT)") (class "Default")
      (node (ref "R72") (pin "1") (pinfunction "1_1") (pintype "passive"))
      (node (ref "U18") (pin "6") (pinfunction "OUT_6") (pintype "output"))
    )
    (net (code "138") (name "Net-(U19-IN+)") (class "Default")
      (node (ref "R80") (pin "2") (pinfunction "2_2") (pintype "passive"))
      (node (ref "U19") (pin "3") (pinfunction "IN+_3") (pintype "input"))
    )
    (net (code "139") (name "Net-(U19-IN-)") (class "Default")
      (node (ref "R79") (pin "1") (pinfunction "1_1") (pintype "passive"))
      (node (ref "U19") (pin "2") (pinfunction "IN-_2") (pintype "input"))
    )
    (net (code "140") (name "Net-(U19-OUT)") (class "Default")
      (node (ref "R84") (pin "1") (pinfunction "1_1") (pintype "passive"))
      (node (ref "U19") (pin "6") (pinfunction "OUT_6") (pintype "output"))
    )
    (net (code "141") (name "Net-(U19-SHDN)") (class "Default")
      (node (ref "R87") (pin "1") (pinfunction "1_1") (pintype "passive"))
      (node (ref "U19") (pin "8") (pinfunction "SHDN_8") (pintype "passive"))
    )
    (net (code "142") (name "Net-(U20-IN+)") (class "Default")
      (node (ref "R85") (pin "2") (pinfunction "2_2") (pintype "passive"))
      (node (ref "U20") (pin "3") (pinfunction "IN+_3") (pintype "input"))
    )
    (net (code "143") (name "Net-(U20-IN-)") (class "Default")
      (node (ref "R83") (pin "2") (pinfunction "2_2") (pintype "passive"))
      (node (ref "U20") (pin "2") (pinfunction "IN-_2") (pintype "input"))
    )
    (net (code "144") (name "Net-(U20-OUT)") (class "Default")
      (node (ref "R81") (pin "1") (pinfunction "1_1") (pintype "passive"))
      (node (ref "U20") (pin "6") (pinfunction "OUT_6") (pintype "output"))
    )
    (net (code "145") (name "Net-(U21-IN+)") (class "Default")
      (node (ref "R89") (pin "2") (pinfunction "2_2") (pintype "passive"))
      (node (ref "U21") (pin "3") (pinfunction "IN+_3") (pintype "input"))
    )
    (net (code "146") (name "Net-(U21-IN-)") (class "Default")
      (node (ref "R88") (pin "1") (pinfunction "1_1") (pintype "passive"))
      (node (ref "U21") (pin "2") (pinfunction "IN-_2") (pintype "input"))
    )
    (net (code "147") (name "Net-(U21-OUT)") (class "Default")
      (node (ref "R93") (pin "1") (pinfunction "1_1") (pintype "passive"))
      (node (ref "U21") (pin "6") (pinfunction "OUT_6") (pintype "output"))
    )
    (net (code "148") (name "Net-(U21-SHDN)") (class "Default")
      (node (ref "R96") (pin "1") (pinfunction "1_1") (pintype "passive"))
      (node (ref "U21") (pin "8") (pinfunction "SHDN_8") (pintype "passive"))
    )
    (net (code "149") (name "Net-(U22-IN+)") (class "Default")
      (node (ref "R94") (pin "2") (pinfunction "2_2") (pintype "passive"))
      (node (ref "U22") (pin "3") (pinfunction "IN+_3") (pintype "input"))
    )
    (net (code "150") (name "Net-(U22-IN-)") (class "Default")
      (node (ref "R92") (pin "2") (pinfunction "2_2") (pintype "passive"))
      (node (ref "U22") (pin "2") (pinfunction "IN-_2") (pintype "input"))
    )
    (net (code "151") (name "Net-(U22-OUT)") (class "Default")
      (node (ref "R90") (pin "1") (pinfunction "1_1") (pintype "passive"))
      (node (ref "U22") (pin "6") (pinfunction "OUT_6") (pintype "output"))
    )
    (net (code "152") (name "Net-(U23-IN+)") (class "Default")
      (node (ref "R98") (pin "2") (pinfunction "2_2") (pintype "passive"))
      (node (ref "U23") (pin "3") (pinfunction "IN+_3") (pintype "input"))
    )
    (net (code "153") (name "Net-(U23-IN-)") (class "Default")
      (node (ref "R97") (pin "1") (pinfunction "1_1") (pintype "passive"))
      (node (ref "U23") (pin "2") (pinfunction "IN-_2") (pintype "input"))
    )
    (net (code "154") (name "Net-(U23-OUT)") (class "Default")
      (node (ref "R102") (pin "1") (pinfunction "1_1") (pintype "passive"))
      (node (ref "U23") (pin "6") (pinfunction "OUT_6") (pintype "output"))
    )
    (net (code "155") (name "Net-(U23-SHDN)") (class "Default")
      (node (ref "R105") (pin "1") (pinfunction "1_1") (pintype "passive"))
      (node (ref "U23") (pin "8") (pinfunction "SHDN_8") (pintype "passive"))
    )
    (net (code "156") (name "Net-(U24-IN+)") (class "Default")
      (node (ref "R103") (pin "2") (pinfunction "2_2") (pintype "passive"))
      (node (ref "U24") (pin "3") (pinfunction "IN+_3") (pintype "input"))
    )
    (net (code "157") (name "Net-(U24-IN-)") (class "Default")
      (node (ref "R101") (pin "2") (pinfunction "2_2") (pintype "passive"))
      (node (ref "U24") (pin "2") (pinfunction "IN-_2") (pintype "input"))
    )
    (net (code "158") (name "Net-(U24-OUT)") (class "Default")
      (node (ref "R99") (pin "1") (pinfunction "1_1") (pintype "passive"))
      (node (ref "U24") (pin "6") (pinfunction "OUT_6") (pintype "output"))
    )
    (net (code "159") (name "Net-(U25-IN+)") (class "Default")
      (node (ref "R107") (pin "2") (pinfunction "2_2") (pintype "passive"))
      (node (ref "U25") (pin "3") (pinfunction "IN+_3") (pintype "input"))
    )
    (net (code "160") (name "Net-(U25-IN-)") (class "Default")
      (node (ref "R106") (pin "1") (pinfunction "1_1") (pintype "passive"))
      (node (ref "U25") (pin "2") (pinfunction "IN-_2") (pintype "input"))
    )
    (net (code "161") (name "Net-(U25-OUT)") (class "Default")
      (node (ref "R111") (pin "1") (pinfunction "1_1") (pintype "passive"))
      (node (ref "U25") (pin "6") (pinfunction "OUT_6") (pintype "output"))
    )
    (net (code "162") (name "Net-(U25-SHDN)") (class "Default")
      (node (ref "R114") (pin "1") (pinfunction "1_1") (pintype "passive"))
      (node (ref "U25") (pin "8") (pinfunction "SHDN_8") (pintype "passive"))
    )
    (net (code "163") (name "Net-(U26-IN+)") (class "Default")
      (node (ref "R112") (pin "2") (pinfunction "2_2") (pintype "passive"))
      (node (ref "U26") (pin "3") (pinfunction "IN+_3") (pintype "input"))
    )
    (net (code "164") (name "Net-(U26-IN-)") (class "Default")
      (node (ref "R110") (pin "2") (pinfunction "2_2") (pintype "passive"))
      (node (ref "U26") (pin "2") (pinfunction "IN-_2") (pintype "input"))
    )
    (net (code "165") (name "Net-(U26-OUT)") (class "Default")
      (node (ref "R108") (pin "1") (pinfunction "1_1") (pintype "passive"))
      (node (ref "U26") (pin "6") (pinfunction "OUT_6") (pintype "output"))
    )
    (net (code "166") (name "Net-(U27-IN+)") (class "Default")
      (node (ref "R116") (pin "2") (pinfunction "2_2") (pintype "passive"))
      (node (ref "U27") (pin "3") (pinfunction "IN+_3") (pintype "input"))
    )
    (net (code "167") (name "Net-(U27-IN-)") (class "Default")
      (node (ref "R115") (pin "1") (pinfunction "1_1") (pintype "passive"))
      (node (ref "U27") (pin "2") (pinfunction "IN-_2") (pintype "input"))
    )
    (net (code "168") (name "Net-(U27-OUT)") (class "Default")
      (node (ref "R120") (pin "1") (pinfunction "1_1") (pintype "passive"))
      (node (ref "U27") (pin "6") (pinfunction "OUT_6") (pintype "output"))
    )
    (net (code "169") (name "Net-(U27-SHDN)") (class "Default")
      (node (ref "R123") (pin "1") (pinfunction "1_1") (pintype "passive"))
      (node (ref "U27") (pin "8") (pinfunction "SHDN_8") (pintype "passive"))
    )
    (net (code "170") (name "Net-(U28-IN+)") (class "Default")
      (node (ref "R121") (pin "2") (pinfunction "2_2") (pintype "passive"))
      (node (ref "U28") (pin "3") (pinfunction "IN+_3") (pintype "input"))
    )
    (net (code "171") (name "Net-(U28-IN-)") (class "Default")
      (node (ref "R119") (pin "2") (pinfunction "2_2") (pintype "passive"))
      (node (ref "U28") (pin "2") (pinfunction "IN-_2") (pintype "input"))
    )
    (net (code "172") (name "Net-(U28-OUT)") (class "Default")
      (node (ref "R117") (pin "1") (pinfunction "1_1") (pintype "passive"))
      (node (ref "U28") (pin "6") (pinfunction "OUT_6") (pintype "output"))
    )
    (net (code "173") (name "Net-(U29-IN+)") (class "Default")
      (node (ref "R125") (pin "2") (pinfunction "2_2") (pintype "passive"))
      (node (ref "U29") (pin "3") (pinfunction "IN+_3") (pintype "input"))
    )
    (net (code "174") (name "Net-(U29-IN-)") (class "Default")
      (node (ref "R124") (pin "1") (pinfunction "1_1") (pintype "passive"))
      (node (ref "U29") (pin "2") (pinfunction "IN-_2") (pintype "input"))
    )
    (net (code "175") (name "Net-(U29-OUT)") (class "Default")
      (node (ref "R129") (pin "1") (pinfunction "1_1") (pintype "passive"))
      (node (ref "U29") (pin "6") (pinfunction "OUT_6") (pintype "output"))
    )
    (net (code "176") (name "Net-(U29-SHDN)") (class "Default")
      (node (ref "R132") (pin "1") (pinfunction "1_1") (pintype "passive"))
      (node (ref "U29") (pin "8") (pinfunction "SHDN_8") (pintype "passive"))
    )
    (net (code "177") (name "Net-(U30-IN+)") (class "Default")
      (node (ref "R130") (pin "2") (pinfunction "2_2") (pintype "passive"))
      (node (ref "U30") (pin "3") (pinfunction "IN+_3") (pintype "input"))
    )
    (net (code "178") (name "Net-(U30-IN-)") (class "Default")
      (node (ref "R128") (pin "2") (pinfunction "2_2") (pintype "passive"))
      (node (ref "U30") (pin "2") (pinfunction "IN-_2") (pintype "input"))
    )
    (net (code "179") (name "Net-(U30-OUT)") (class "Default")
      (node (ref "R126") (pin "1") (pinfunction "1_1") (pintype "passive"))
      (node (ref "U30") (pin "6") (pinfunction "OUT_6") (pintype "output"))
    )
    (net (code "180") (name "Net-(U31-IN+)") (class "Default")
      (node (ref "R134") (pin "2") (pinfunction "2_2") (pintype "passive"))
      (node (ref "U31") (pin "3") (pinfunction "IN+_3") (pintype "input"))
    )
    (net (code "181") (name "Net-(U31-IN-)") (class "Default")
      (node (ref "R133") (pin "1") (pinfunction "1_1") (pintype "passive"))
      (node (ref "U31") (pin "2") (pinfunction "IN-_2") (pintype "input"))
    )
    (net (code "182") (name "Net-(U31-OUT)") (class "Default")
      (node (ref "R138") (pin "1") (pinfunction "1_1") (pintype "passive"))
      (node (ref "U31") (pin "6") (pinfunction "OUT_6") (pintype "output"))
    )
    (net (code "183") (name "Net-(U31-SHDN)") (class "Default")
      (node (ref "R141") (pin "1") (pinfunction "1_1") (pintype "passive"))
      (node (ref "U31") (pin "8") (pinfunction "SHDN_8") (pintype "passive"))
    )
    (net (code "184") (name "Net-(U32-IN+)") (class "Default")
      (node (ref "R139") (pin "2") (pinfunction "2_2") (pintype "passive"))
      (node (ref "U32") (pin "3") (pinfunction "IN+_3") (pintype "input"))
    )
    (net (code "185") (name "Net-(U32-IN-)") (class "Default")
      (node (ref "R137") (pin "2") (pinfunction "2_2") (pintype "passive"))
      (node (ref "U32") (pin "2") (pinfunction "IN-_2") (pintype "input"))
    )
    (net (code "186") (name "Net-(U32-OUT)") (class "Default")
      (node (ref "R135") (pin "1") (pinfunction "1_1") (pintype "passive"))
      (node (ref "U32") (pin "6") (pinfunction "OUT_6") (pintype "output"))
    )
    (net (code "187") (name "Net-(U33-IN+)") (class "Default")
      (node (ref "R143") (pin "2") (pinfunction "2_2") (pintype "passive"))
      (node (ref "U33") (pin "3") (pinfunction "IN+_3") (pintype "input"))
    )
    (net (code "188") (name "Net-(U33-IN-)") (class "Default")
      (node (ref "R142") (pin "1") (pinfunction "1_1") (pintype "passive"))
      (node (ref "U33") (pin "2") (pinfunction "IN-_2") (pintype "input"))
    )
    (net (code "189") (name "Net-(U33-OUT)") (class "Default")
      (node (ref "R147") (pin "1") (pinfunction "1_1") (pintype "passive"))
      (node (ref "U33") (pin "6") (pinfunction "OUT_6") (pintype "output"))
    )
    (net (code "190") (name "Net-(U33-SHDN)") (class "Default")
      (node (ref "R150") (pin "1") (pinfunction "1_1") (pintype "passive"))
      (node (ref "U33") (pin "8") (pinfunction "SHDN_8") (pintype "passive"))
    )
    (net (code "191") (name "Net-(U34-IN+)") (class "Default")
      (node (ref "R148") (pin "2") (pinfunction "2_2") (pintype "passive"))
      (node (ref "U34") (pin "3") (pinfunction "IN+_3") (pintype "input"))
    )
    (net (code "192") (name "Net-(U34-IN-)") (class "Default")
      (node (ref "R146") (pin "2") (pinfunction "2_2") (pintype "passive"))
      (node (ref "U34") (pin "2") (pinfunction "IN-_2") (pintype "input"))
    )
    (net (code "193") (name "Net-(U34-OUT)") (class "Default")
      (node (ref "R144") (pin "1") (pinfunction "1_1") (pintype "passive"))
      (node (ref "U34") (pin "6") (pinfunction "OUT_6") (pintype "output"))
    )
    (net (code "194") (name "Net-(U38-GATE)") (class "Default")
      (node (ref "R165") (pin "2") (pinfunction "2_2") (pintype "passive"))
      (node (ref "U38") (pin "1") (pinfunction "GATE_1") (pintype "passive"))
    )
    (net (code "195") (name "Net-(U39-IN+)") (class "Default")
      (node (ref "R160") (pin "2") (pinfunction "2_2") (pintype "passive"))
      (node (ref "U39") (pin "3") (pinfunction "IN+_3") (pintype "input"))
    )
    (net (code "196") (name "Net-(U39-IN-)") (class "Default")
      (node (ref "R159") (pin "2") (pinfunction "2_2") (pintype "passive"))
      (node (ref "U39") (pin "2") (pinfunction "IN-_2") (pintype "input"))
    )
    (net (code "197") (name "Net-(U39-OUT)") (class "Default")
      (node (ref "EN_TP1") (pin "1") (pinfunction "1_1") (pintype "passive"))
      (node (ref "R166") (pin "1") (pinfunction "1_1") (pintype "passive"))
      (node (ref "U39") (pin "6") (pinfunction "OUT_6") (pintype "output"))
    )
    (net (code "198") (name "Net-(U40-IN+)") (class "Default")
      (node (ref "R164") (pin "2") (pinfunction "2_2") (pintype "passive"))
      (node (ref "U40") (pin "3") (pinfunction "IN+_3") (pintype "input"))
    )
    (net (code "199") (name "Net-(U40-IN-)") (class "Default")
      (node (ref "R163") (pin "2") (pinfunction "2_2") (pintype "passive"))
      (node (ref "U40") (pin "2") (pinfunction "IN-_2") (pintype "input"))
    )
    (net (code "200") (name "unconnected-(J1-Pad18)") (class "Default")
      (node (ref "J1") (pin "18") (pinfunction "18_18") (pintype "bidirectional"))
    )
    (net (code "201") (name "unconnected-(J1-Pad19)") (class "Default")
      (node (ref "J1") (pin "19") (pinfunction "19_19") (pintype "bidirectional"))
    )
    (net (code "202") (name "unconnected-(J1-Pad20)") (class "Default")
      (node (ref "J1") (pin "20") (pinfunction "20_20") (pintype "bidirectional"))
    )
    (net (code "203") (name "unconnected-(J1-Pad21)") (class "Default")
      (node (ref "J1") (pin "21") (pinfunction "21_21") (pintype "bidirectional"))
    )
    (net (code "204") (name "unconnected-(J1-Pad22)") (class "Default")
      (node (ref "J1") (pin "22") (pinfunction "22_22") (pintype "bidirectional"))
    )
    (net (code "205") (name "unconnected-(J1-Pad23)") (class "Default")
      (node (ref "J1") (pin "23") (pinfunction "23_23") (pintype "bidirectional"))
    )
    (net (code "206") (name "unconnected-(J1-Pad24)") (class "Default")
      (node (ref "J1") (pin "24") (pinfunction "24_24") (pintype "bidirectional"))
    )
    (net (code "207") (name "unconnected-(J2-Pad18)") (class "Default")
      (node (ref "J2") (pin "18") (pinfunction "18_18") (pintype "bidirectional"))
    )
    (net (code "208") (name "unconnected-(J2-Pad19)") (class "Default")
      (node (ref "J2") (pin "19") (pinfunction "19_19") (pintype "bidirectional"))
    )
    (net (code "209") (name "unconnected-(J2-Pad20)") (class "Default")
      (node (ref "J2") (pin "20") (pinfunction "20_20") (pintype "bidirectional"))
    )
    (net (code "210") (name "unconnected-(J2-Pad21)") (class "Default")
      (node (ref "J2") (pin "21") (pinfunction "21_21") (pintype "bidirectional"))
    )
    (net (code "211") (name "unconnected-(J2-Pad22)") (class "Default")
      (node (ref "J2") (pin "22") (pinfunction "22_22") (pintype "bidirectional"))
    )
    (net (code "212") (name "unconnected-(J2-Pad23)") (class "Default")
      (node (ref "J2") (pin "23") (pinfunction "23_23") (pintype "bidirectional"))
    )
    (net (code "213") (name "unconnected-(J2-Pad24)") (class "Default")
      (node (ref "J2") (pin "24") (pinfunction "24_24") (pintype "bidirectional"))
    )
    (net (code "214") (name "unconnected-(U3-NC-Pad5)") (class "Default")
      (node (ref "U3") (pin "5") (pinfunction "NC_5") (pintype "passive"))
    )
    (net (code "215") (name "unconnected-(U3-NC_2-Pad1)") (class "Default")
      (node (ref "U3") (pin "1") (pinfunction "NC_2_1") (pintype "passive"))
    )
    (net (code "216") (name "unconnected-(U4-NC-Pad5)") (class "Default")
      (node (ref "U4") (pin "5") (pinfunction "NC_5") (pintype "passive"))
    )
    (net (code "217") (name "unconnected-(U4-NC_2-Pad1)") (class "Default")
      (node (ref "U4") (pin "1") (pinfunction "NC_2_1") (pintype "passive"))
    )
    (net (code "218") (name "unconnected-(U5-NC-Pad5)") (class "Default")
      (node (ref "U5") (pin "5") (pinfunction "NC_5") (pintype "passive"))
    )
    (net (code "219") (name "unconnected-(U5-NC_2-Pad1)") (class "Default")
      (node (ref "U5") (pin "1") (pinfunction "NC_2_1") (pintype "passive"))
    )
    (net (code "220") (name "unconnected-(U6-NC-Pad5)") (class "Default")
      (node (ref "U6") (pin "5") (pinfunction "NC_5") (pintype "passive"))
    )
    (net (code "221") (name "unconnected-(U6-NC_2-Pad1)") (class "Default")
      (node (ref "U6") (pin "1") (pinfunction "NC_2_1") (pintype "passive"))
    )
    (net (code "222") (name "unconnected-(U7-NC-Pad5)") (class "Default")
      (node (ref "U7") (pin "5") (pinfunction "NC_5") (pintype "passive"))
    )
    (net (code "223") (name "unconnected-(U7-NC_2-Pad1)") (class "Default")
      (node (ref "U7") (pin "1") (pinfunction "NC_2_1") (pintype "passive"))
    )
    (net (code "224") (name "unconnected-(U8-NC-Pad5)") (class "Default")
      (node (ref "U8") (pin "5") (pinfunction "NC_5") (pintype "passive"))
    )
    (net (code "225") (name "unconnected-(U8-NC_2-Pad1)") (class "Default")
      (node (ref "U8") (pin "1") (pinfunction "NC_2_1") (pintype "passive"))
    )
    (net (code "226") (name "unconnected-(U9-NC-Pad5)") (class "Default")
      (node (ref "U9") (pin "5") (pinfunction "NC_5") (pintype "passive"))
    )
    (net (code "227") (name "unconnected-(U9-NC_2-Pad1)") (class "Default")
      (node (ref "U9") (pin "1") (pinfunction "NC_2_1") (pintype "passive"))
    )
    (net (code "228") (name "unconnected-(U10-NC-Pad5)") (class "Default")
      (node (ref "U10") (pin "5") (pinfunction "NC_5") (pintype "passive"))
    )
    (net (code "229") (name "unconnected-(U10-NC_2-Pad1)") (class "Default")
      (node (ref "U10") (pin "1") (pinfunction "NC_2_1") (pintype "passive"))
    )
    (net (code "230") (name "unconnected-(U11-NC-Pad5)") (class "Default")
      (node (ref "U11") (pin "5") (pinfunction "NC_5") (pintype "passive"))
    )
    (net (code "231") (name "unconnected-(U11-NC_2-Pad1)") (class "Default")
      (node (ref "U11") (pin "1") (pinfunction "NC_2_1") (pintype "passive"))
    )
    (net (code "232") (name "unconnected-(U12-NC-Pad5)") (class "Default")
      (node (ref "U12") (pin "5") (pinfunction "NC_5") (pintype "passive"))
    )
    (net (code "233") (name "unconnected-(U12-NC_2-Pad1)") (class "Default")
      (node (ref "U12") (pin "1") (pinfunction "NC_2_1") (pintype "passive"))
    )
    (net (code "234") (name "unconnected-(U13-NC-Pad5)") (class "Default")
      (node (ref "U13") (pin "5") (pinfunction "NC_5") (pintype "passive"))
    )
    (net (code "235") (name "unconnected-(U13-NC_2-Pad1)") (class "Default")
      (node (ref "U13") (pin "1") (pinfunction "NC_2_1") (pintype "passive"))
    )
    (net (code "236") (name "unconnected-(U14-NC-Pad5)") (class "Default")
      (node (ref "U14") (pin "5") (pinfunction "NC_5") (pintype "passive"))
    )
    (net (code "237") (name "unconnected-(U14-NC_2-Pad1)") (class "Default")
      (node (ref "U14") (pin "1") (pinfunction "NC_2_1") (pintype "passive"))
    )
    (net (code "238") (name "unconnected-(U15-NC-Pad5)") (class "Default")
      (node (ref "U15") (pin "5") (pinfunction "NC_5") (pintype "passive"))
    )
    (net (code "239") (name "unconnected-(U15-NC_2-Pad1)") (class "Default")
      (node (ref "U15") (pin "1") (pinfunction "NC_2_1") (pintype "passive"))
    )
    (net (code "240") (name "unconnected-(U16-NC-Pad5)") (class "Default")
      (node (ref "U16") (pin "5") (pinfunction "NC_5") (pintype "passive"))
    )
    (net (code "241") (name "unconnected-(U16-NC_2-Pad1)") (class "Default")
      (node (ref "U16") (pin "1") (pinfunction "NC_2_1") (pintype "passive"))
    )
    (net (code "242") (name "unconnected-(U17-NC-Pad5)") (class "Default")
      (node (ref "U17") (pin "5") (pinfunction "NC_5") (pintype "passive"))
    )
    (net (code "243") (name "unconnected-(U17-NC_2-Pad1)") (class "Default")
      (node (ref "U17") (pin "1") (pinfunction "NC_2_1") (pintype "passive"))
    )
    (net (code "244") (name "unconnected-(U18-NC-Pad5)") (class "Default")
      (node (ref "U18") (pin "5") (pinfunction "NC_5") (pintype "passive"))
    )
    (net (code "245") (name "unconnected-(U18-NC_2-Pad1)") (class "Default")
      (node (ref "U18") (pin "1") (pinfunction "NC_2_1") (pintype "passive"))
    )
    (net (code "246") (name "unconnected-(U19-NC-Pad5)") (class "Default")
      (node (ref "U19") (pin "5") (pinfunction "NC_5") (pintype "passive"))
    )
    (net (code "247") (name "unconnected-(U19-NC_2-Pad1)") (class "Default")
      (node (ref "U19") (pin "1") (pinfunction "NC_2_1") (pintype "passive"))
    )
    (net (code "248") (name "unconnected-(U20-NC-Pad5)") (class "Default")
      (node (ref "U20") (pin "5") (pinfunction "NC_5") (pintype "passive"))
    )
    (net (code "249") (name "unconnected-(U20-NC_2-Pad1)") (class "Default")
      (node (ref "U20") (pin "1") (pinfunction "NC_2_1") (pintype "passive"))
    )
    (net (code "250") (name "unconnected-(U21-NC-Pad5)") (class "Default")
      (node (ref "U21") (pin "5") (pinfunction "NC_5") (pintype "passive"))
    )
    (net (code "251") (name "unconnected-(U21-NC_2-Pad1)") (class "Default")
      (node (ref "U21") (pin "1") (pinfunction "NC_2_1") (pintype "passive"))
    )
    (net (code "252") (name "unconnected-(U22-NC-Pad5)") (class "Default")
      (node (ref "U22") (pin "5") (pinfunction "NC_5") (pintype "passive"))
    )
    (net (code "253") (name "unconnected-(U22-NC_2-Pad1)") (class "Default")
      (node (ref "U22") (pin "1") (pinfunction "NC_2_1") (pintype "passive"))
    )
    (net (code "254") (name "unconnected-(U23-NC-Pad5)") (class "Default")
      (node (ref "U23") (pin "5") (pinfunction "NC_5") (pintype "passive"))
    )
    (net (code "255") (name "unconnected-(U23-NC_2-Pad1)") (class "Default")
      (node (ref "U23") (pin "1") (pinfunction "NC_2_1") (pintype "passive"))
    )
    (net (code "256") (name "unconnected-(U24-NC-Pad5)") (class "Default")
      (node (ref "U24") (pin "5") (pinfunction "NC_5") (pintype "passive"))
    )
    (net (code "257") (name "unconnected-(U24-NC_2-Pad1)") (class "Default")
      (node (ref "U24") (pin "1") (pinfunction "NC_2_1") (pintype "passive"))
    )
    (net (code "258") (name "unconnected-(U25-NC-Pad5)") (class "Default")
      (node (ref "U25") (pin "5") (pinfunction "NC_5") (pintype "passive"))
    )
    (net (code "259") (name "unconnected-(U25-NC_2-Pad1)") (class "Default")
      (node (ref "U25") (pin "1") (pinfunction "NC_2_1") (pintype "passive"))
    )
    (net (code "260") (name "unconnected-(U26-NC-Pad5)") (class "Default")
      (node (ref "U26") (pin "5") (pinfunction "NC_5") (pintype "passive"))
    )
    (net (code "261") (name "unconnected-(U26-NC_2-Pad1)") (class "Default")
      (node (ref "U26") (pin "1") (pinfunction "NC_2_1") (pintype "passive"))
    )
    (net (code "262") (name "unconnected-(U27-NC-Pad5)") (class "Default")
      (node (ref "U27") (pin "5") (pinfunction "NC_5") (pintype "passive"))
    )
    (net (code "263") (name "unconnected-(U27-NC_2-Pad1)") (class "Default")
      (node (ref "U27") (pin "1") (pinfunction "NC_2_1") (pintype "passive"))
    )
    (net (code "264") (name "unconnected-(U28-NC-Pad5)") (class "Default")
      (node (ref "U28") (pin "5") (pinfunction "NC_5") (pintype "passive"))
    )
    (net (code "265") (name "unconnected-(U28-NC_2-Pad1)") (class "Default")
      (node (ref "U28") (pin "1") (pinfunction "NC_2_1") (pintype "passive"))
    )
    (net (code "266") (name "unconnected-(U29-NC-Pad5)") (class "Default")
      (node (ref "U29") (pin "5") (pinfunction "NC_5") (pintype "passive"))
    )
    (net (code "267") (name "unconnected-(U29-NC_2-Pad1)") (class "Default")
      (node (ref "U29") (pin "1") (pinfunction "NC_2_1") (pintype "passive"))
    )
    (net (code "268") (name "unconnected-(U30-NC-Pad5)") (class "Default")
      (node (ref "U30") (pin "5") (pinfunction "NC_5") (pintype "passive"))
    )
    (net (code "269") (name "unconnected-(U30-NC_2-Pad1)") (class "Default")
      (node (ref "U30") (pin "1") (pinfunction "NC_2_1") (pintype "passive"))
    )
    (net (code "270") (name "unconnected-(U31-NC-Pad5)") (class "Default")
      (node (ref "U31") (pin "5") (pinfunction "NC_5") (pintype "passive"))
    )
    (net (code "271") (name "unconnected-(U31-NC_2-Pad1)") (class "Default")
      (node (ref "U31") (pin "1") (pinfunction "NC_2_1") (pintype "passive"))
    )
    (net (code "272") (name "unconnected-(U32-NC-Pad5)") (class "Default")
      (node (ref "U32") (pin "5") (pinfunction "NC_5") (pintype "passive"))
    )
    (net (code "273") (name "unconnected-(U32-NC_2-Pad1)") (class "Default")
      (node (ref "U32") (pin "1") (pinfunction "NC_2_1") (pintype "passive"))
    )
    (net (code "274") (name "unconnected-(U33-NC-Pad5)") (class "Default")
      (node (ref "U33") (pin "5") (pinfunction "NC_5") (pintype "passive"))
    )
    (net (code "275") (name "unconnected-(U33-NC_2-Pad1)") (class "Default")
      (node (ref "U33") (pin "1") (pinfunction "NC_2_1") (pintype "passive"))
    )
    (net (code "276") (name "unconnected-(U34-NC-Pad5)") (class "Default")
      (node (ref "U34") (pin "5") (pinfunction "NC_5") (pintype "passive"))
    )
    (net (code "277") (name "unconnected-(U34-NC_2-Pad1)") (class "Default")
      (node (ref "U34") (pin "1") (pinfunction "NC_2_1") (pintype "passive"))
    )
    (net (code "278") (name "unconnected-(U39-NC-Pad5)") (class "Default")
      (node (ref "U39") (pin "5") (pinfunction "NC_5") (pintype "passive"))
    )
    (net (code "279") (name "unconnected-(U39-NC_2-Pad1)") (class "Default")
      (node (ref "U39") (pin "1") (pinfunction "NC_2_1") (pintype "passive"))
    )
    (net (code "280") (name "unconnected-(U40-NC-Pad5)") (class "Default")
      (node (ref "U40") (pin "5") (pinfunction "NC_5") (pintype "passive"))
    )
    (net (code "281") (name "unconnected-(U40-NC_2-Pad1)") (class "Default")
      (node (ref "U40") (pin "1") (pinfunction "NC_2_1") (pintype "passive"))
    )
  )
)
